# ProProject_Open_Energy_Box_2024-07-22.net
KiCad netlist of a schematic drawn in EasyEDA Pro
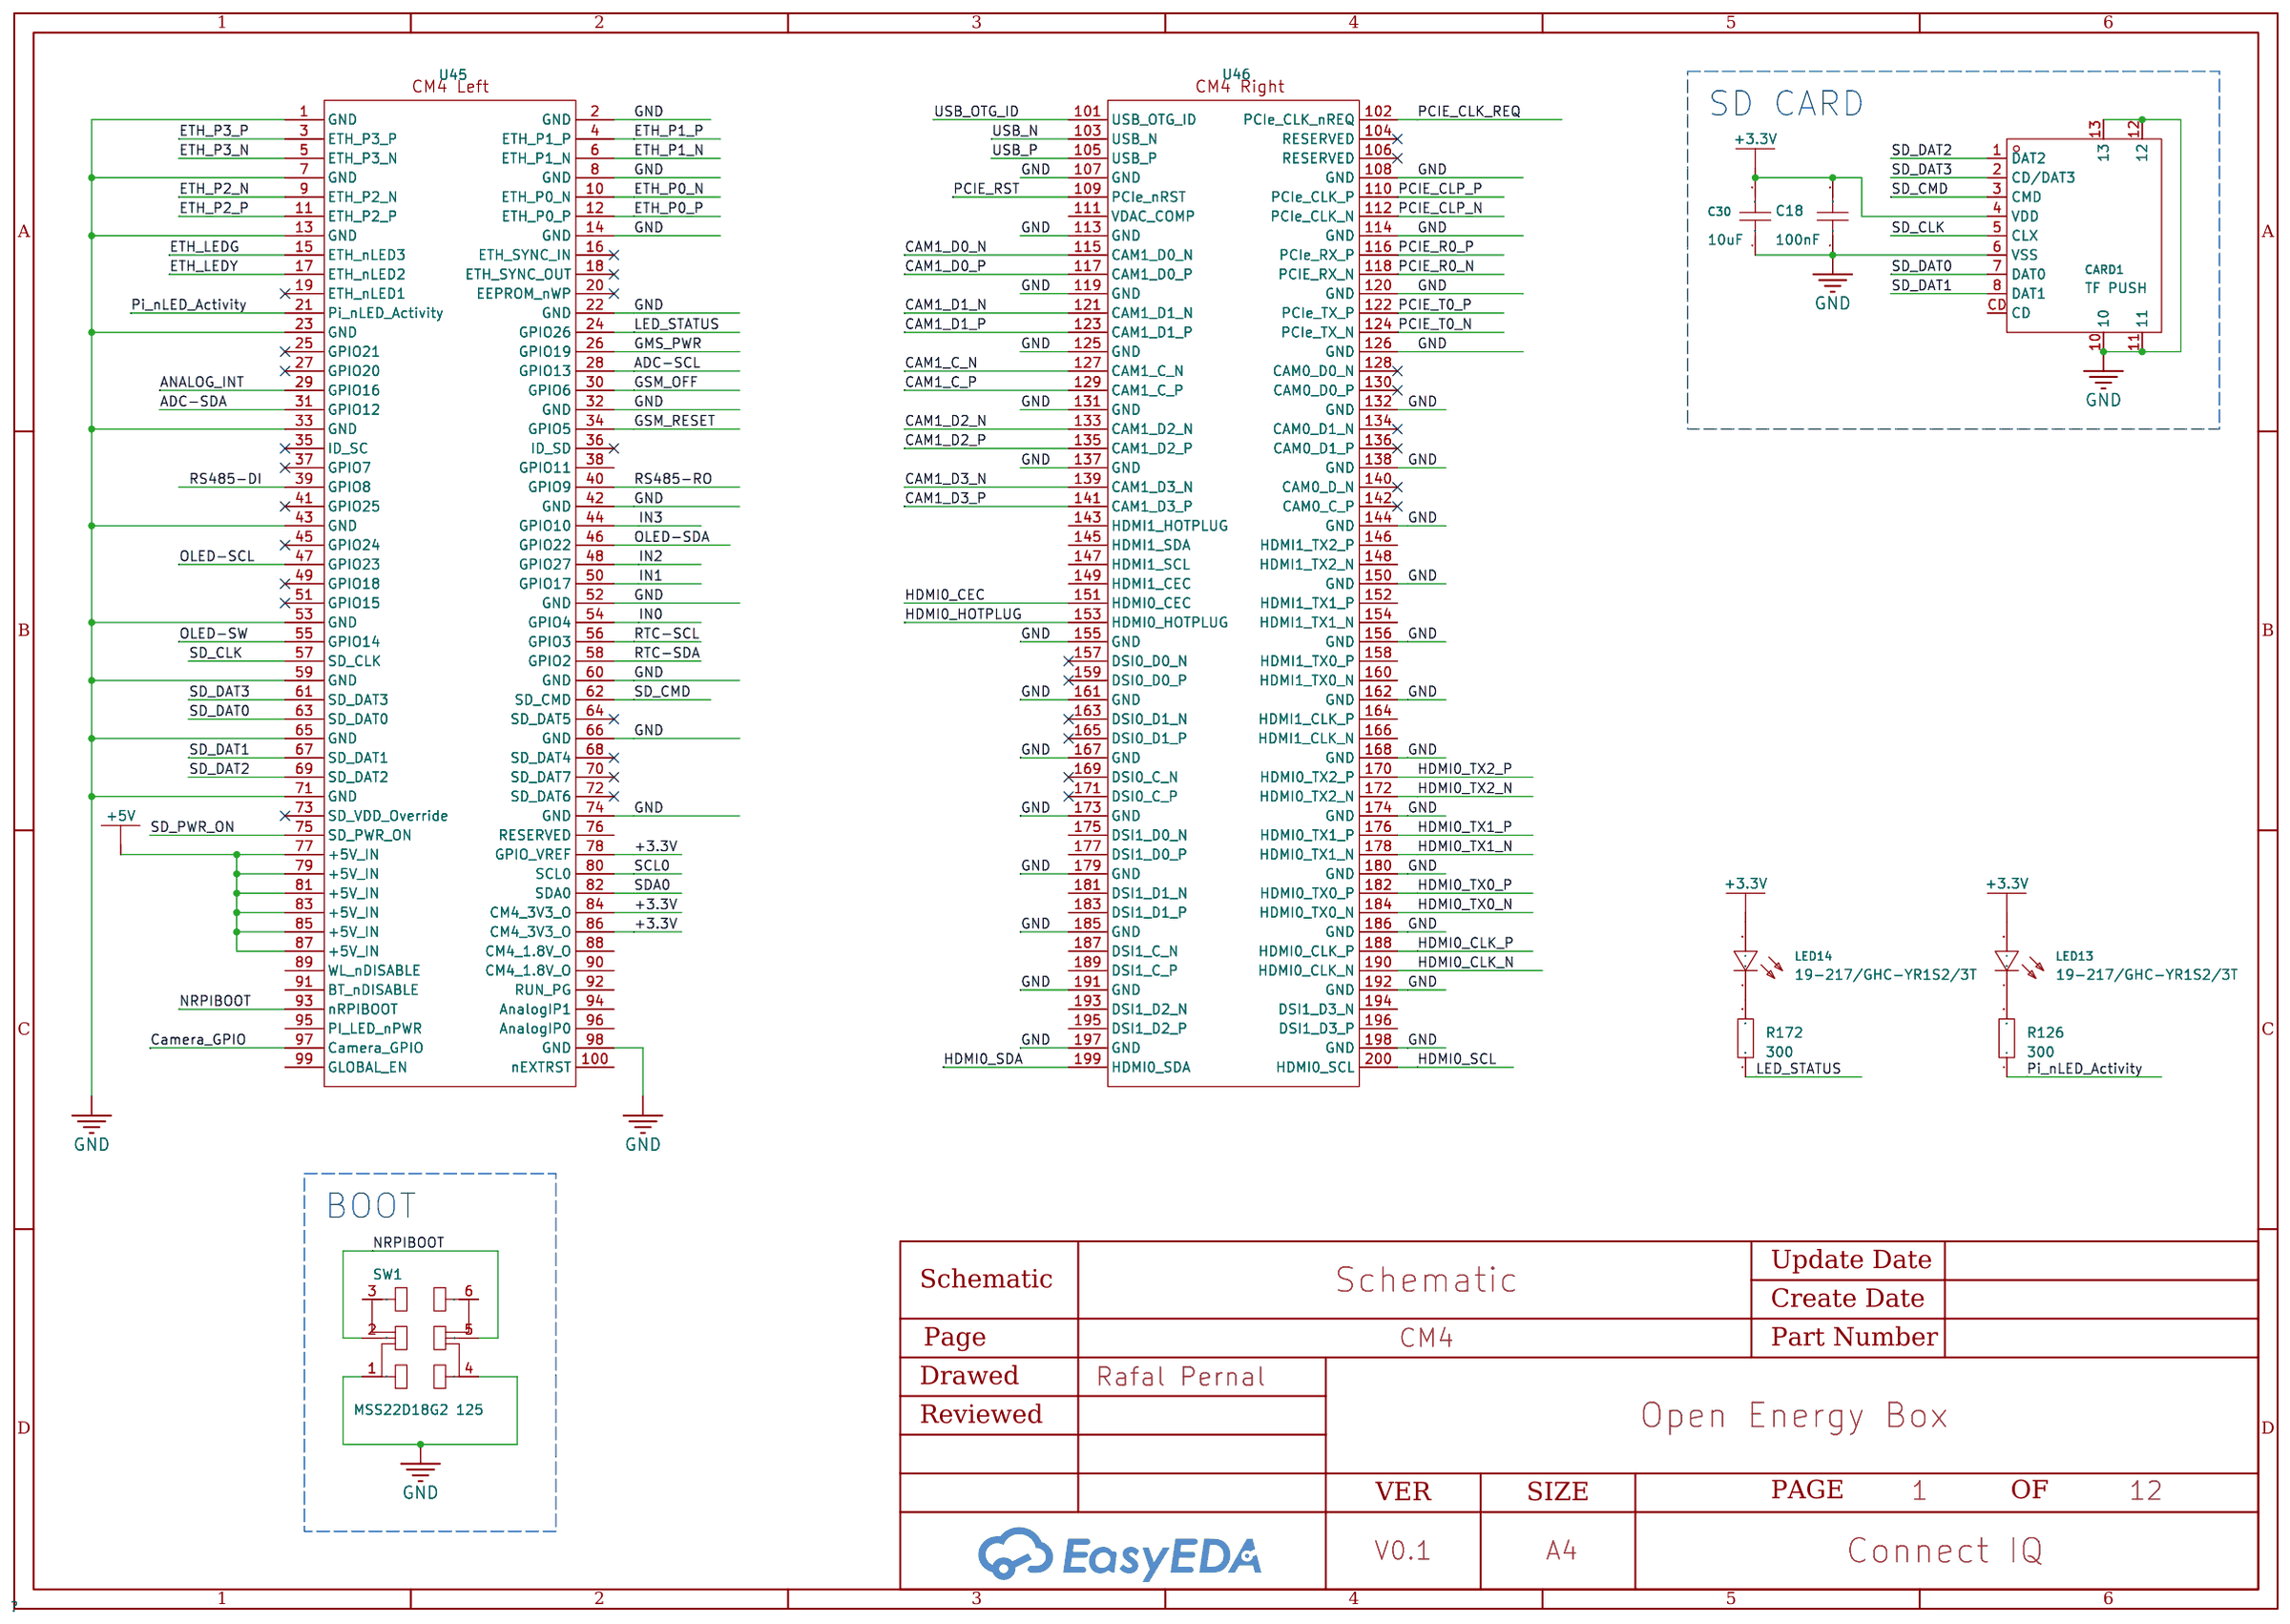
[diagram p0: CM4]
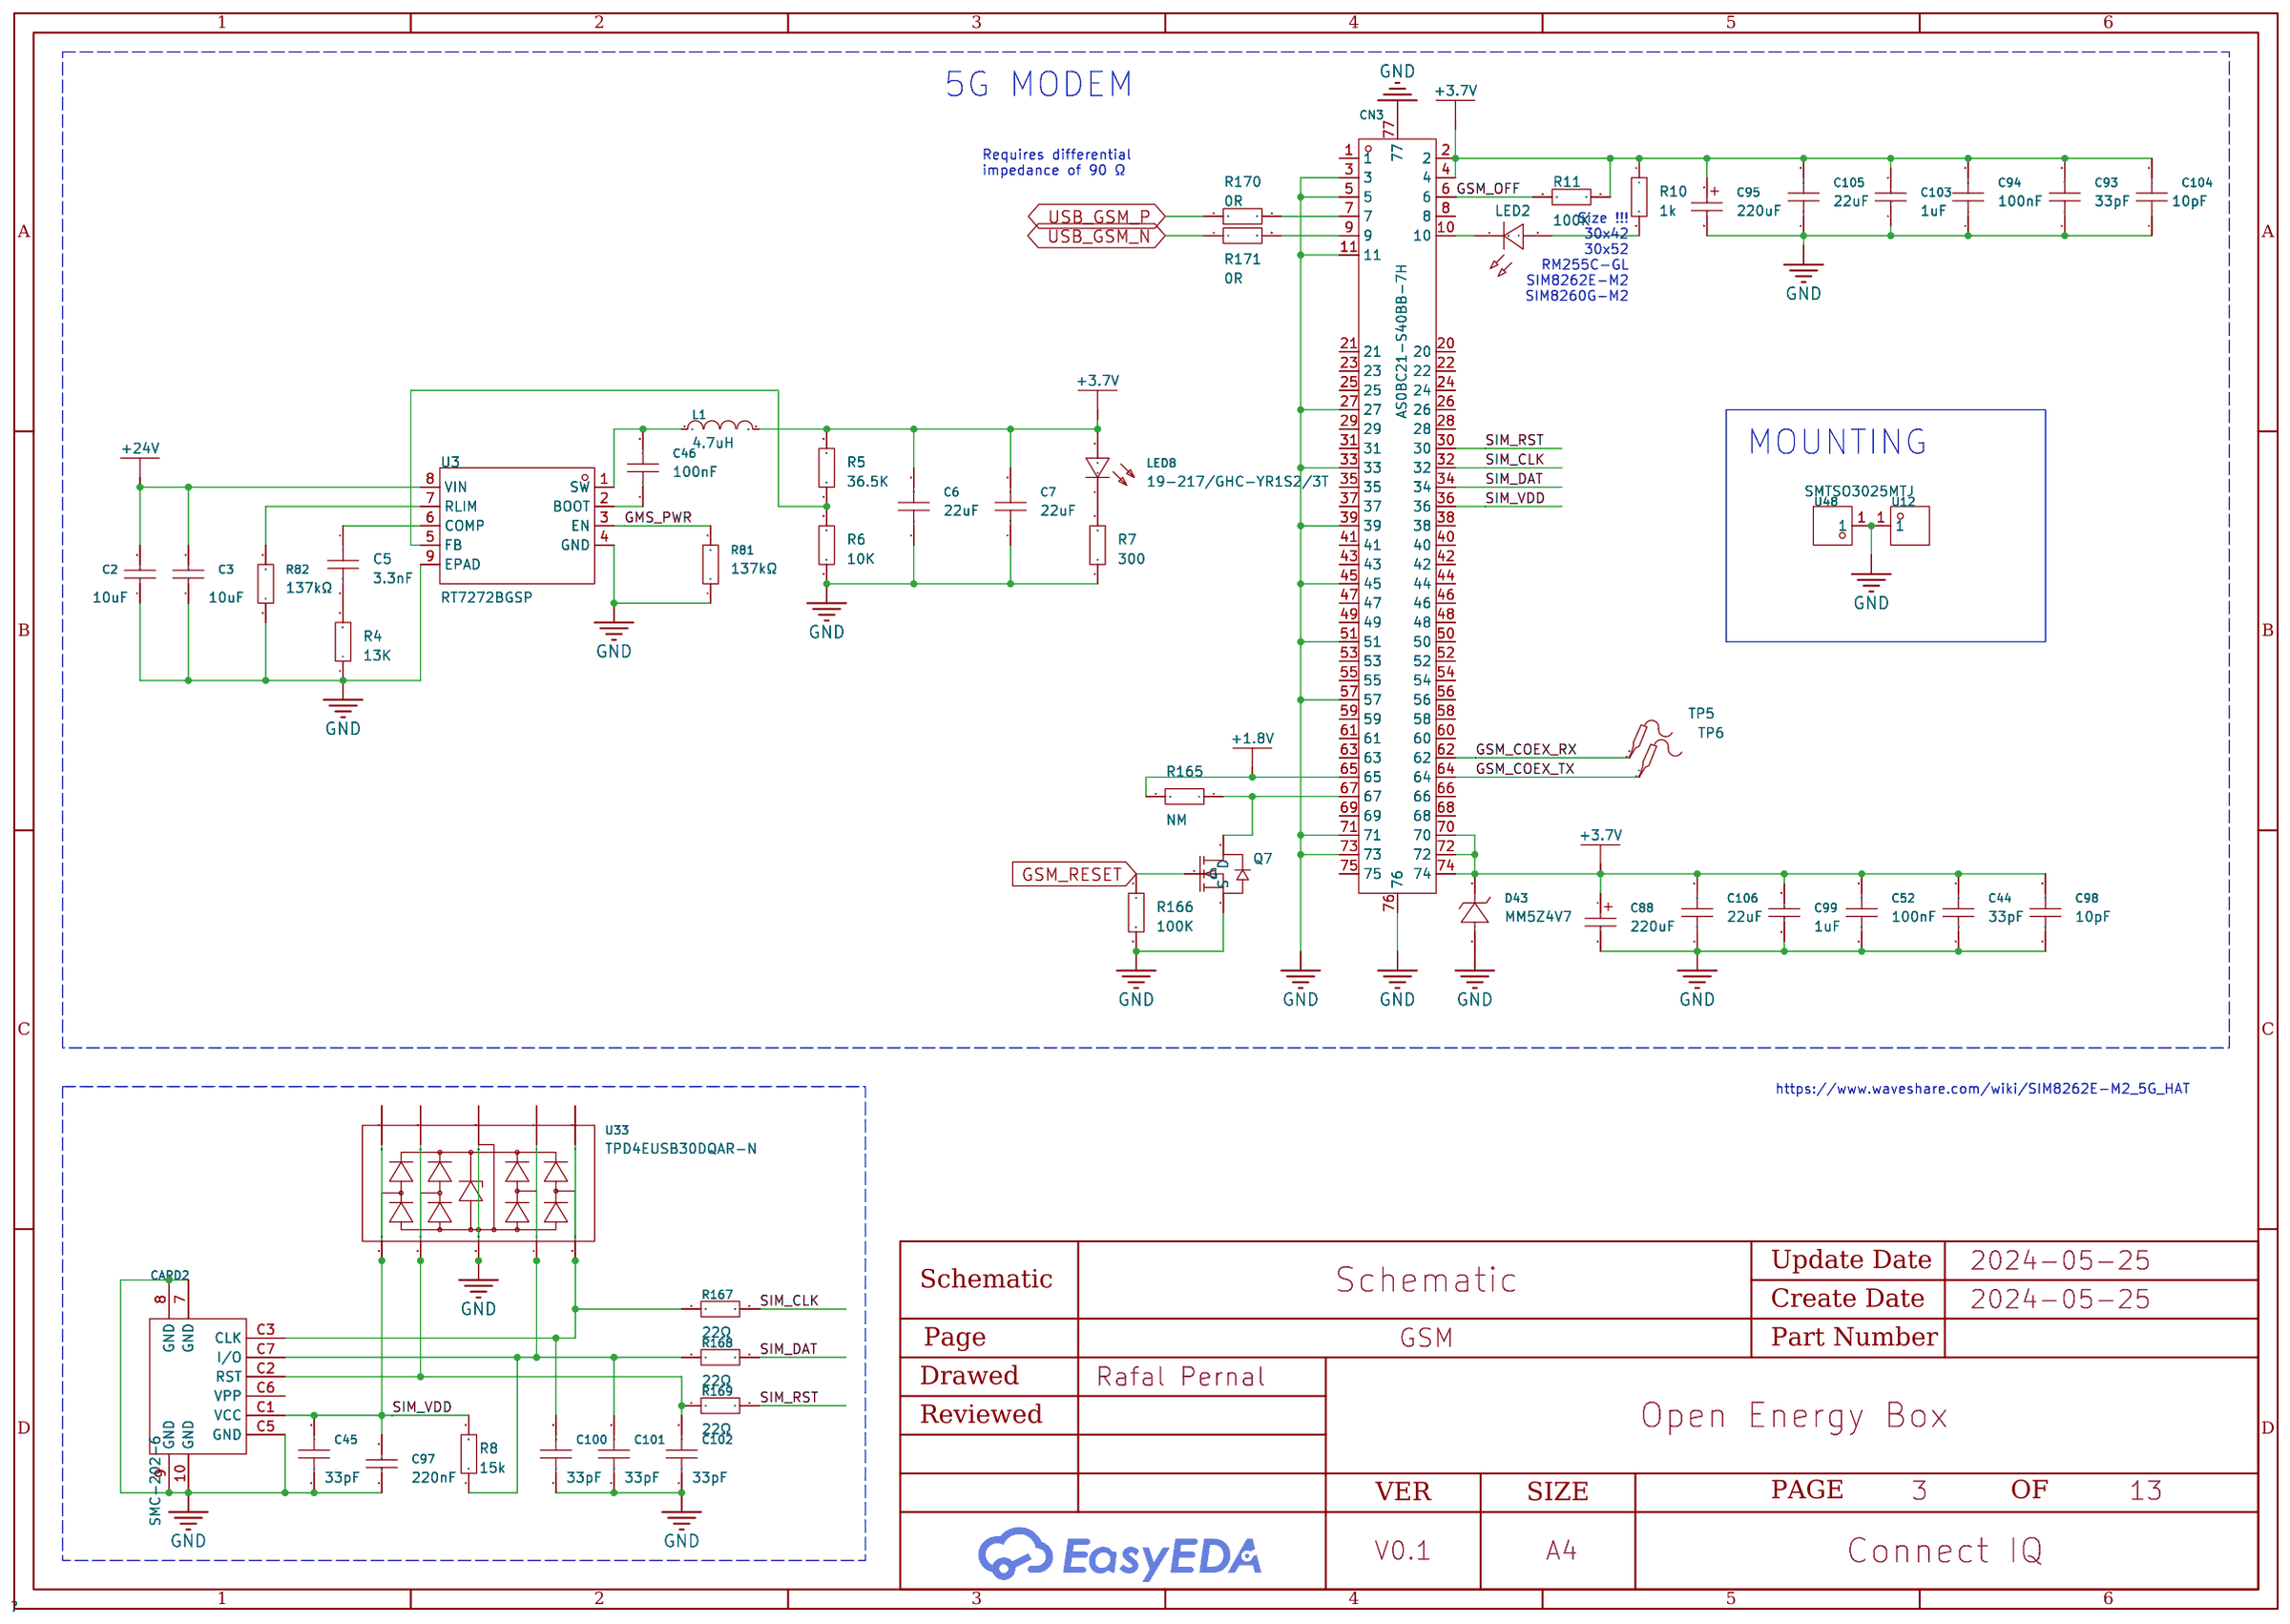
[diagram p1: GSM]
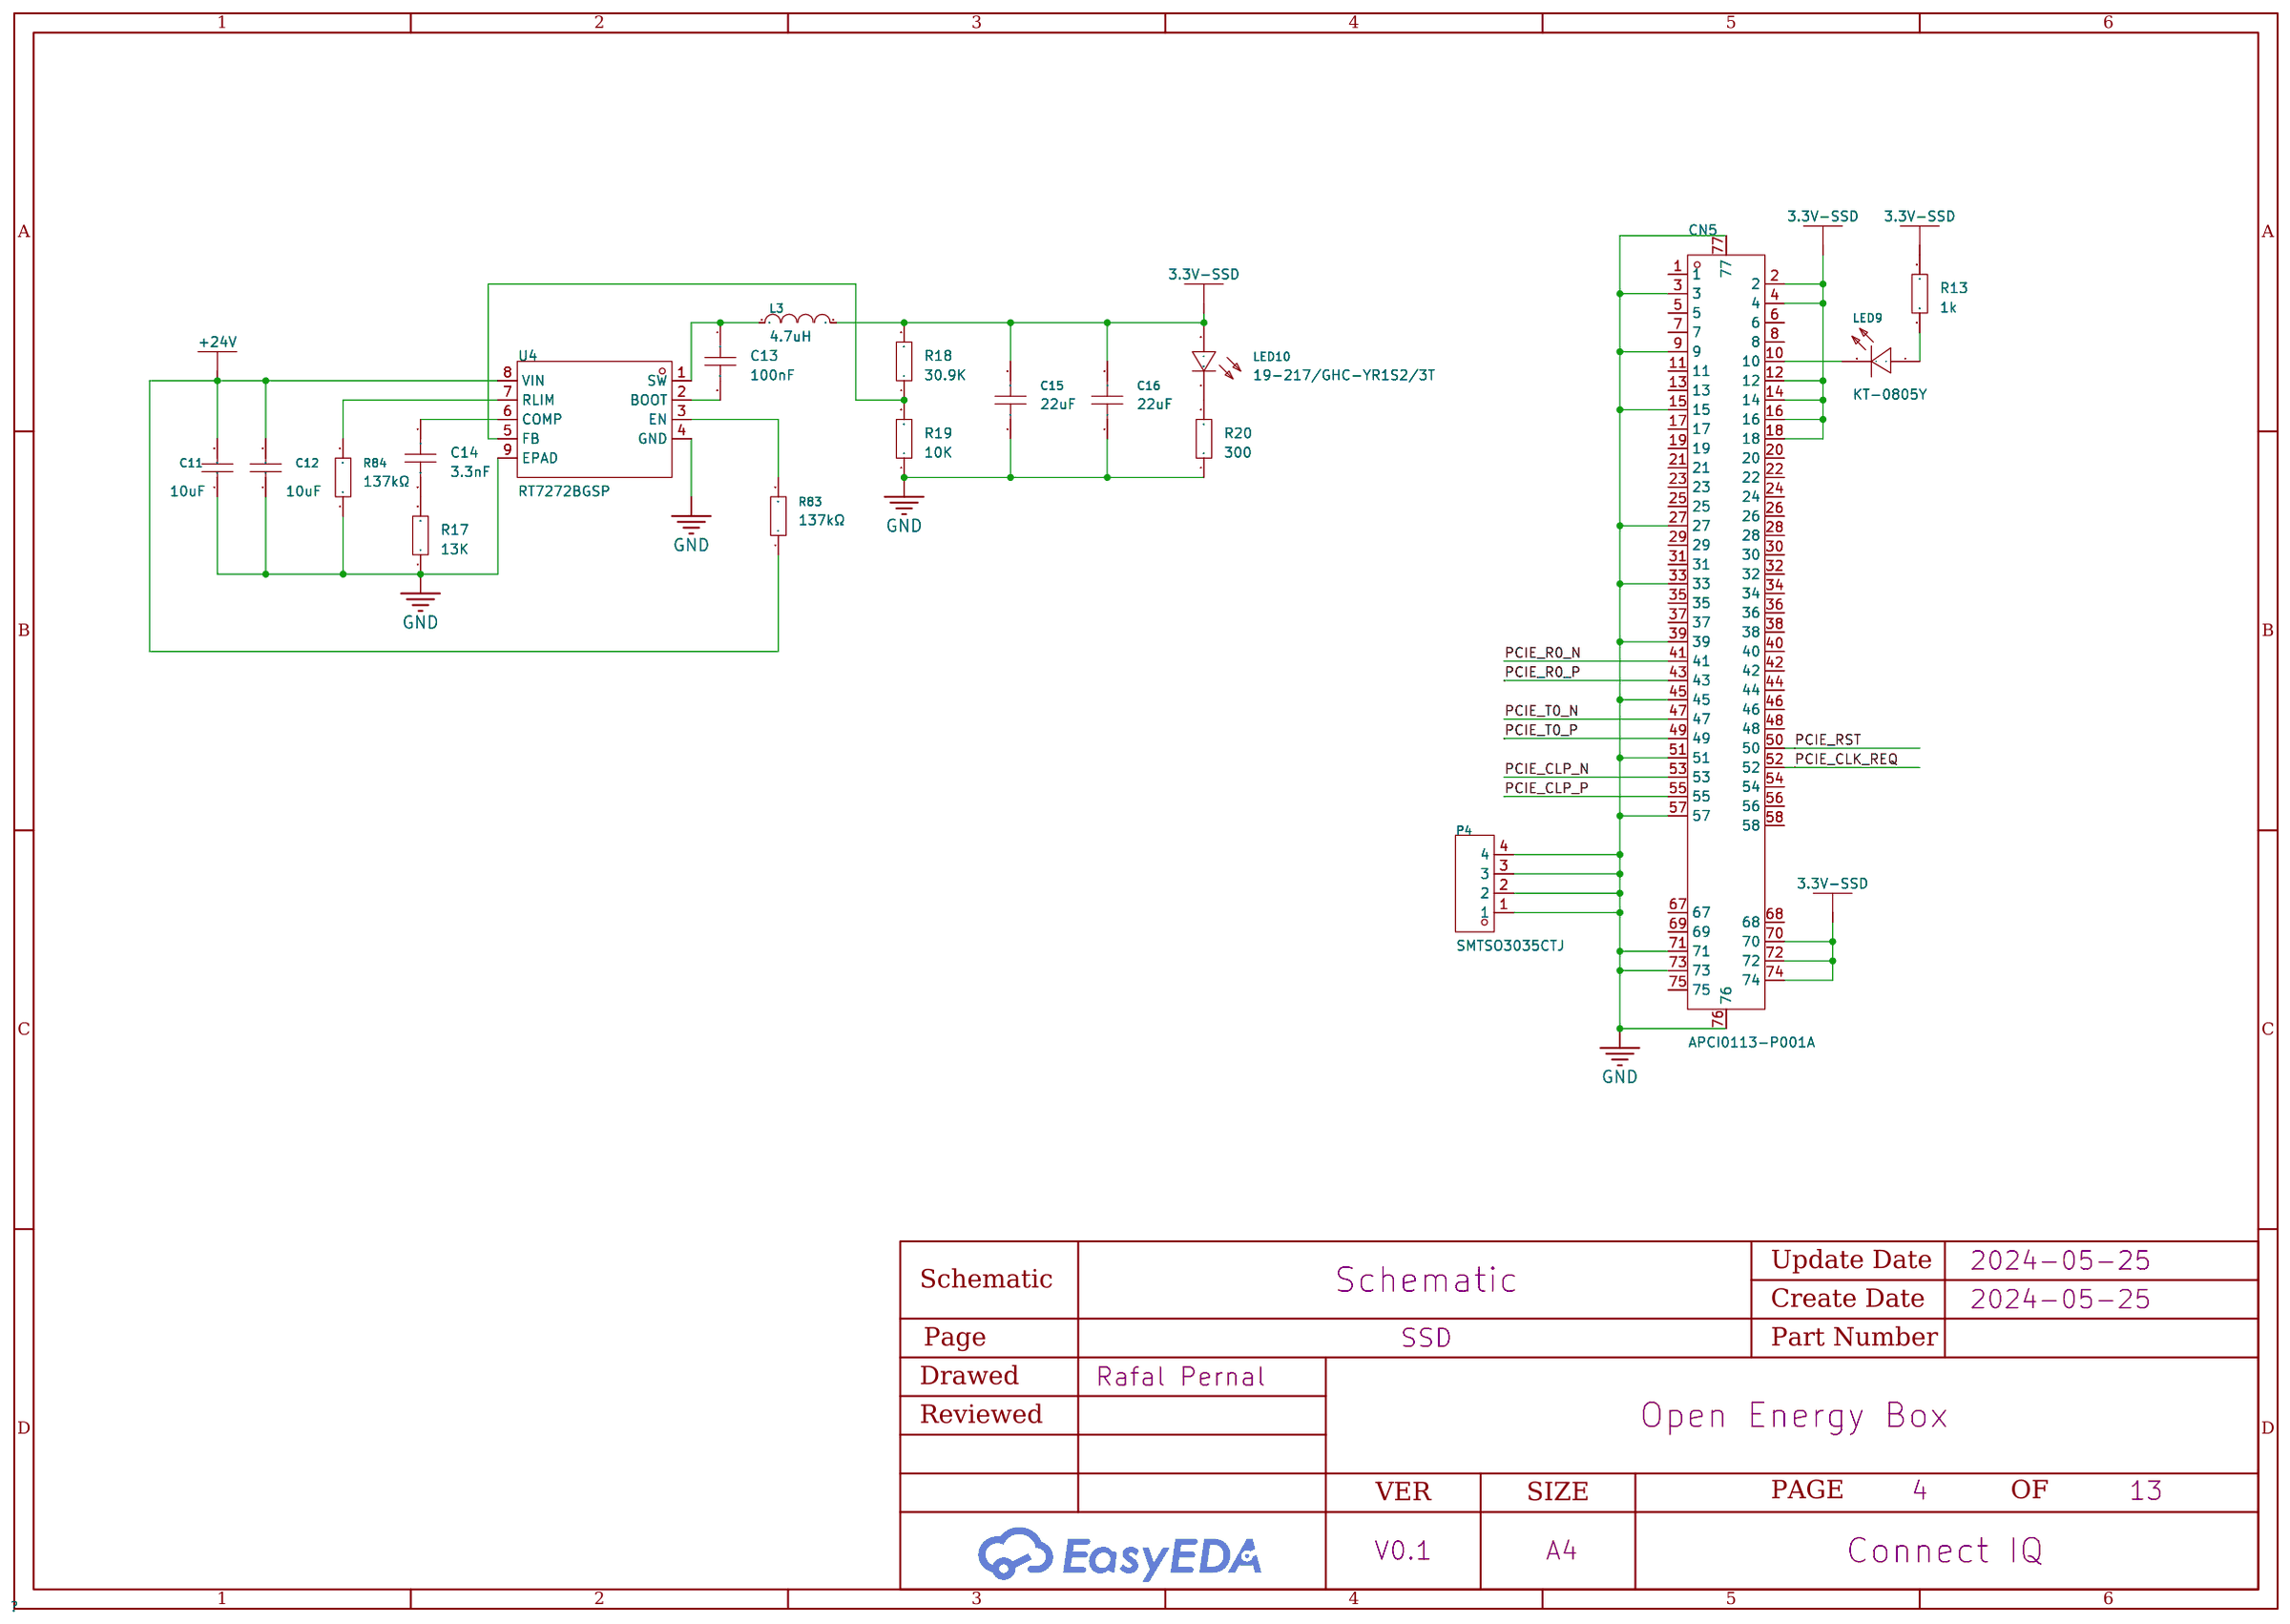
[diagram p2: SSD]
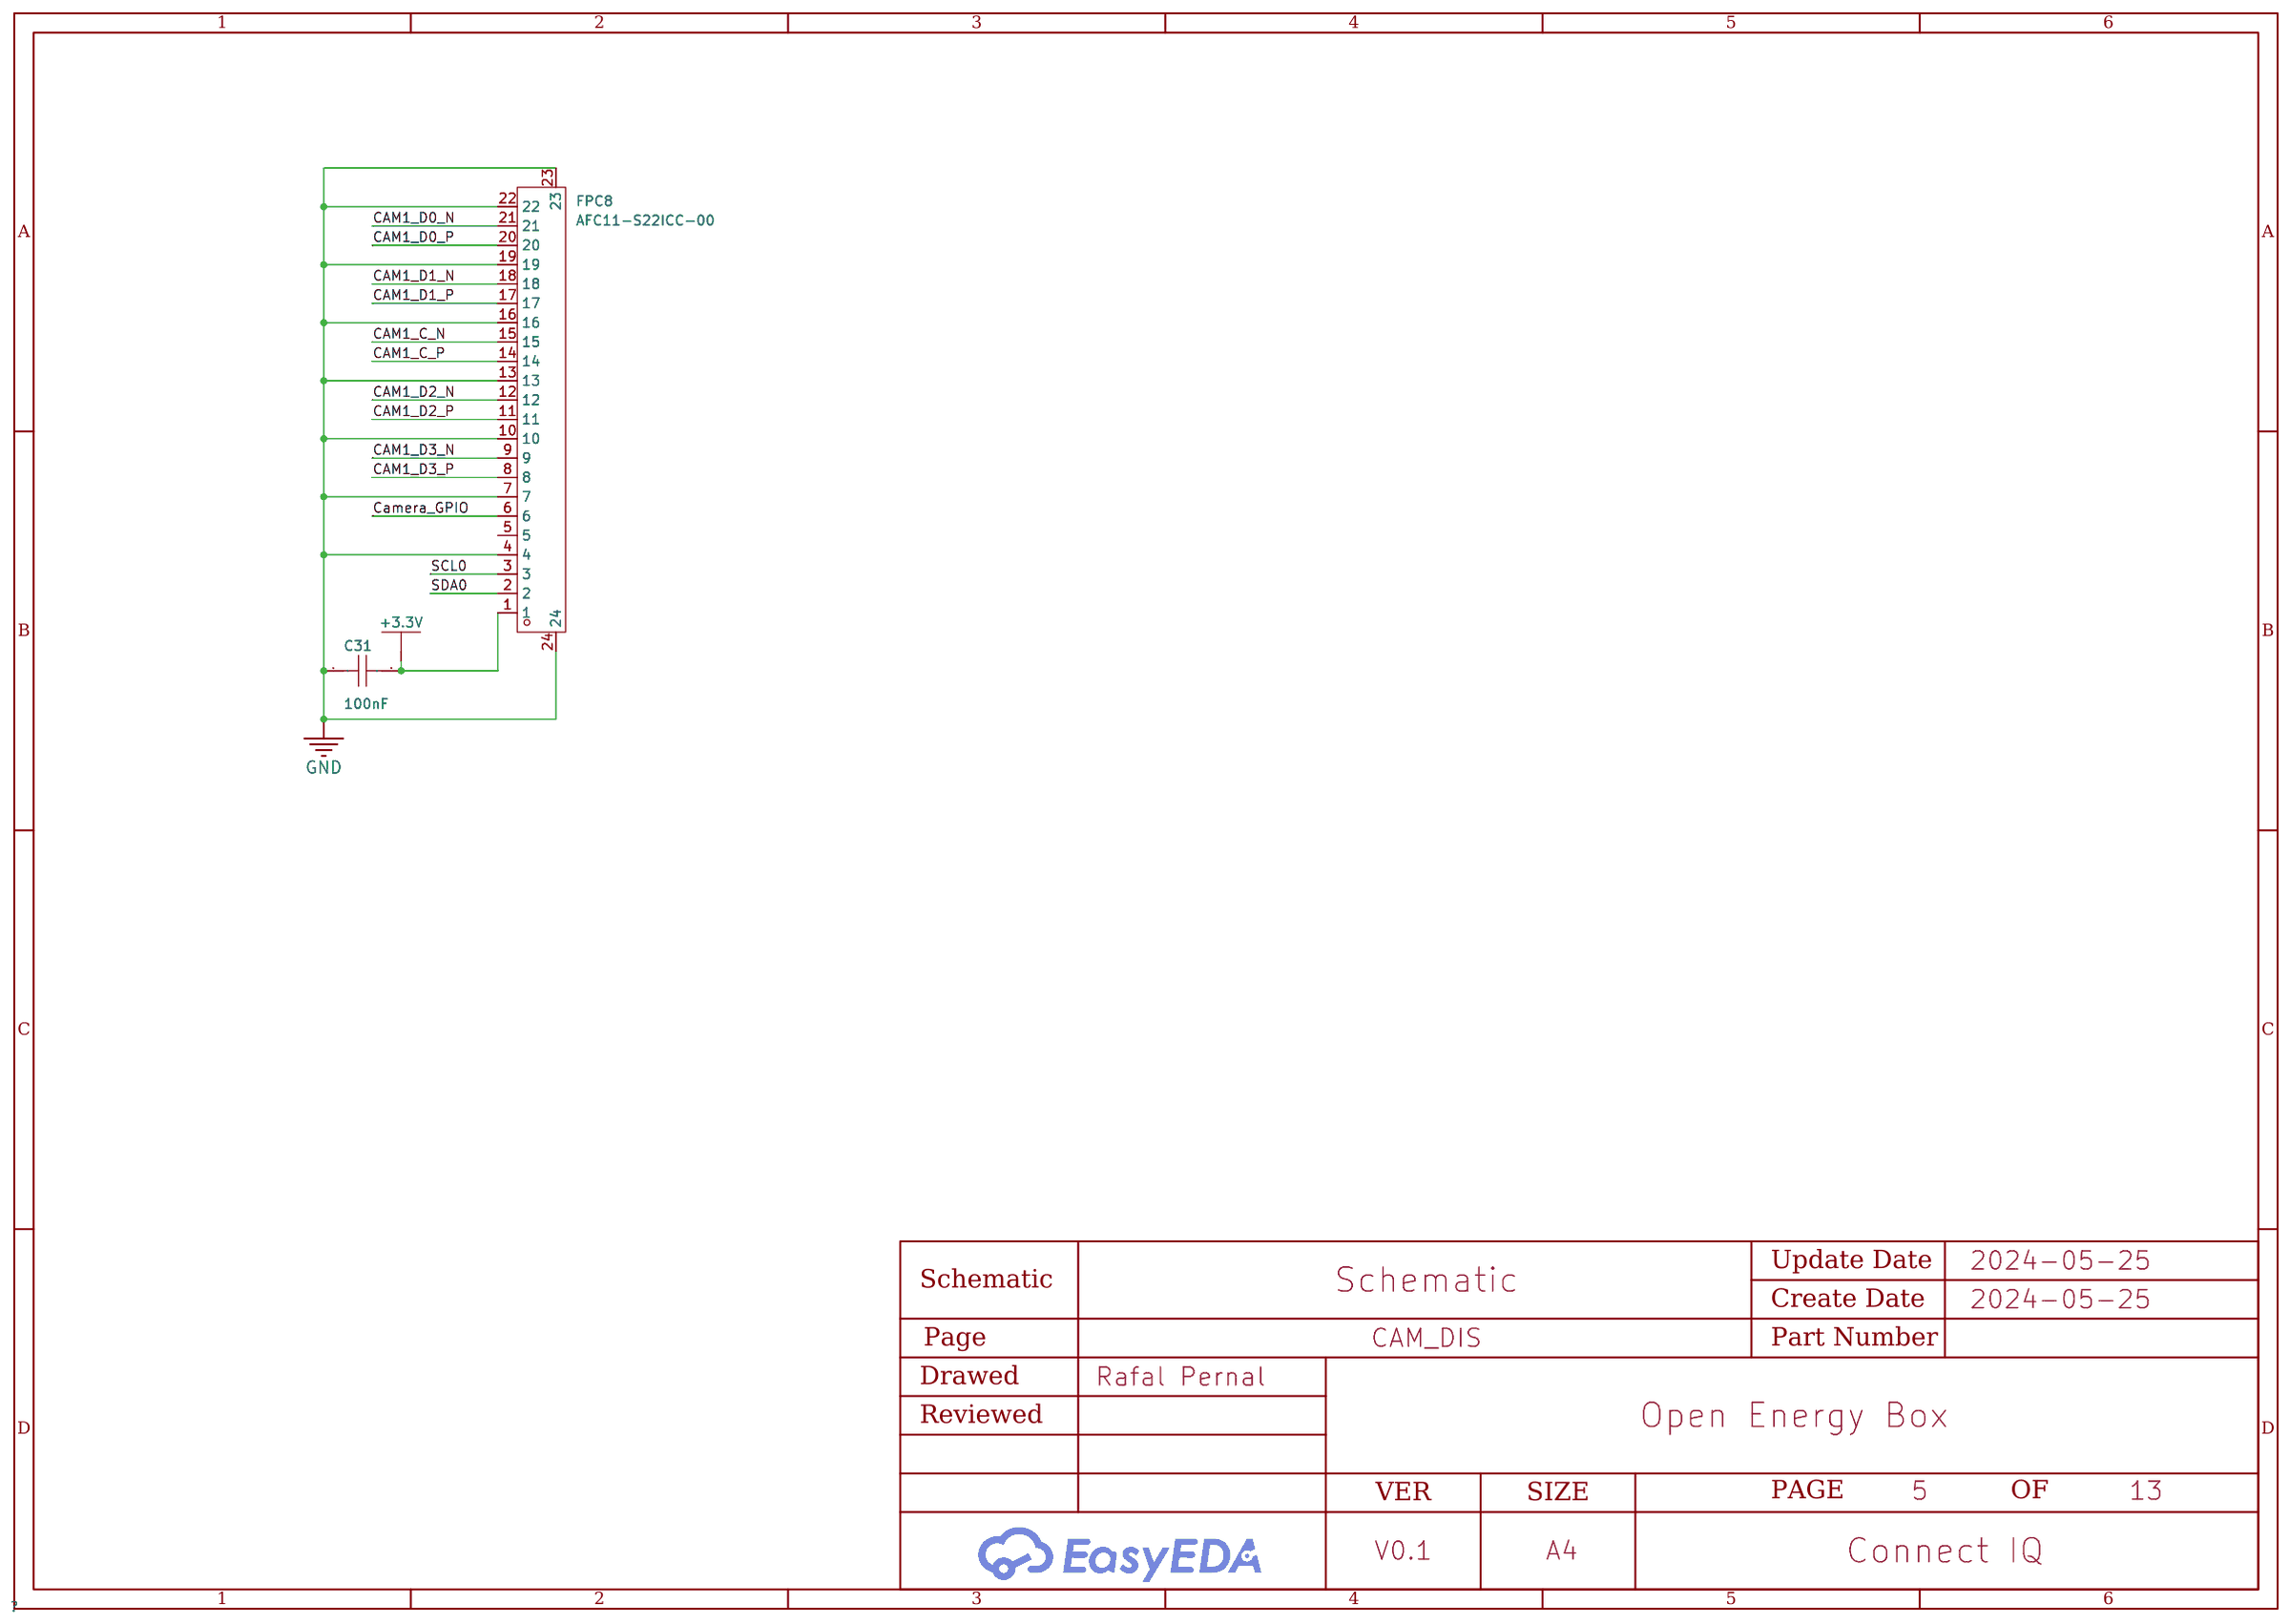
[diagram p3: CAM_DIS]
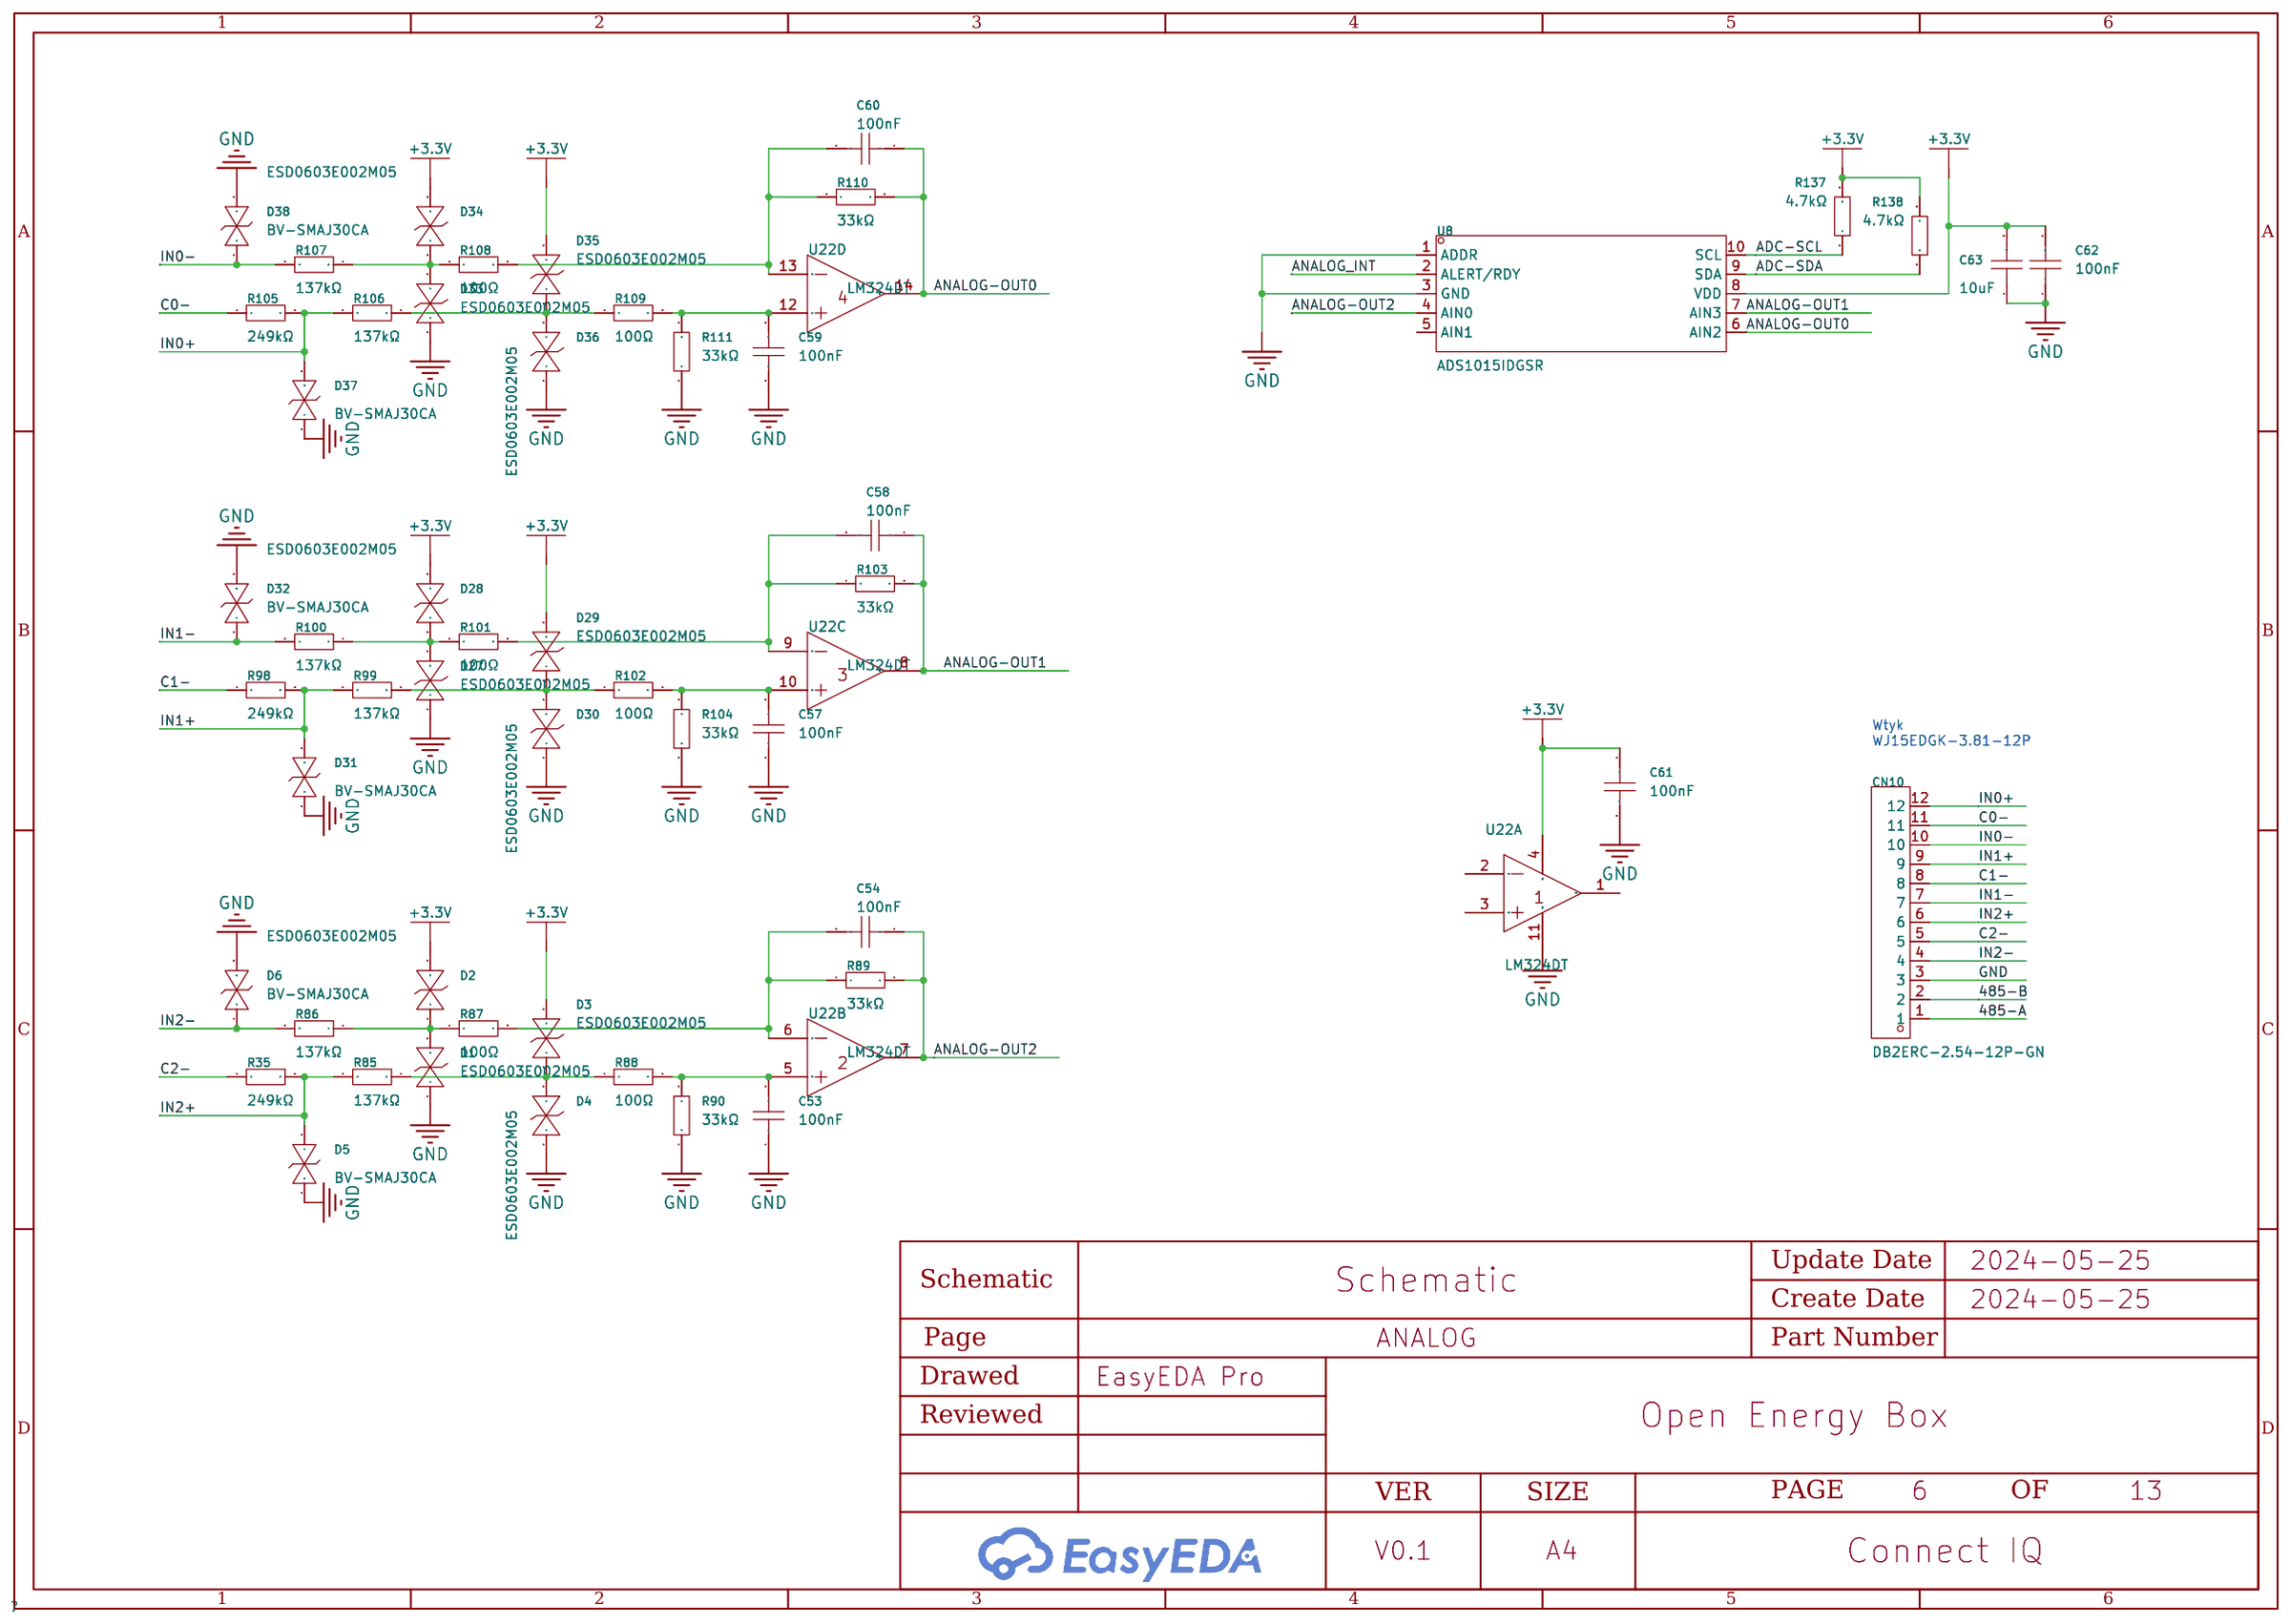
[diagram p4: ANALOG]
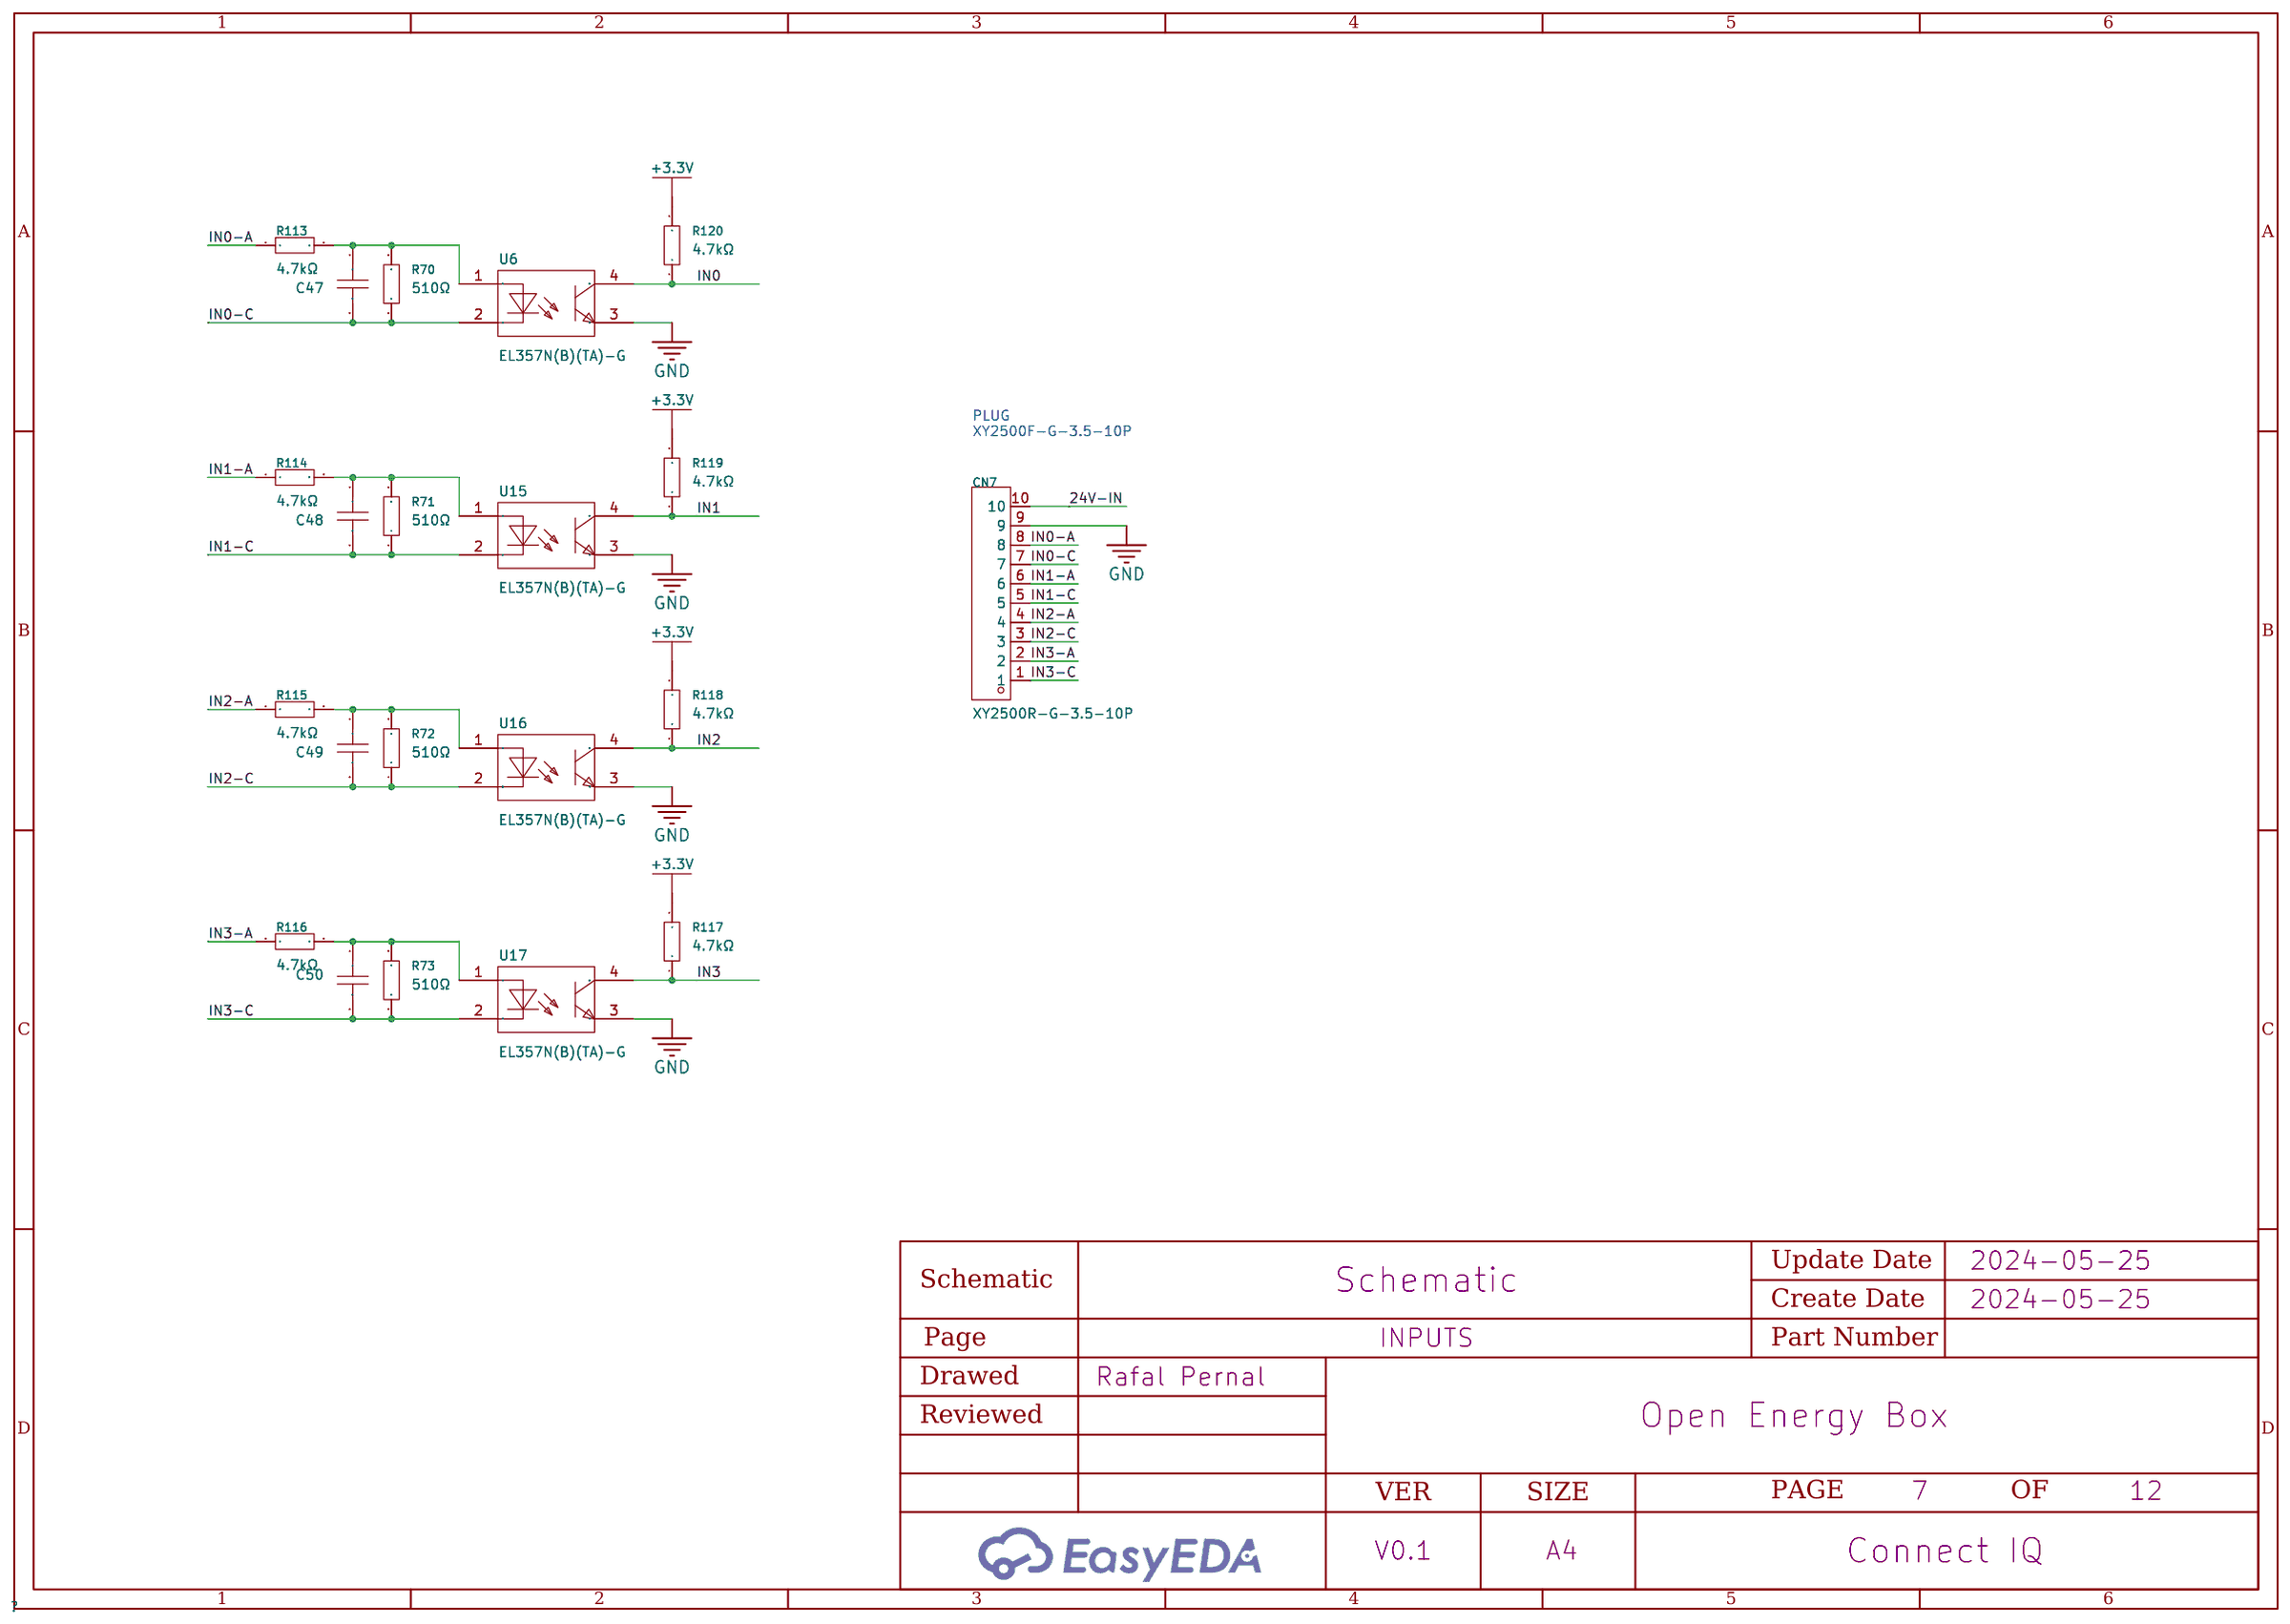
[diagram p5: INPUTS]
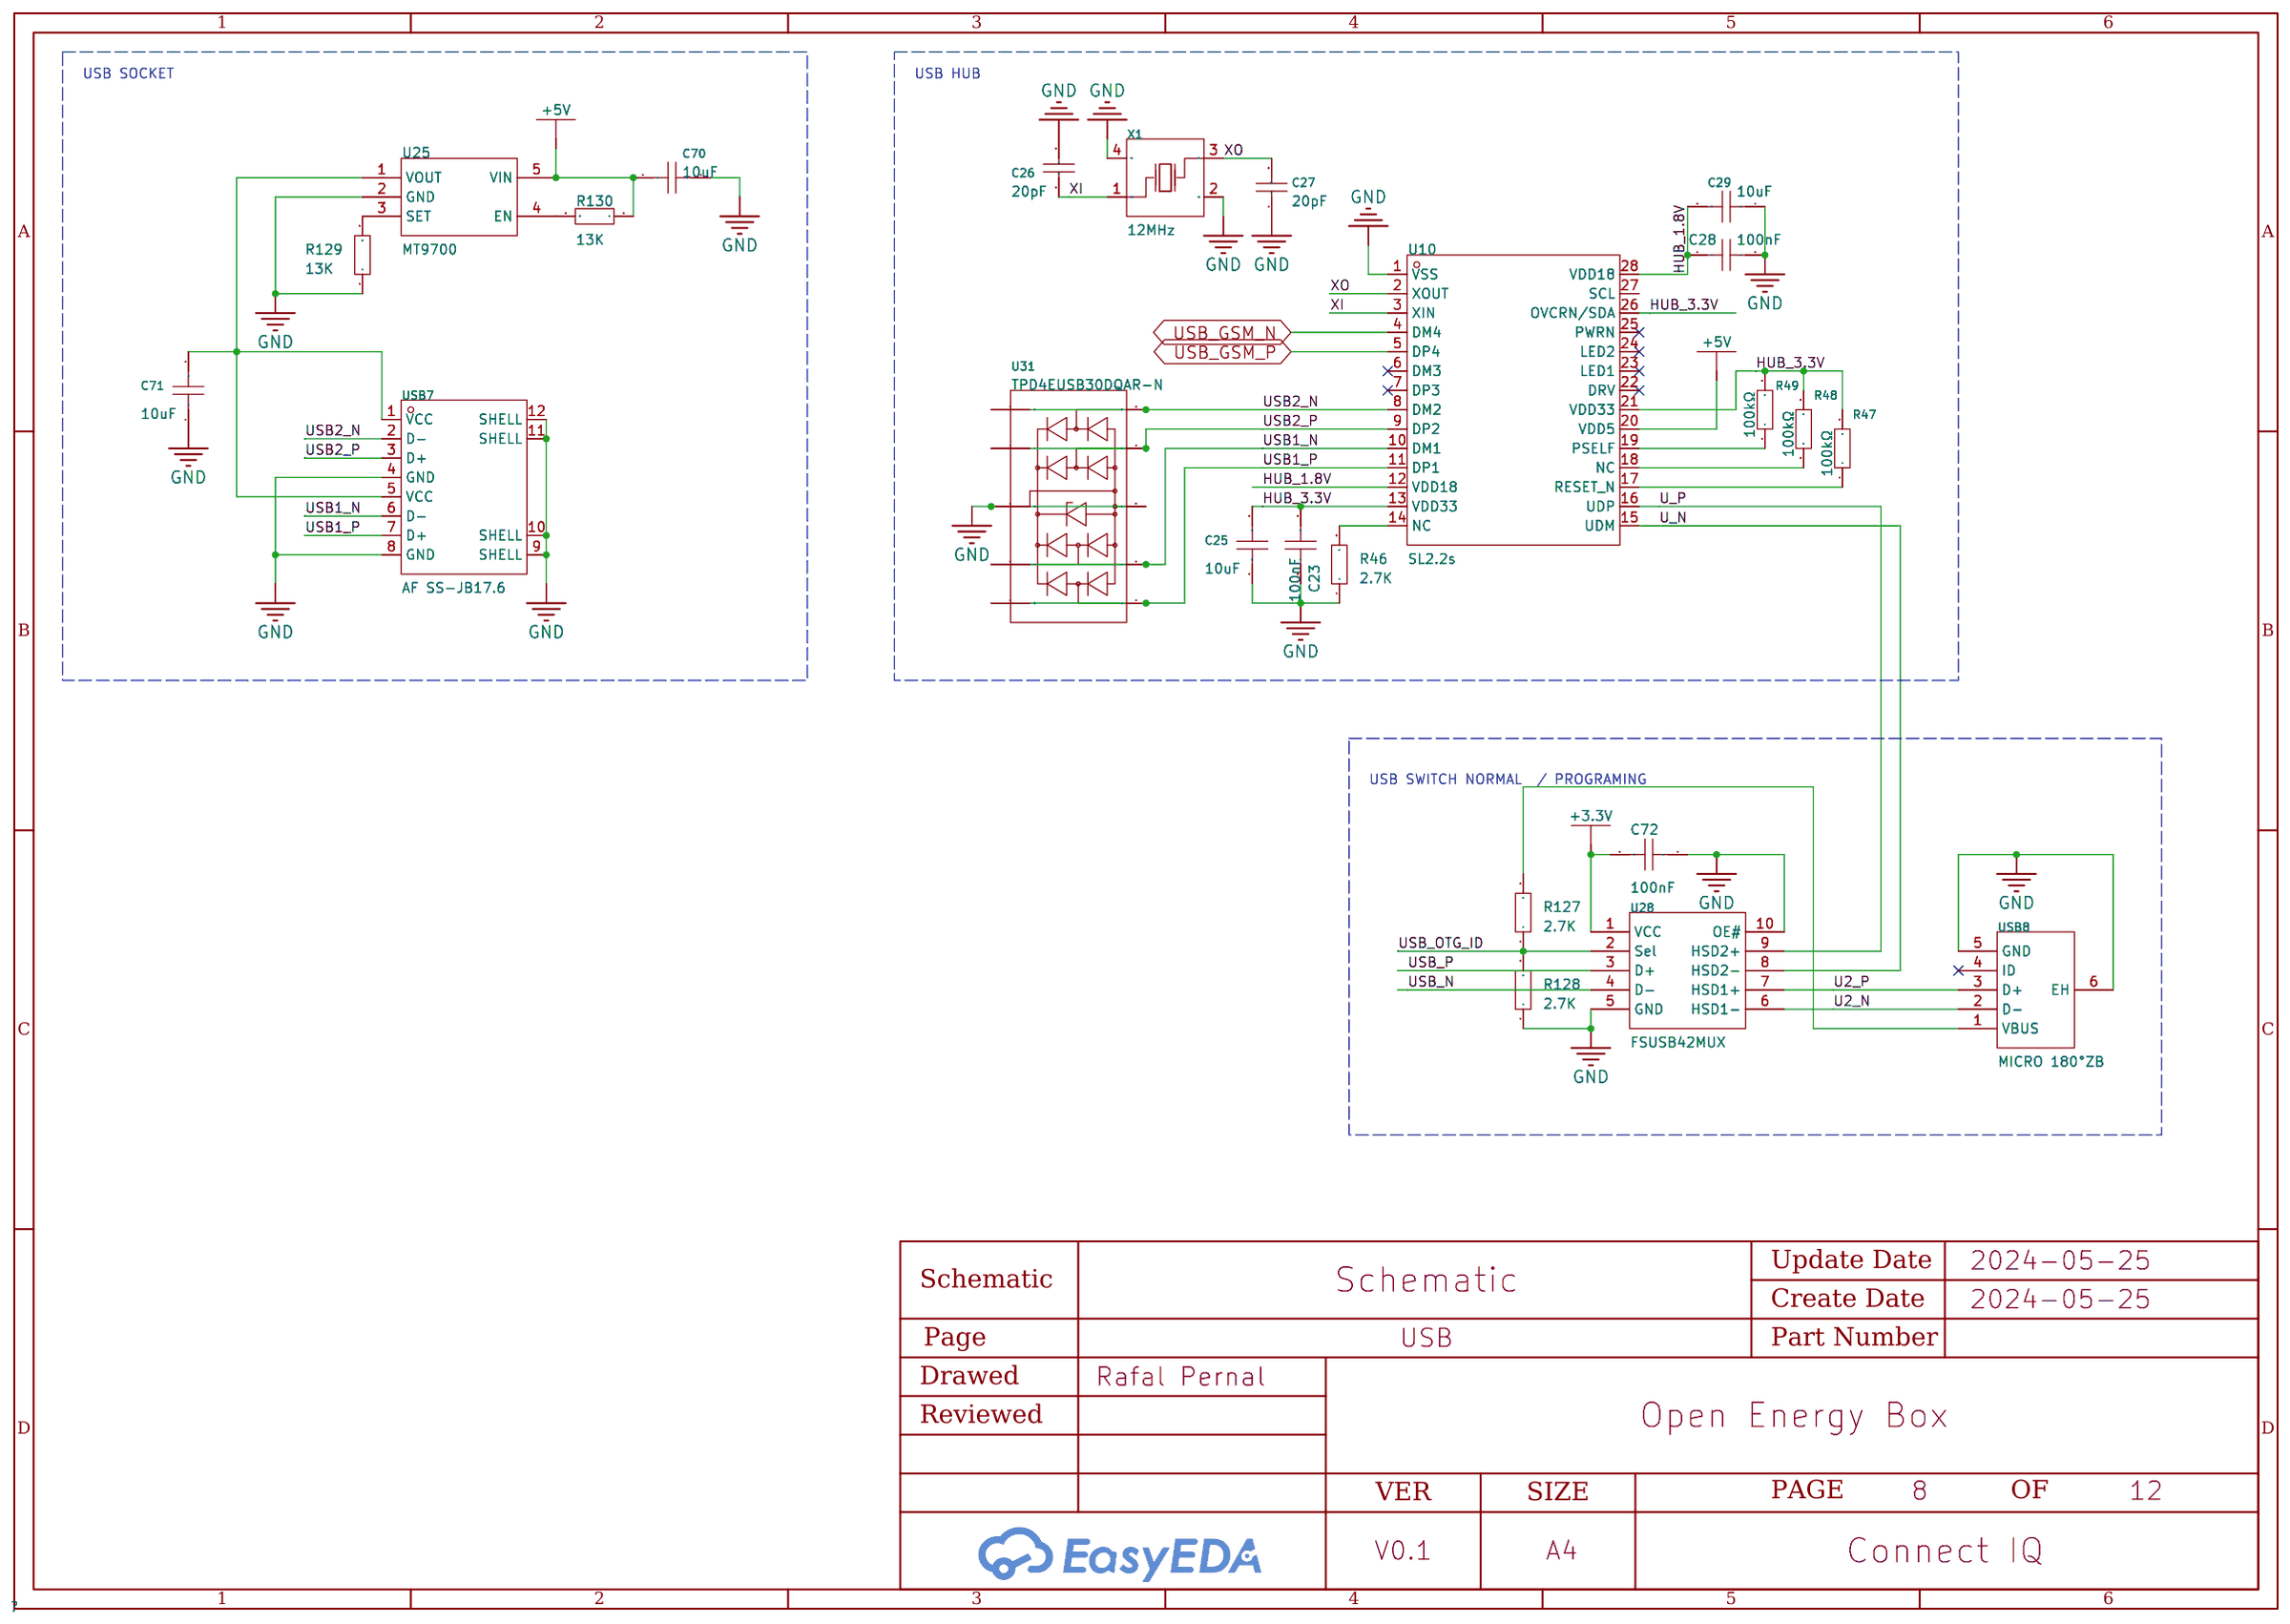
[diagram p6: USB]
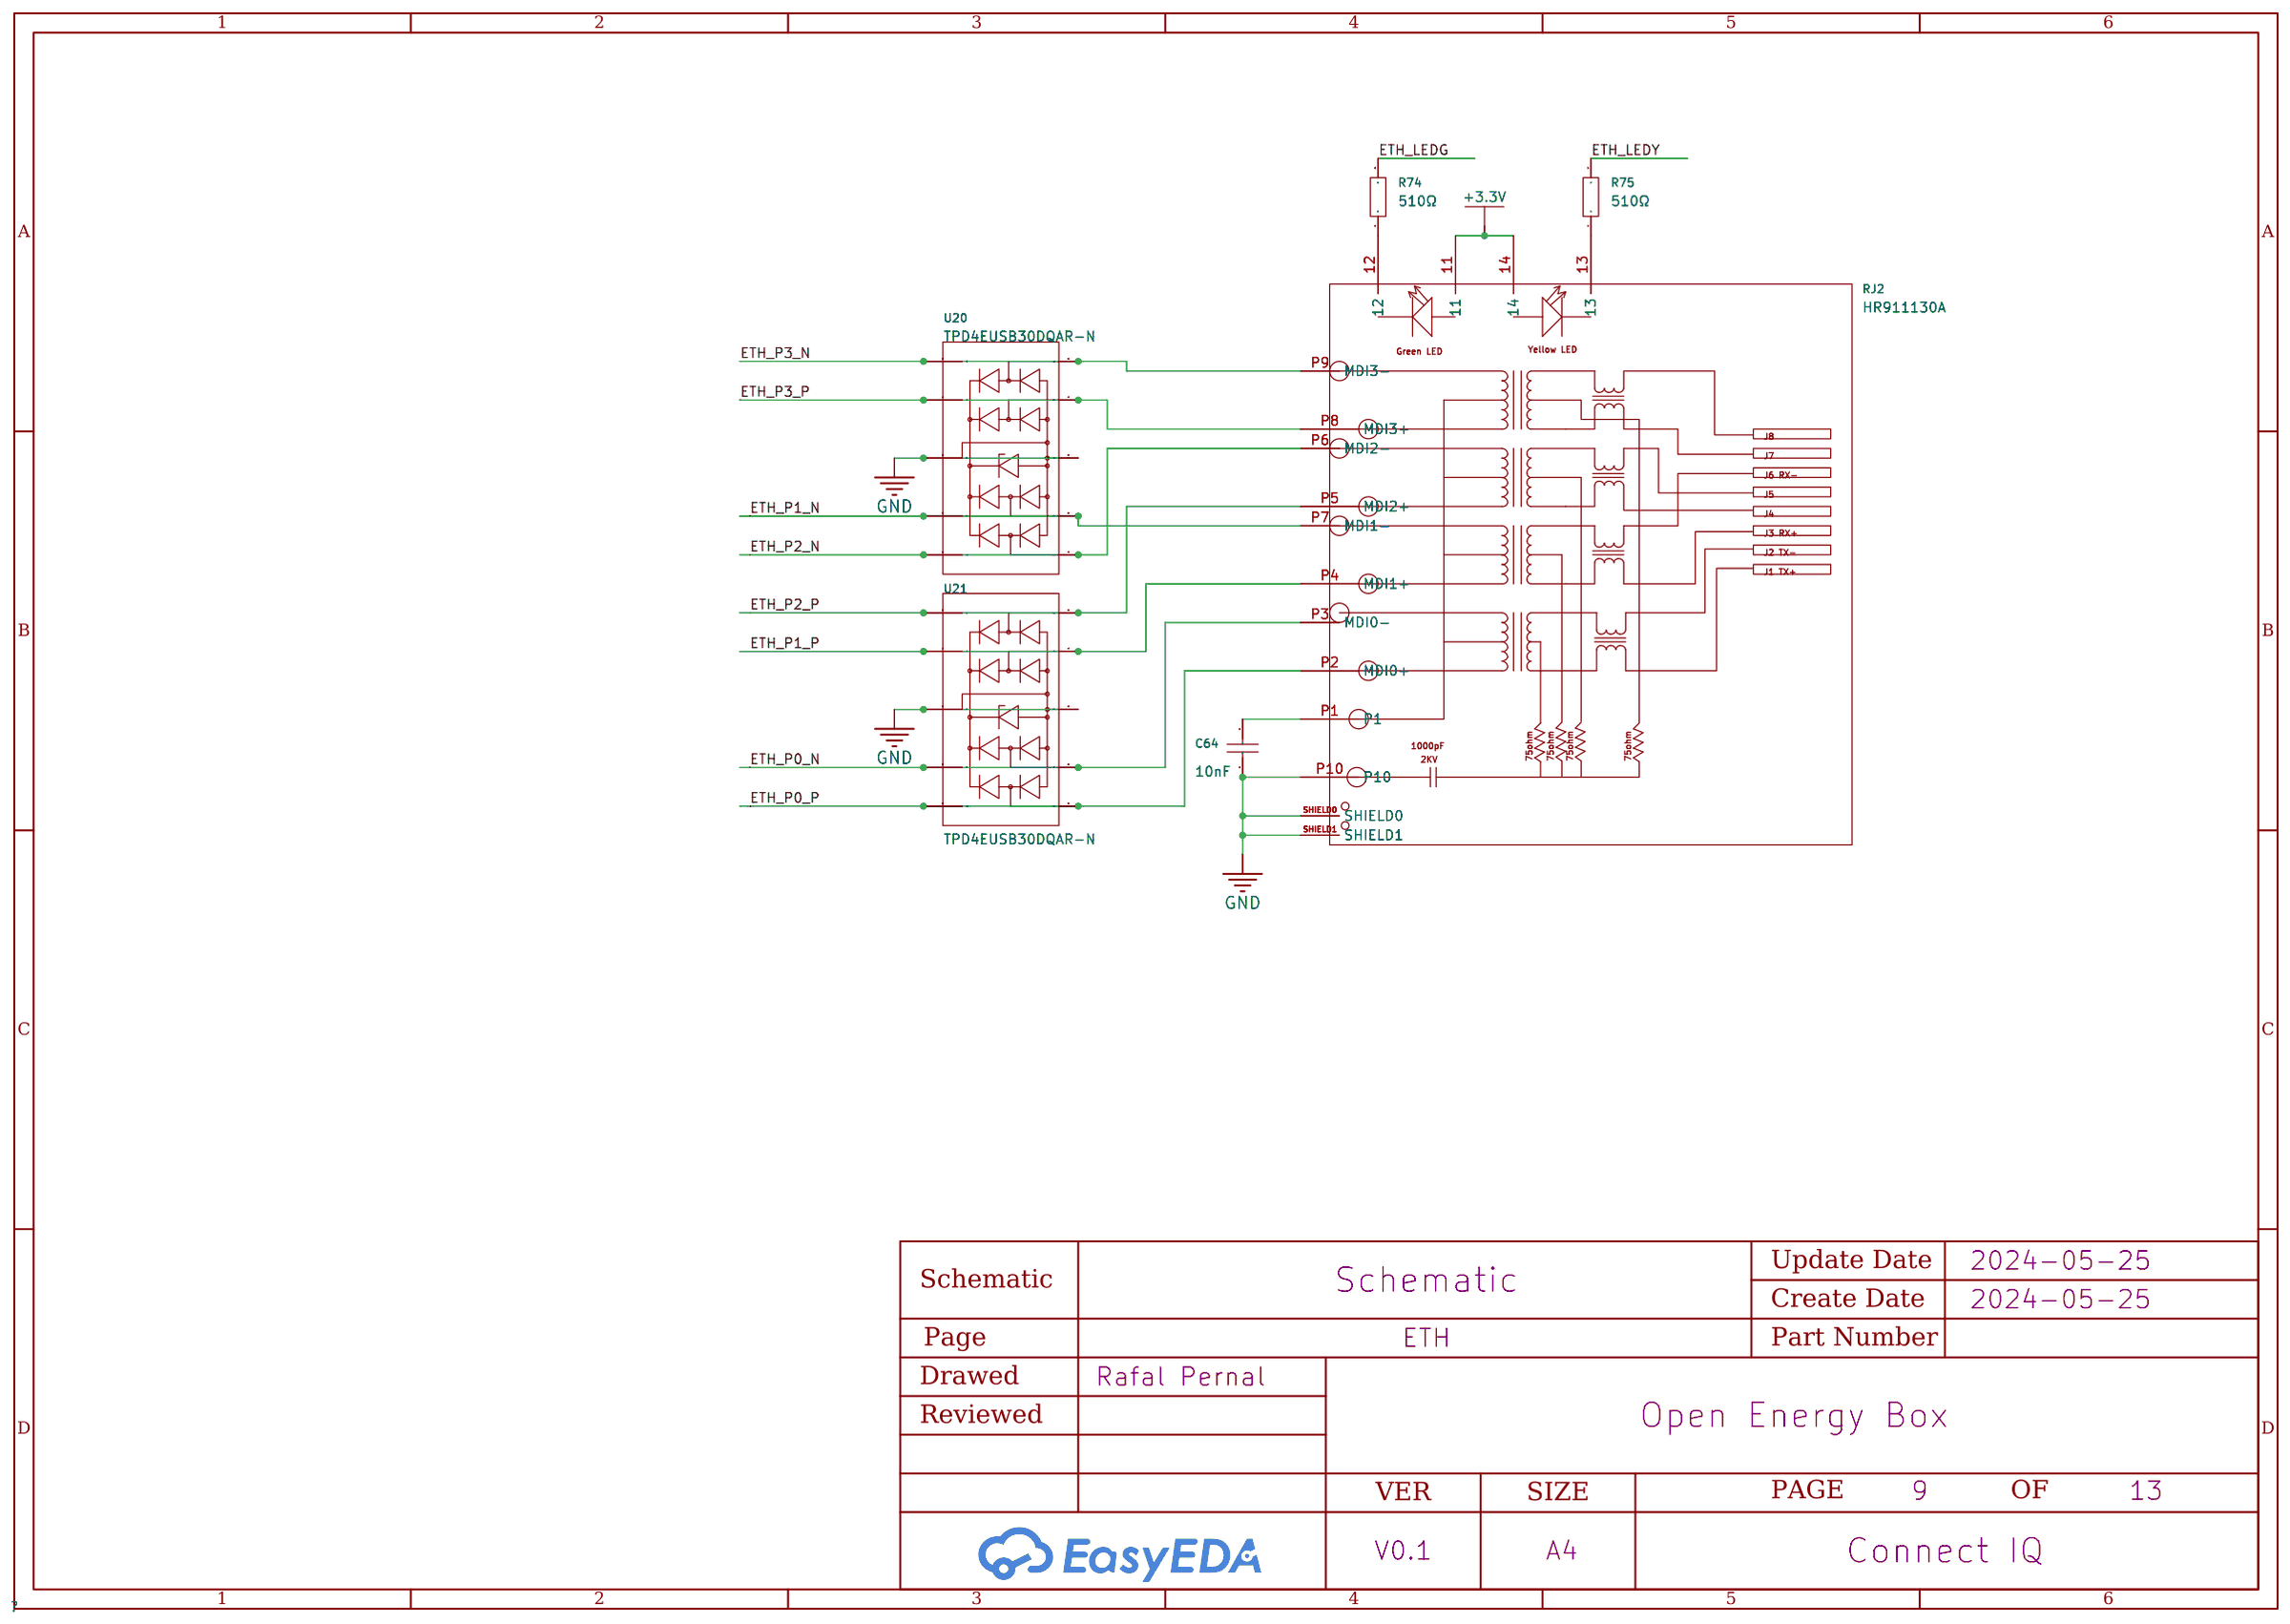
[diagram p7: ETH]
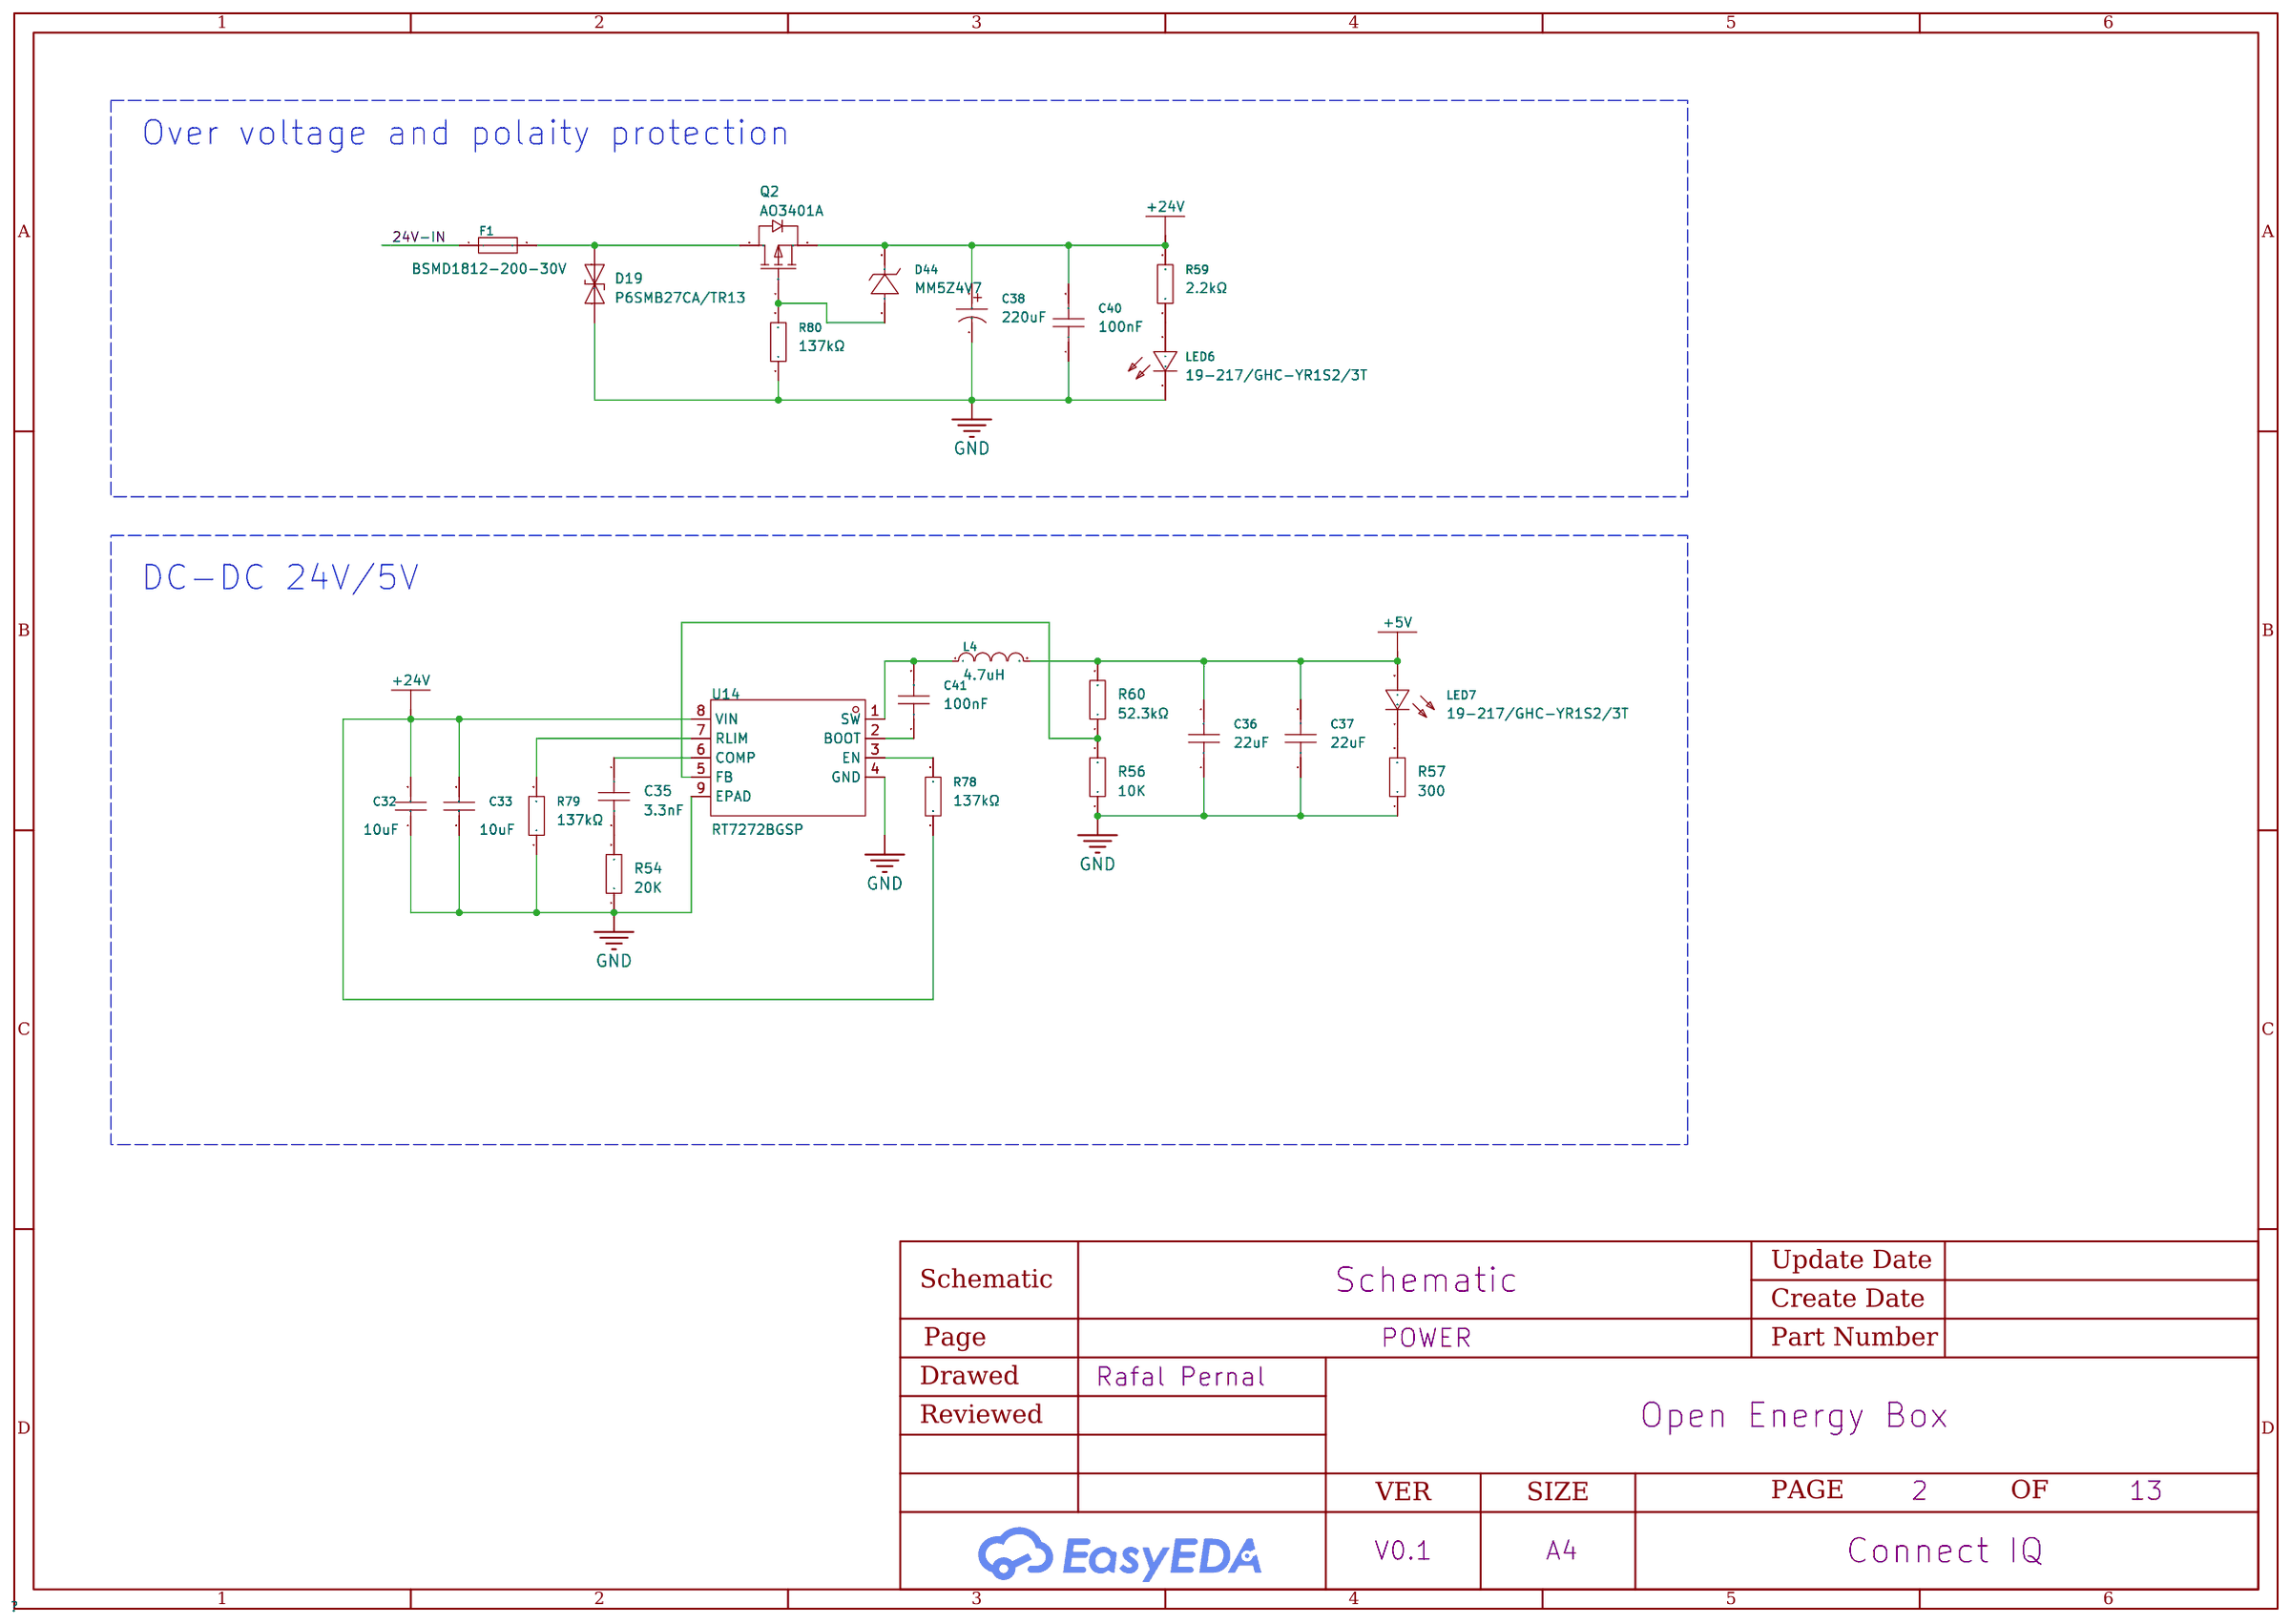
[diagram p8: POWER]
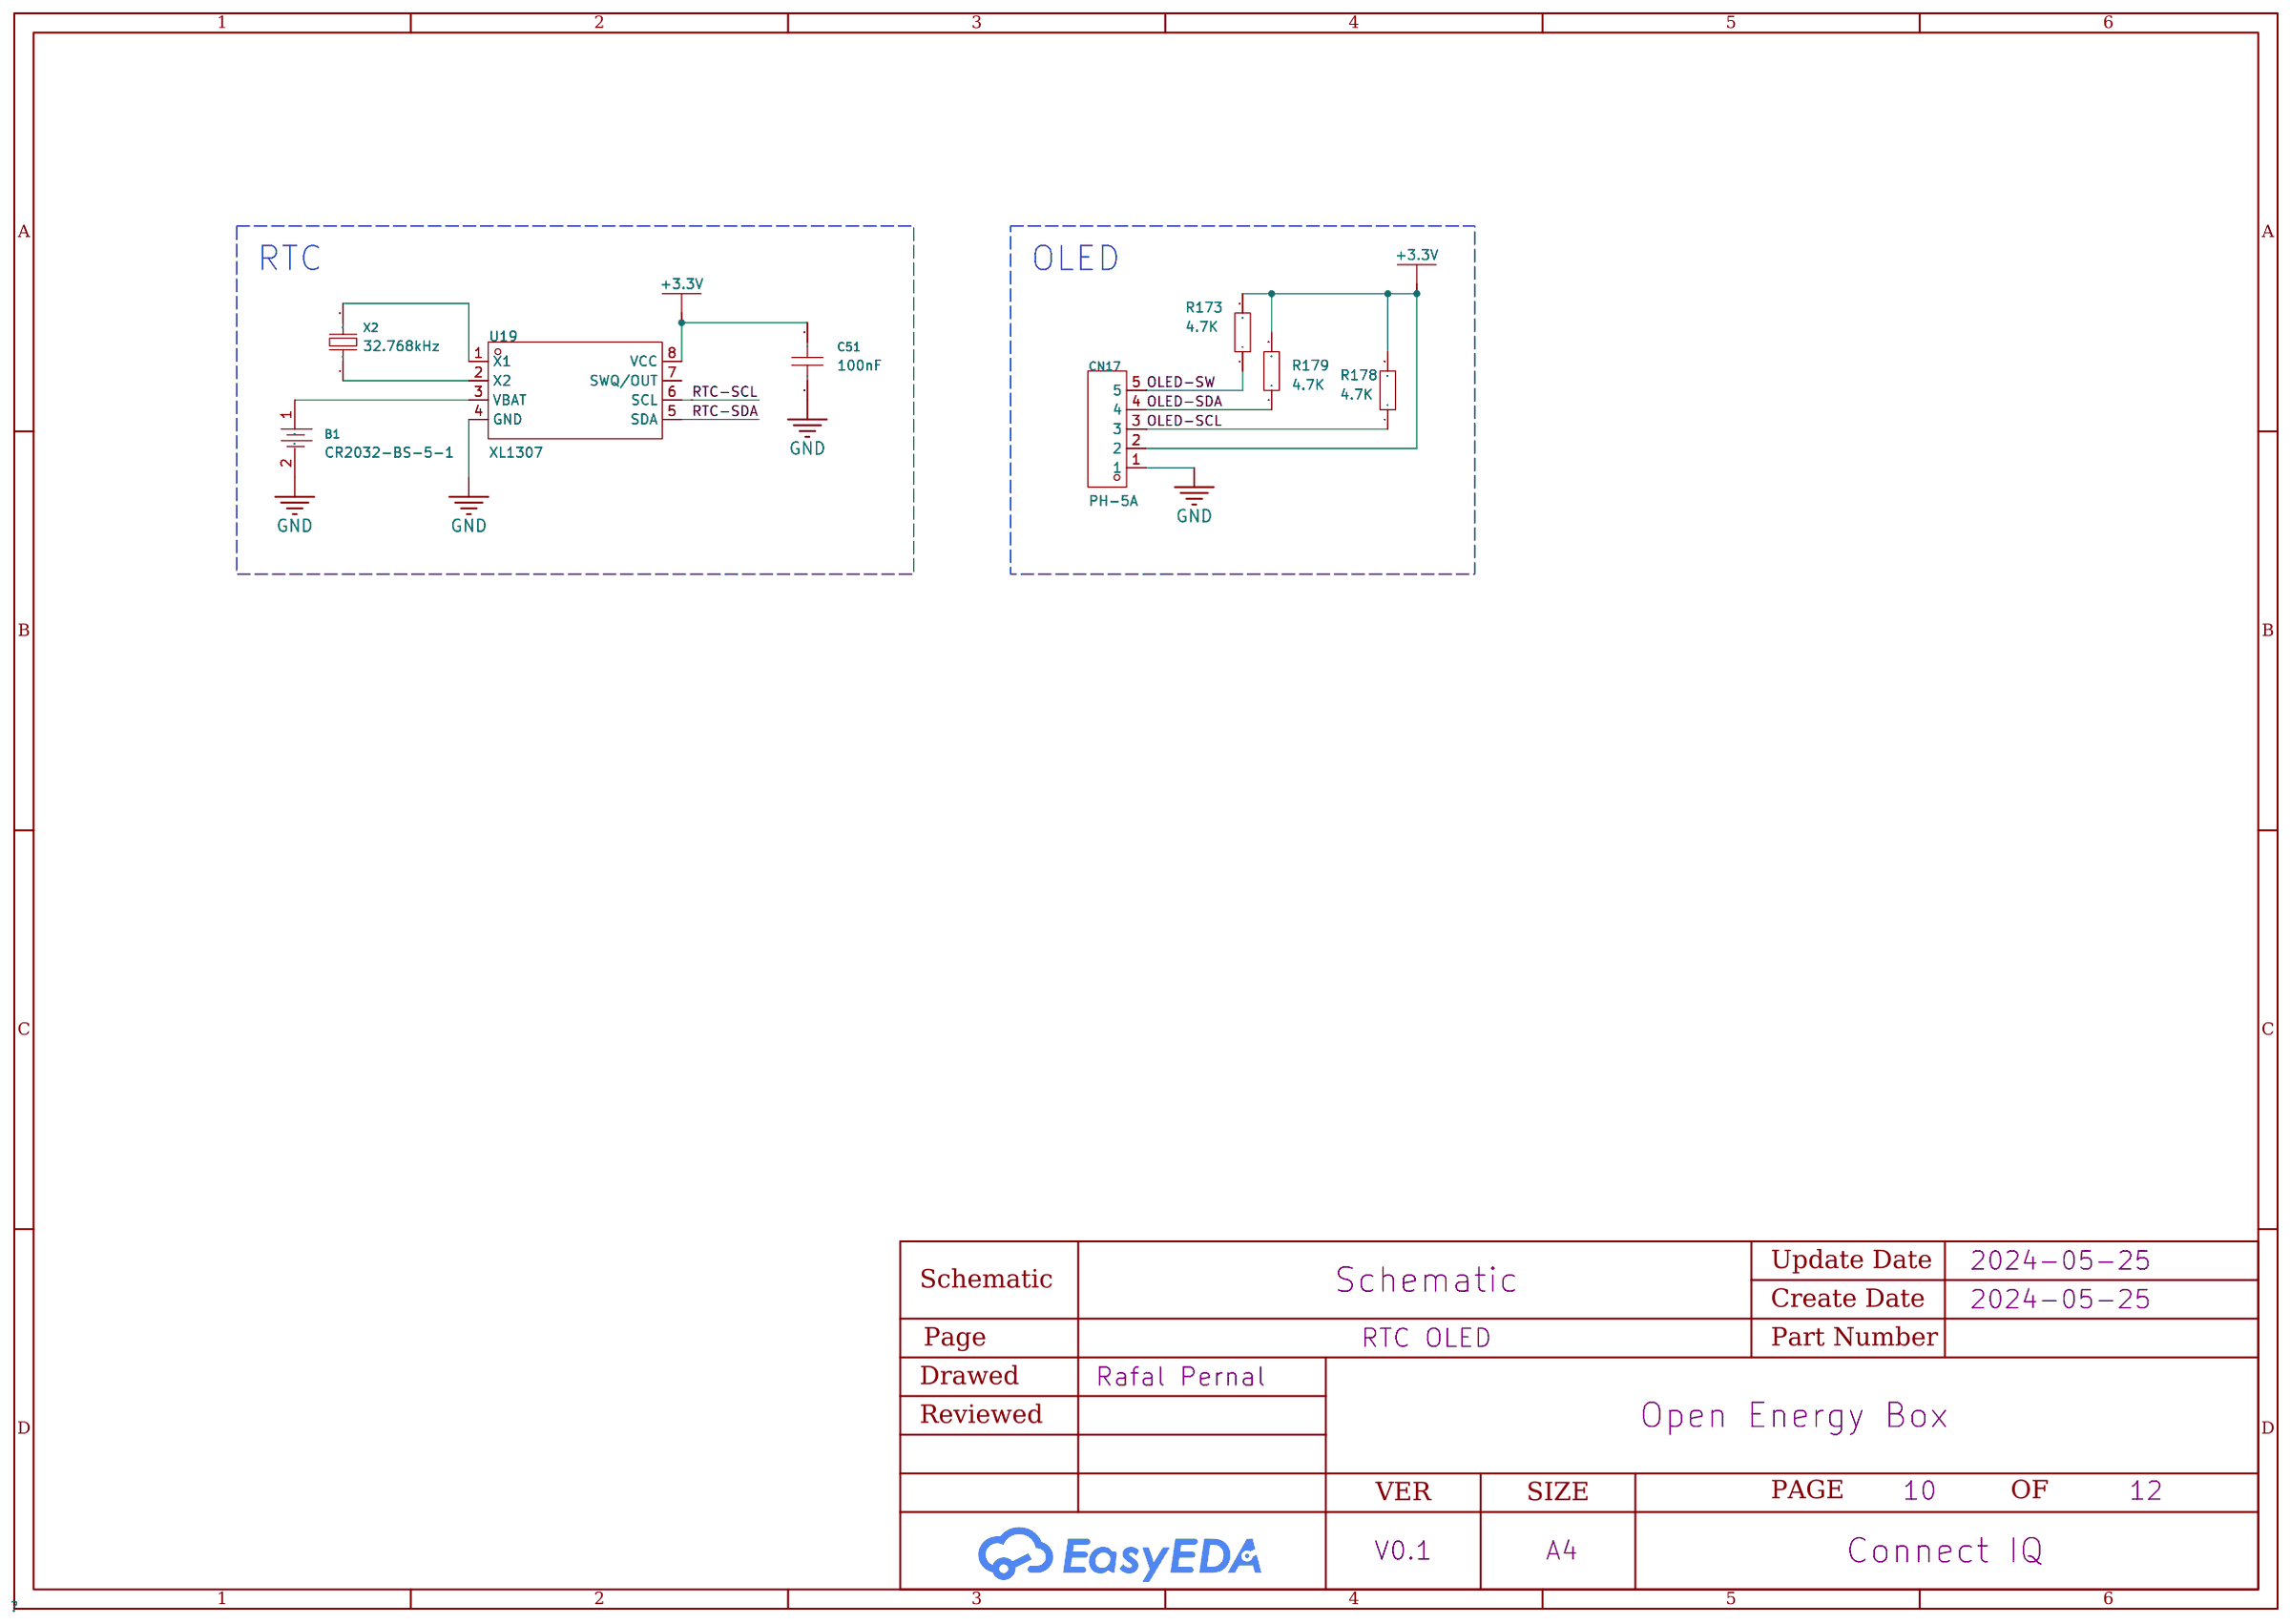
[diagram p9: RTC OLED]
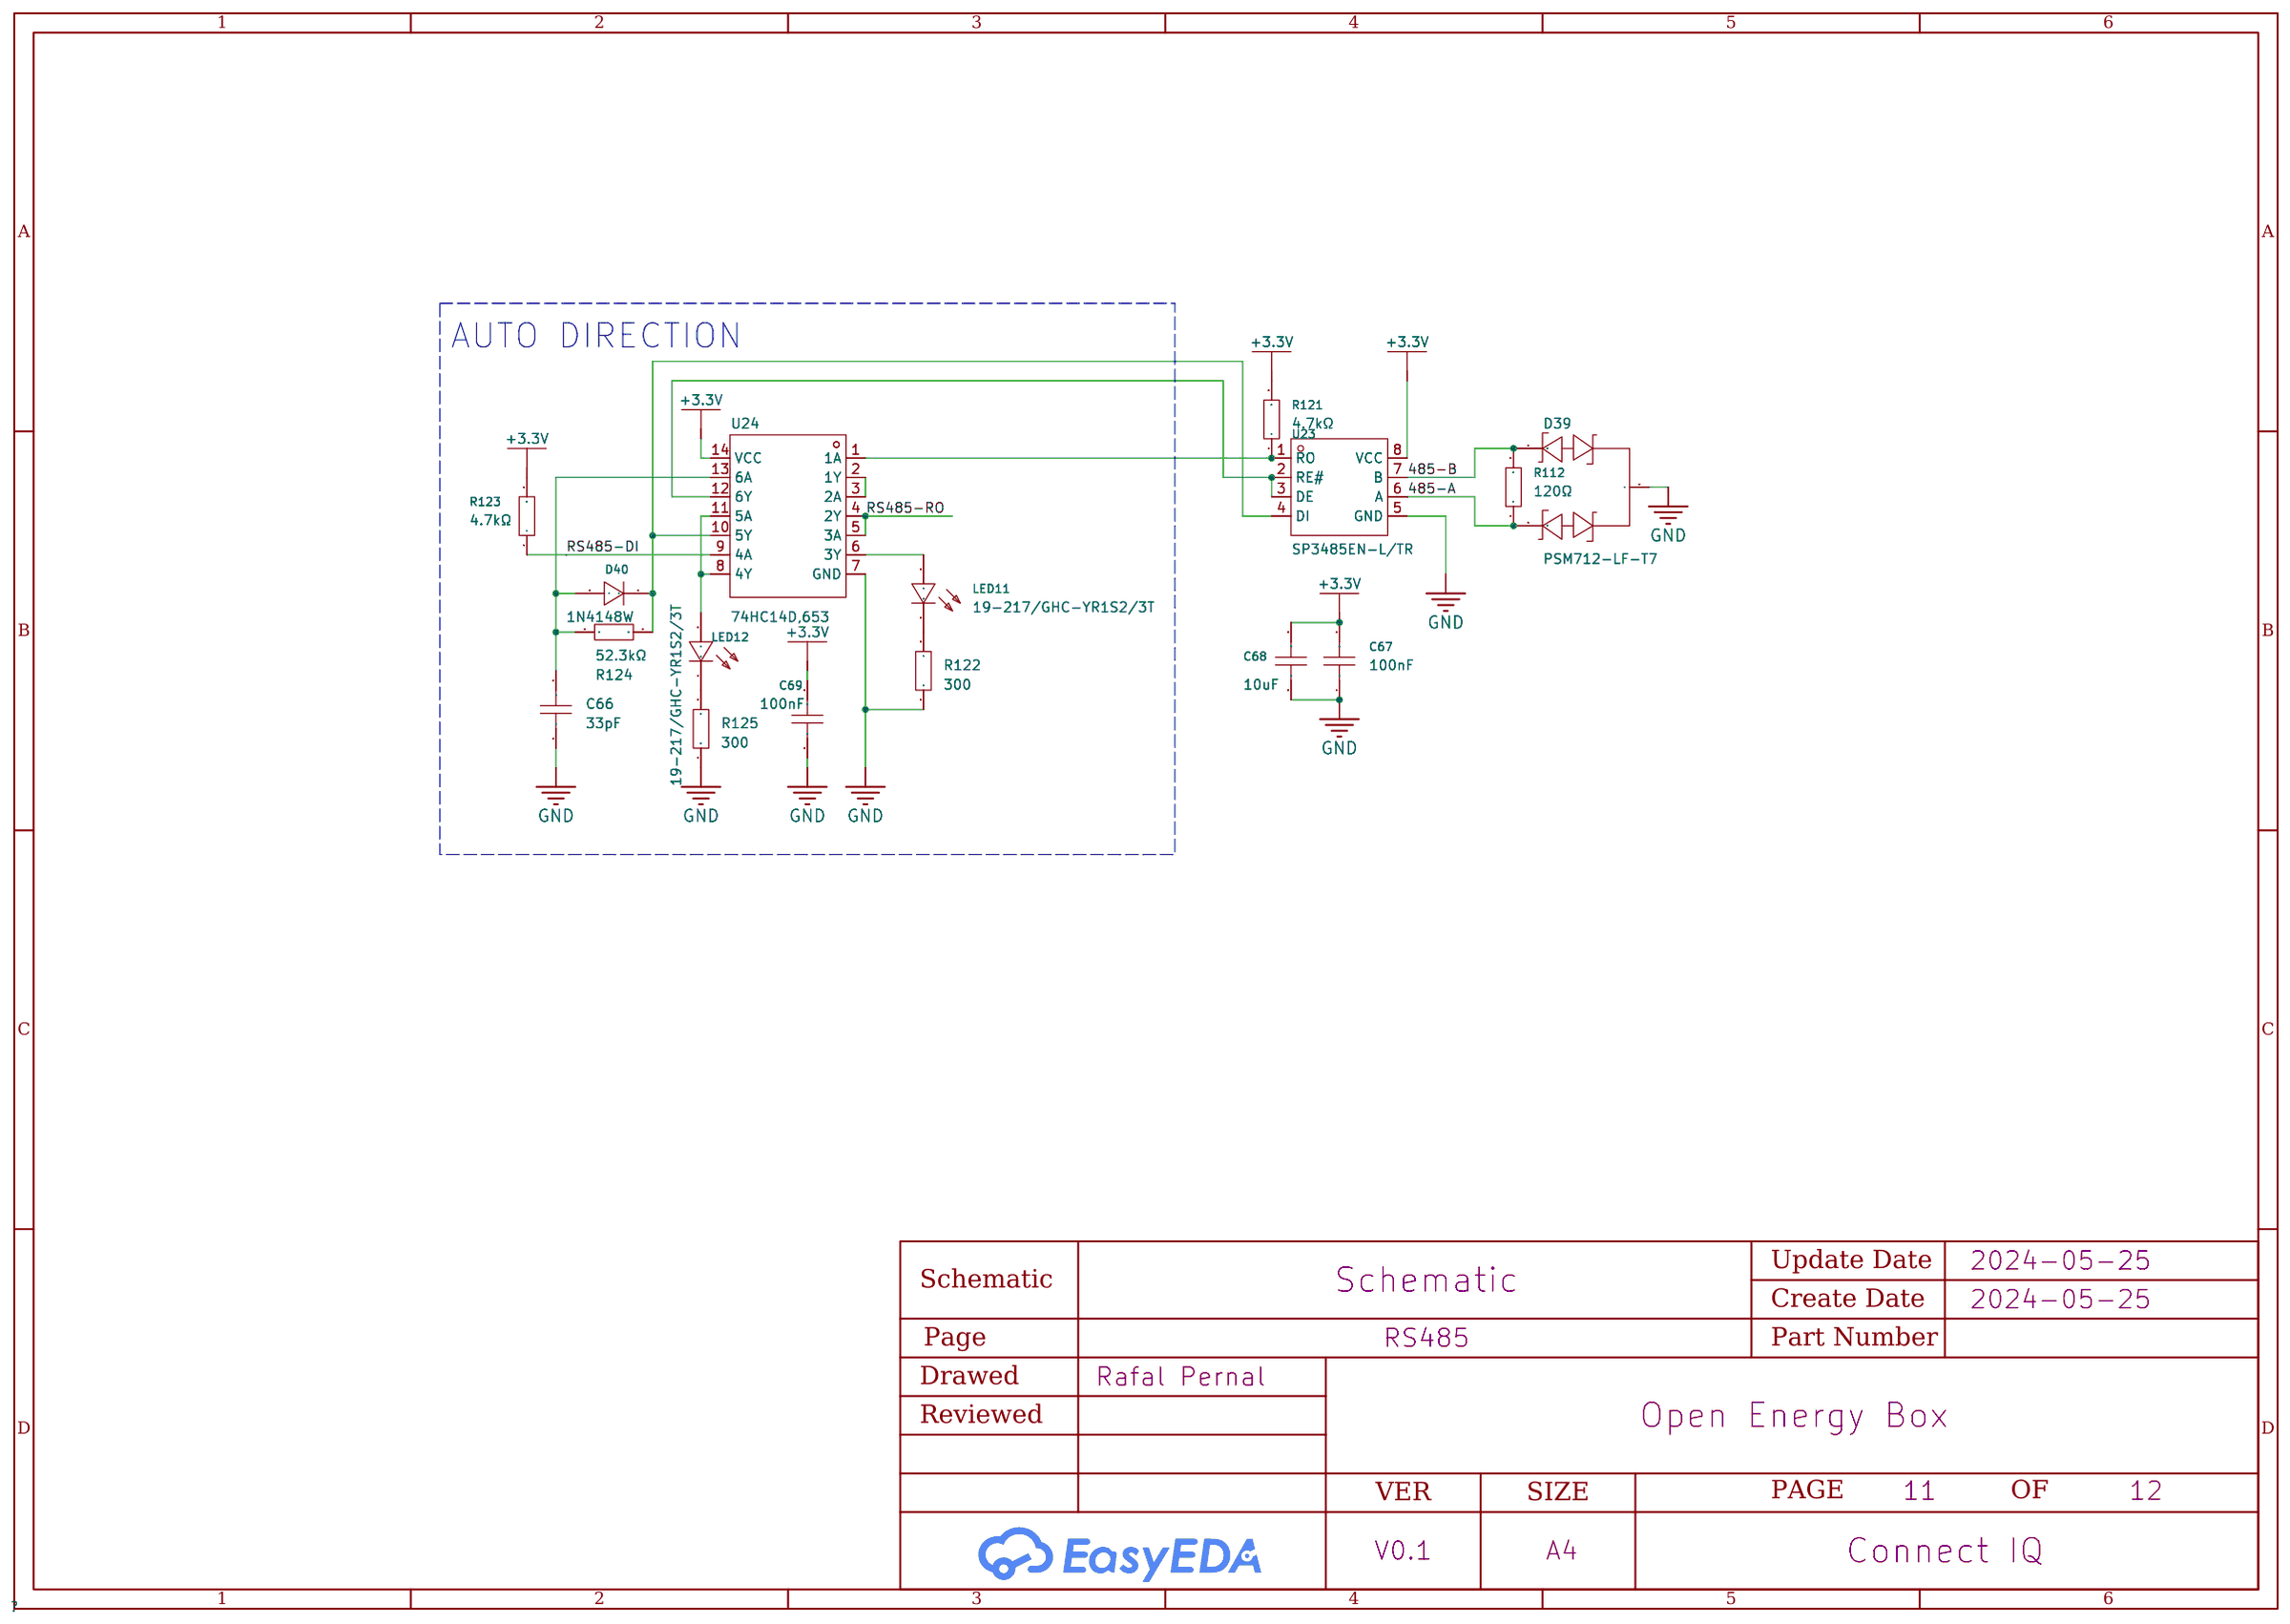
[diagram p10: RS485]
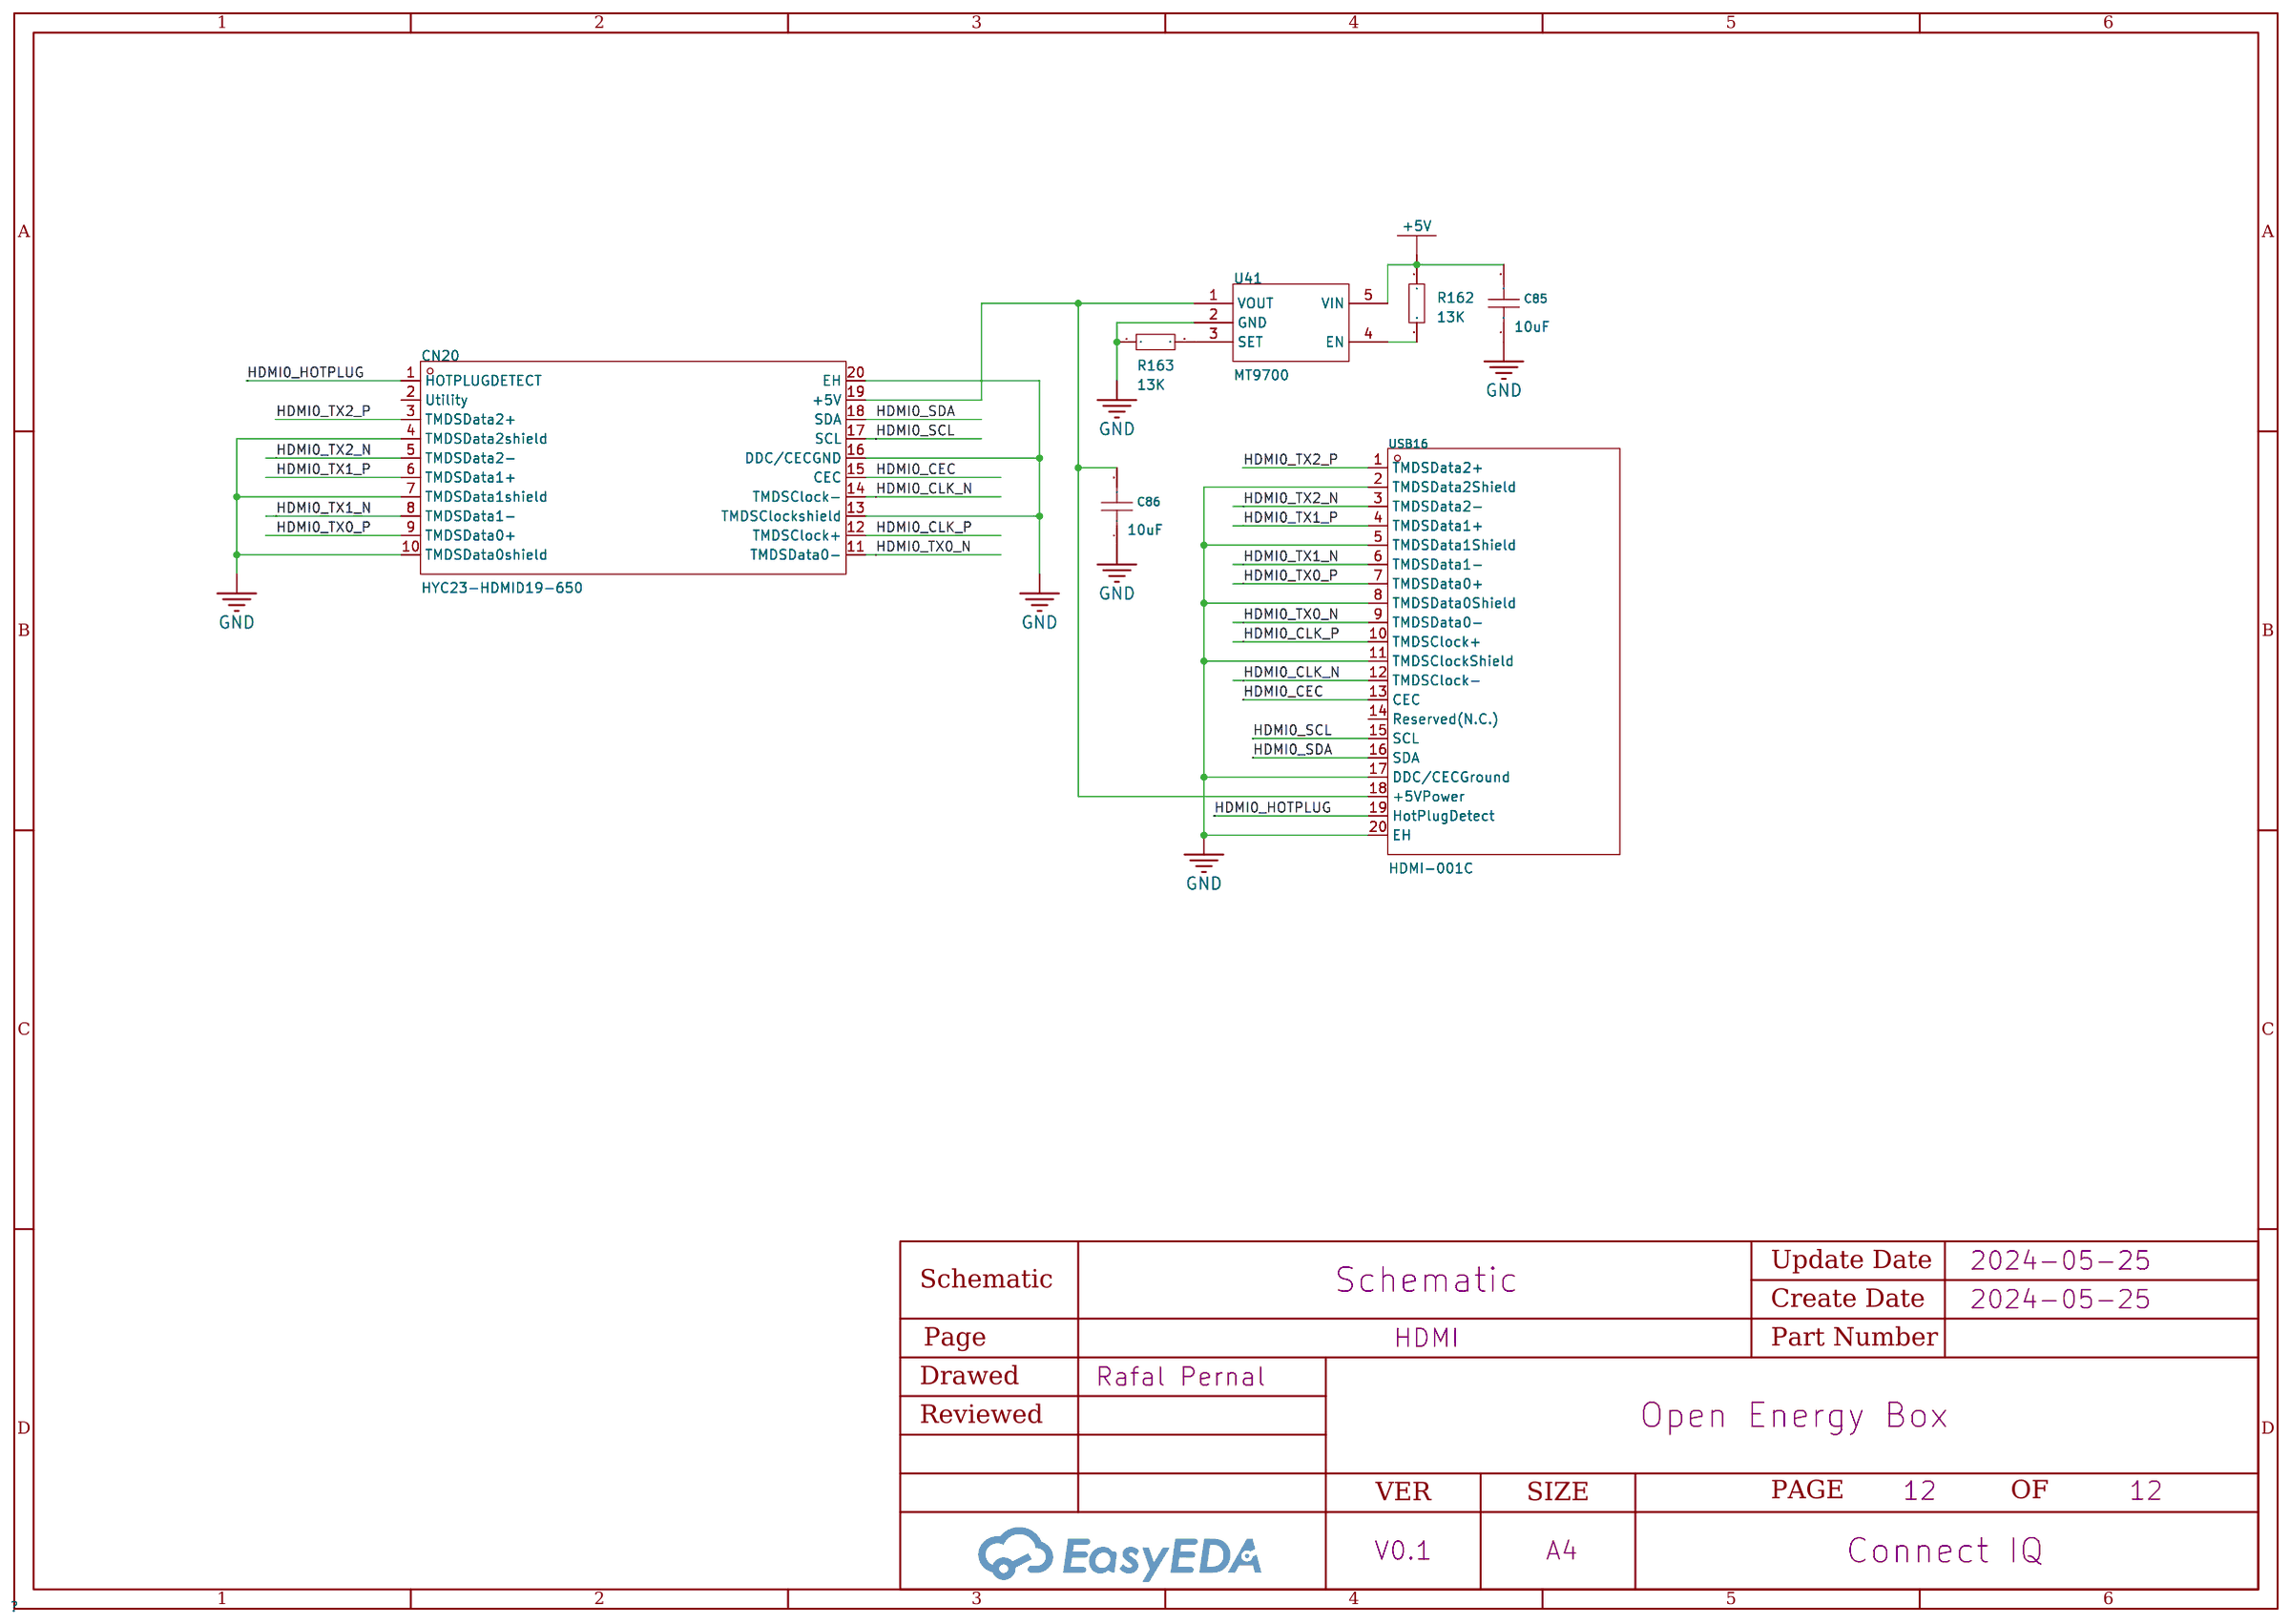
[diagram p11: HDMI]

(export (version "E")
  (design (tool "Eeschema 10.0.6"))
  (components
    (comp (ref "C18")
      (value "100nF")
      (footprint "easyedapro:C0603")
      (libsource (lib "easyedapro") (part "CAP"))
    )
    (comp (ref "C30")
      (value "10uF")
      (footprint "easyedapro:C0603")
      (fields
        (field (name "Manufacturer Part") "CL10A106KP8NNNC")
        (field (name "Manufacturer") "SAMSUNG(三星)")
      )
      (libsource (lib "easyedapro") (part "CL10A106KP8NNNC"))
    )
    (comp (ref "CARD1")
      (value "TF PUSH")
      (footprint "easyedapro:TF-SMD_TF-PUSH")
      (fields (field (name "Manufacturer") "SHOU HAN(首韩)"))
      (libsource (lib "easyedapro") (part "TF PUSH"))
    )
    (comp (ref "LED13")
      (value "19-217/GHC-YR1S2/3T")
      (footprint "easyedapro:LED0603-RD")
      (fields (field (name "Manufacturer") "EVERLIGHT(亿光)"))
      (libsource (lib "easyedapro") (part "19-217/GHC-YR1S2/3T"))
    )
    (comp (ref "LED14")
      (value "19-217/GHC-YR1S2/3T")
      (footprint "easyedapro:LED0603-RD")
      (fields (field (name "Manufacturer") "EVERLIGHT(亿光)"))
      (libsource (lib "easyedapro") (part "19-217/GHC-YR1S2/3T"))
    )
    (comp (ref "R126")
      (value "300")
      (footprint "easyedapro:R0603")
      (libsource (lib "easyedapro") (part "Res"))
    )
    (comp (ref "R172")
      (value "300")
      (footprint "easyedapro:R0603")
      (libsource (lib "easyedapro") (part "Res"))
    )
    (comp (ref "SW1")
      (value "MSS22D18G2 125")
      (footprint "easyedapro:SW-TH_SHOU_MSS22D18G2")
      (fields (field (name "Manufacturer") "SHOU HAN(首韩)"))
      (libsource (lib "easyedapro") (part "MSS22D18G2 125"))
    )
    (comp (ref "U45")
      (value "CM4 Left")
      (footprint "easyedapro:CM4 LEFT")
      (fields
        (field (name "Manufacturer Part") "DF40HC(3.0)-100DS-0.4V(51)")
        (field (name "Manufacturer") "Hirose")
      )
      (libsource (lib "easyedapro") (part "CM4 Left"))
    )
    (comp (ref "U46")
      (value "CM4 Right")
      (footprint "easyedapro:CM4 RIGHT")
      (fields
        (field (name "Manufacturer Part") "DF40C-100DS-0.4V(51)")
        (field (name "Manufacturer") "Hirose")
      )
      (libsource (lib "easyedapro") (part "CM4 Right"))
    )
    (comp (ref "C2")
      (value "10uF")
      (footprint "easyedapro:C1206")
      (fields
        (field (name "Manufacturer Part") "CL31A106KBHNNNE")
        (field (name "Manufacturer") "SAMSUNG(三星)")
      )
      (libsource (lib "easyedapro") (part "CL31A106KBHNNNE"))
    )
    (comp (ref "C3")
      (value "10uF")
      (footprint "easyedapro:C1206")
      (fields
        (field (name "Manufacturer Part") "CL31A106KBHNNNE")
        (field (name "Manufacturer") "SAMSUNG(三星)")
      )
      (libsource (lib "easyedapro") (part "CL31A106KBHNNNE"))
    )
    (comp (ref "C5")
      (value "3.3nF")
      (footprint "easyedapro:C0603")
      (libsource (lib "easyedapro") (part "CAP"))
    )
    (comp (ref "C6")
      (value "22uF")
      (footprint "easyedapro:C0805")
      (fields
        (field (name "Manufacturer Part") "CL21A226MAQNNNE")
        (field (name "Manufacturer") "SAMSUNG(三星)")
      )
      (libsource (lib "easyedapro") (part "CL21A226MAQNNNE"))
    )
    (comp (ref "C7")
      (value "22uF")
      (footprint "easyedapro:C0805")
      (fields
        (field (name "Manufacturer Part") "CL21A226MAQNNNE")
        (field (name "Manufacturer") "SAMSUNG(三星)")
      )
      (libsource (lib "easyedapro") (part "CL21A226MAQNNNE"))
    )
    (comp (ref "C44")
      (value "33pF")
      (footprint "easyedapro:C0603")
      (fields
        (field (name "Manufacturer Part") "CC0603KRX7R9BB104")
        (field (name "Manufacturer") "YAGEO(国巨)")
      )
      (libsource (lib "easyedapro") (part "CC0603KRX7R9BB104"))
    )
    (comp (ref "C45")
      (value "33pF")
      (footprint "easyedapro:C0603")
      (fields
        (field (name "Manufacturer Part") "CC0603KRX7R9BB104")
        (field (name "Manufacturer") "YAGEO(国巨)")
      )
      (libsource (lib "easyedapro") (part "CC0603KRX7R9BB104"))
    )
    (comp (ref "C46")
      (value "100nF")
      (footprint "easyedapro:C0603")
      (fields
        (field (name "Manufacturer Part") "CC0603KRX7R9BB104")
        (field (name "Manufacturer") "YAGEO(国巨)")
      )
      (libsource (lib "easyedapro") (part "CC0603KRX7R9BB104"))
    )
    (comp (ref "C52")
      (value "100nF")
      (footprint "easyedapro:C0603")
      (fields
        (field (name "Manufacturer Part") "CC0603KRX7R9BB104")
        (field (name "Manufacturer") "YAGEO(国巨)")
      )
      (libsource (lib "easyedapro") (part "CC0603KRX7R9BB104"))
    )
    (comp (ref "C88")
      (value "220uF")
      (footprint "easyedapro:CASE-B_3528")
      (fields
        (field (name "Manufacturer Part") "TLJB227M006R0500")
        (field (name "Manufacturer") "Kyocera AVX")
      )
      (libsource (lib "easyedapro") (part "TLJB227M006R0500"))
    )
    (comp (ref "C93")
      (value "33pF")
      (footprint "easyedapro:C0603")
      (fields
        (field (name "Manufacturer Part") "CC0603KRX7R9BB104")
        (field (name "Manufacturer") "YAGEO(国巨)")
      )
      (libsource (lib "easyedapro") (part "CC0603KRX7R9BB104"))
    )
    (comp (ref "C94")
      (value "100nF")
      (footprint "easyedapro:C0603")
      (fields
        (field (name "Manufacturer Part") "CC0603KRX7R9BB104")
        (field (name "Manufacturer") "YAGEO(国巨)")
      )
      (libsource (lib "easyedapro") (part "CC0603KRX7R9BB104"))
    )
    (comp (ref "C95")
      (value "220uF")
      (footprint "easyedapro:CASE-B_3528")
      (fields
        (field (name "Manufacturer Part") "TLJB227M006R0500")
        (field (name "Manufacturer") "Kyocera AVX")
      )
      (libsource (lib "easyedapro") (part "TLJB227M006R0500"))
    )
    (comp (ref "C97")
      (value "220nF")
      (footprint "easyedapro:C0603")
      (fields
        (field (name "Manufacturer Part") "CL10B224KA8NNNC")
        (field (name "Manufacturer") "SAMSUNG(三星)")
      )
      (libsource (lib "easyedapro") (part "CL10B224KA8NNNC"))
    )
    (comp (ref "C98")
      (value "10pF")
      (footprint "easyedapro:C0603")
      (fields
        (field (name "Manufacturer Part") "CC0603KRX7R9BB104")
        (field (name "Manufacturer") "YAGEO(国巨)")
      )
      (libsource (lib "easyedapro") (part "CC0603KRX7R9BB104"))
    )
    (comp (ref "C99")
      (value "1uF")
      (footprint "easyedapro:C0603")
      (fields
        (field (name "Manufacturer Part") "CL10A105KB8NNNC")
        (field (name "Manufacturer") "SAMSUNG(三星)")
      )
      (libsource (lib "easyedapro") (part "CL10A105KB8NNNC"))
    )
    (comp (ref "C100")
      (value "33pF")
      (footprint "easyedapro:C0603")
      (fields
        (field (name "Manufacturer Part") "CC0603KRX7R9BB104")
        (field (name "Manufacturer") "YAGEO(国巨)")
      )
      (libsource (lib "easyedapro") (part "CC0603KRX7R9BB104"))
    )
    (comp (ref "C101")
      (value "33pF")
      (footprint "easyedapro:C0603")
      (fields
        (field (name "Manufacturer Part") "CC0603KRX7R9BB104")
        (field (name "Manufacturer") "YAGEO(国巨)")
      )
      (libsource (lib "easyedapro") (part "CC0603KRX7R9BB104"))
    )
    (comp (ref "C102")
      (value "33pF")
      (footprint "easyedapro:C0603")
      (fields
        (field (name "Manufacturer Part") "CC0603KRX7R9BB104")
        (field (name "Manufacturer") "YAGEO(国巨)")
      )
      (libsource (lib "easyedapro") (part "CC0603KRX7R9BB104"))
    )
    (comp (ref "C103")
      (value "1uF")
      (footprint "easyedapro:C0603")
      (fields
        (field (name "Manufacturer Part") "CL10A105KB8NNNC")
        (field (name "Manufacturer") "SAMSUNG(三星)")
      )
      (libsource (lib "easyedapro") (part "CL10A105KB8NNNC"))
    )
    (comp (ref "C104")
      (value "10pF")
      (footprint "easyedapro:C0603")
      (fields
        (field (name "Manufacturer Part") "CC0603KRX7R9BB104")
        (field (name "Manufacturer") "YAGEO(国巨)")
      )
      (libsource (lib "easyedapro") (part "CC0603KRX7R9BB104"))
    )
    (comp (ref "C105")
      (value "22uF")
      (footprint "easyedapro:C0805")
      (fields
        (field (name "Manufacturer Part") "CL21A226MAQNNNE")
        (field (name "Manufacturer") "SAMSUNG(三星)")
      )
      (libsource (lib "easyedapro") (part "CL21A226MAQNNNE"))
    )
    (comp (ref "C106")
      (value "22uF")
      (footprint "easyedapro:C0805")
      (fields
        (field (name "Manufacturer Part") "CL21A226MAQNNNE")
        (field (name "Manufacturer") "SAMSUNG(三星)")
      )
      (libsource (lib "easyedapro") (part "CL21A226MAQNNNE"))
    )
    (comp (ref "CARD2")
      (value "SMC-202-6")
      (footprint "easyedapro:SIM-SMD_SMC-202-6")
      (fields (field (name "Manufacturer") "XUNPU(讯普)"))
      (libsource (lib "easyedapro") (part "SMC-202-6"))
    )
    (comp (ref "CN3")
      (value "AS0BC21-S40BB-7H")
      (footprint "easyedapro:CONN-SMD_AS0BC21-S30BB-7H")
      (fields (field (name "Manufacturer") "FOXCONN(富士康)"))
      (libsource (lib "easyedapro") (part "AS0BC21-S40BB-7H"))
    )
    (comp (ref "D43")
      (value "MM5Z4V7")
      (footprint "easyedapro:SOD-523_L1.2-W0.8-LS1.6-FD")
      (fields (field (name "Manufacturer") "CBI(创基)"))
      (libsource (lib "easyedapro") (part "MM5Z4V7 G8"))
    )
    (comp (ref "L1")
      (value "4.7uH")
      (footprint "easyedapro:IND-SMD_L7.1-W6.6")
      (fields
        (field (name "Manufacturer Part") "CMLO0650H4R7MTT")
        (field (name "Manufacturer") "Cybermax(思博科技)")
      )
      (libsource (lib "easyedapro") (part "CMLO0650H4R7MTT"))
    )
    (comp (ref "LED2")
      (value "~")
      (footprint "easyedapro:LED0603-R-RD")
      (libsource (lib "easyedapro") (part "LED_B"))
    )
    (comp (ref "LED8")
      (value "19-217/GHC-YR1S2/3T")
      (footprint "easyedapro:LED0603-RD")
      (fields (field (name "Manufacturer") "EVERLIGHT(亿光)"))
      (libsource (lib "easyedapro") (part "19-217/GHC-YR1S2/3T"))
    )
    (comp (ref "Q7")
      (value "~")
      (footprint "easyedapro:SOT-23-3_L2.9-W1.3-P1.90-LS2.4-BR")
      (libsource (lib "easyedapro") (part "N_MOS"))
    )
    (comp (ref "R4") (value "13K") (footprint "easyedapro:R0603") (libsource (lib "easyedapro") (part "Res")))
    (comp (ref "R5")
      (value "36.5K")
      (footprint "easyedapro:R0603")
      (libsource (lib "easyedapro") (part "Res"))
    )
    (comp (ref "R6") (value "10K") (footprint "easyedapro:R0603") (libsource (lib "easyedapro") (part "Res")))
    (comp (ref "R7") (value "300") (footprint "easyedapro:R0603") (libsource (lib "easyedapro") (part "Res")))
    (comp (ref "R8") (value "15k") (footprint "easyedapro:R0603") (libsource (lib "easyedapro") (part "Res")))
    (comp (ref "R10") (value "1k") (footprint "easyedapro:R0603") (libsource (lib "easyedapro") (part "Res")))
    (comp (ref "R11")
      (value "100K")
      (footprint "easyedapro:R0603")
      (libsource (lib "easyedapro") (part "Res"))
    )
    (comp (ref "R81")
      (value "137kΩ")
      (footprint "easyedapro:R0603")
      (fields
        (field (name "Manufacturer Part") "0603WAF1373T5E")
        (field (name "Manufacturer") "UNI-ROYAL(厚声)")
      )
      (libsource (lib "easyedapro") (part "0603WAF1373T5E"))
    )
    (comp (ref "R82")
      (value "137kΩ")
      (footprint "easyedapro:R0603")
      (fields
        (field (name "Manufacturer Part") "0603WAF1373T5E")
        (field (name "Manufacturer") "UNI-ROYAL(厚声)")
      )
      (libsource (lib "easyedapro") (part "0603WAF1373T5E"))
    )
    (comp (ref "R165")
      (value "NM")
      (footprint "easyedapro:R0603")
      (libsource (lib "easyedapro") (part "Res"))
    )
    (comp (ref "R166")
      (value "100K")
      (footprint "easyedapro:R0603")
      (libsource (lib "easyedapro") (part "Res"))
    )
    (comp (ref "R167")
      (value "22Ω")
      (footprint "easyedapro:R0603")
      (fields
        (field (name "Manufacturer Part") "0603WAF220JT5E")
        (field (name "Manufacturer") "UNI-ROYAL(厚声)")
      )
      (libsource (lib "easyedapro") (part "0603WAF220JT5E"))
    )
    (comp (ref "R168")
      (value "22Ω")
      (footprint "easyedapro:R0603")
      (fields
        (field (name "Manufacturer Part") "0603WAF220JT5E")
        (field (name "Manufacturer") "UNI-ROYAL(厚声)")
      )
      (libsource (lib "easyedapro") (part "0603WAF220JT5E"))
    )
    (comp (ref "R169")
      (value "22Ω")
      (footprint "easyedapro:R0603")
      (fields
        (field (name "Manufacturer Part") "0603WAF220JT5E")
        (field (name "Manufacturer") "UNI-ROYAL(厚声)")
      )
      (libsource (lib "easyedapro") (part "0603WAF220JT5E"))
    )
    (comp (ref "R170")
      (value "0R")
      (footprint "easyedapro:R0603")
      (libsource (lib "easyedapro") (part "Res"))
    )
    (comp (ref "R171")
      (value "0R")
      (footprint "easyedapro:R0603")
      (libsource (lib "easyedapro") (part "Res"))
    )
    (comp (ref "TP5")
      (value "~")
      (footprint "easyedapro:Test-Point-0.5mm")
      (description "Test Point 测试点")
      (libsource (lib "easyedapro") (part "Test-Point"))
    )
    (comp (ref "TP6")
      (value "~")
      (footprint "easyedapro:Test-Point-0.5mm")
      (description "Test Point 测试点")
      (libsource (lib "easyedapro") (part "Test-Point"))
    )
    (comp (ref "U3")
      (value "RT7272BGSP")
      (footprint "easyedapro:SOIC-8_L5.0-W4.0-P1.27-LS6.0-BL-EP2.0")
      (fields (field (name "Manufacturer") "RICHTEK(立锜)"))
      (libsource (lib "easyedapro") (part "RT7272BGSP"))
    )
    (comp (ref "U12")
      (value "SMTSO3025MTJ")
      (footprint "easyedapro:SMD_SMTSO3060CTJ")
      (fields (field (name "Manufacturer") "Sinhoo(雄和远景)"))
      (libsource (lib "easyedapro") (part "SMTSO3025MTJ"))
    )
    (comp (ref "U33")
      (value "TPD4EUSB30DQAR-N")
      (footprint "easyedapro:DFN-10_L2.5-W1.0-P0.50-BL-A")
      (fields (field (name "Manufacturer") "BORN(伯恩半导体)"))
      (libsource (lib "easyedapro") (part "TPD4EUSB30DQAR-N"))
    )
    (comp (ref "U48")
      (value "SMTSO3025MTJ")
      (footprint "easyedapro:SMD_SMTSO3060CTJ")
      (fields (field (name "Manufacturer") "Sinhoo(雄和远景)"))
      (libsource (lib "easyedapro") (part "SMTSO3025MTJ"))
    )
    (comp (ref "C11")
      (value "10uF")
      (footprint "easyedapro:C1206")
      (fields
        (field (name "Manufacturer Part") "CL31A106KBHNNNE")
        (field (name "Manufacturer") "SAMSUNG(三星)")
      )
      (libsource (lib "easyedapro") (part "CL31A106KBHNNNE"))
    )
    (comp (ref "C12")
      (value "10uF")
      (footprint "easyedapro:C1206")
      (fields
        (field (name "Manufacturer Part") "CL31A106KBHNNNE")
        (field (name "Manufacturer") "SAMSUNG(三星)")
      )
      (libsource (lib "easyedapro") (part "CL31A106KBHNNNE"))
    )
    (comp (ref "C13")
      (value "100nF")
      (footprint "easyedapro:C0603")
      (libsource (lib "easyedapro") (part "CAP"))
    )
    (comp (ref "C14")
      (value "3.3nF")
      (footprint "easyedapro:C0603")
      (libsource (lib "easyedapro") (part "CAP"))
    )
    (comp (ref "C15")
      (value "22uF")
      (footprint "easyedapro:C0805")
      (fields
        (field (name "Manufacturer Part") "CL21A226MAQNNNE")
        (field (name "Manufacturer") "SAMSUNG(三星)")
      )
      (libsource (lib "easyedapro") (part "CL21A226MAQNNNE"))
    )
    (comp (ref "C16")
      (value "22uF")
      (footprint "easyedapro:C0805")
      (fields
        (field (name "Manufacturer Part") "CL21A226MAQNNNE")
        (field (name "Manufacturer") "SAMSUNG(三星)")
      )
      (libsource (lib "easyedapro") (part "CL21A226MAQNNNE"))
    )
    (comp (ref "CN5")
      (value "APCI0113-P001A")
      (footprint "easyedapro:CONN-SMD_APCI0113-P001A")
      (fields (field (name "Manufacturer") "LOTES(嘉澤端子)"))
      (libsource (lib "easyedapro") (part "APCI0113-P001A"))
    )
    (comp (ref "L3")
      (value "4.7uH")
      (footprint "easyedapro:IND-SMD_L7.1-W6.6")
      (fields
        (field (name "Manufacturer Part") "CMLO0650H4R7MTT")
        (field (name "Manufacturer") "Cybermax(思博科技)")
      )
      (libsource (lib "easyedapro") (part "CMLO0650H4R7MTT"))
    )
    (comp (ref "LED9")
      (value "KT-0805Y")
      (footprint "easyedapro:LED0805-R-RD")
      (fields (field (name "Manufacturer") "KENTO"))
      (libsource (lib "easyedapro") (part "17-21SUYC/TR8"))
    )
    (comp (ref "LED10")
      (value "19-217/GHC-YR1S2/3T")
      (footprint "easyedapro:LED0603-RD")
      (fields (field (name "Manufacturer") "EVERLIGHT(亿光)"))
      (libsource (lib "easyedapro") (part "19-217/GHC-YR1S2/3T"))
    )
    (comp (ref "P4")
      (value "SMTSO3035CTJ")
      (footprint "easyedapro:SMD_BD5.6-D4.1")
      (fields (field (name "Manufacturer") "Sinhoo(雄和远景)"))
      (libsource (lib "easyedapro") (part "SMTSO3035CTJ"))
    )
    (comp (ref "R13") (value "1k") (footprint "easyedapro:R0603") (libsource (lib "easyedapro") (part "Res")))
    (comp (ref "R17")
      (value "13K")
      (footprint "easyedapro:R0603")
      (libsource (lib "easyedapro") (part "Res"))
    )
    (comp (ref "R18")
      (value "30.9K")
      (footprint "easyedapro:R0603")
      (libsource (lib "easyedapro") (part "Res"))
    )
    (comp (ref "R19")
      (value "10K")
      (footprint "easyedapro:R0603")
      (libsource (lib "easyedapro") (part "Res"))
    )
    (comp (ref "R20")
      (value "300")
      (footprint "easyedapro:R0603")
      (libsource (lib "easyedapro") (part "Res"))
    )
    (comp (ref "R83")
      (value "137kΩ")
      (footprint "easyedapro:R0603")
      (fields
        (field (name "Manufacturer Part") "0603WAF1373T5E")
        (field (name "Manufacturer") "UNI-ROYAL(厚声)")
      )
      (libsource (lib "easyedapro") (part "0603WAF1373T5E"))
    )
    (comp (ref "R84")
      (value "137kΩ")
      (footprint "easyedapro:R0603")
      (fields
        (field (name "Manufacturer Part") "0603WAF1373T5E")
        (field (name "Manufacturer") "UNI-ROYAL(厚声)")
      )
      (libsource (lib "easyedapro") (part "0603WAF1373T5E"))
    )
    (comp (ref "U4")
      (value "RT7272BGSP")
      (footprint "easyedapro:SOIC-8_L5.0-W4.0-P1.27-LS6.0-BL-EP2.0")
      (fields (field (name "Manufacturer") "RICHTEK(立锜)"))
      (libsource (lib "easyedapro") (part "RT7272BGSP"))
    )
    (comp (ref "C31")
      (value "100nF")
      (footprint "easyedapro:C0603")
      (libsource (lib "easyedapro") (part "CAP"))
    )
    (comp (ref "FPC8")
      (value "AFC11-S22ICC-00")
      (footprint "easyedapro:FPC-SMD_22P-P1.00_AFC11-S22ICC-00")
      (fields (field (name "Manufacturer") "JS(钜硕电子)"))
      (libsource (lib "easyedapro") (part "AFC11-S22ICC-00_C11074"))
    )
    (comp (ref "C53")
      (value "100nF")
      (footprint "easyedapro:C0603")
      (fields
        (field (name "Manufacturer Part") "CC0603KRX7R9BB104")
        (field (name "Manufacturer") "YAGEO(国巨)")
      )
      (libsource (lib "easyedapro") (part "CC0603KRX7R9BB104"))
    )
    (comp (ref "C54")
      (value "100nF")
      (footprint "easyedapro:C0603")
      (fields
        (field (name "Manufacturer Part") "CC0603KRX7R9BB104")
        (field (name "Manufacturer") "YAGEO(国巨)")
      )
      (libsource (lib "easyedapro") (part "CC0603KRX7R9BB104"))
    )
    (comp (ref "C57")
      (value "100nF")
      (footprint "easyedapro:C0603")
      (fields
        (field (name "Manufacturer Part") "CC0603KRX7R9BB104")
        (field (name "Manufacturer") "YAGEO(国巨)")
      )
      (libsource (lib "easyedapro") (part "CC0603KRX7R9BB104"))
    )
    (comp (ref "C58")
      (value "100nF")
      (footprint "easyedapro:C0603")
      (fields
        (field (name "Manufacturer Part") "CC0603KRX7R9BB104")
        (field (name "Manufacturer") "YAGEO(国巨)")
      )
      (libsource (lib "easyedapro") (part "CC0603KRX7R9BB104"))
    )
    (comp (ref "C59")
      (value "100nF")
      (footprint "easyedapro:C0603")
      (fields
        (field (name "Manufacturer Part") "CC0603KRX7R9BB104")
        (field (name "Manufacturer") "YAGEO(国巨)")
      )
      (libsource (lib "easyedapro") (part "CC0603KRX7R9BB104"))
    )
    (comp (ref "C60")
      (value "100nF")
      (footprint "easyedapro:C0603")
      (fields
        (field (name "Manufacturer Part") "CC0603KRX7R9BB104")
        (field (name "Manufacturer") "YAGEO(国巨)")
      )
      (libsource (lib "easyedapro") (part "CC0603KRX7R9BB104"))
    )
    (comp (ref "C61")
      (value "100nF")
      (footprint "easyedapro:C0603")
      (fields
        (field (name "Manufacturer Part") "CC0603KRX7R9BB104")
        (field (name "Manufacturer") "YAGEO(国巨)")
      )
      (libsource (lib "easyedapro") (part "CC0603KRX7R9BB104"))
    )
    (comp (ref "C62")
      (value "100nF")
      (footprint "easyedapro:C0603")
      (fields
        (field (name "Manufacturer Part") "CC0603KRX7R9BB104")
        (field (name "Manufacturer") "YAGEO(国巨)")
      )
      (libsource (lib "easyedapro") (part "CC0603KRX7R9BB104"))
    )
    (comp (ref "C63")
      (value "10uF")
      (footprint "easyedapro:C0603")
      (fields
        (field (name "Manufacturer Part") "CL10A106KP8NNNC")
        (field (name "Manufacturer") "SAMSUNG(三星)")
      )
      (libsource (lib "easyedapro") (part "CL10A106KP8NNNC"))
    )
    (comp (ref "CN10")
      (value "DB2ERC-2.54-12P-GN")
      (footprint "easyedapro:CONN-TH_12P-P2.54_DIBO_DB2ERC-2.54-12P-GN")
      (fields (field (name "Manufacturer") "DIBO(地博电气)"))
      (libsource (lib "easyedapro") (part "DB2ERC-2.54-12P-GN"))
    )
    (comp (ref "D1")
      (value "ESD0603E002M05")
      (footprint "easyedapro:D0603-BI")
      (fields (field (name "Manufacturer") "TWGMC(台湾迪嘉)"))
      (libsource (lib "easyedapro") (part "ESD0603E002M05"))
    )
    (comp (ref "D2")
      (value "ESD0603E002M05")
      (footprint "easyedapro:D0603-BI")
      (fields (field (name "Manufacturer") "TWGMC(台湾迪嘉)"))
      (libsource (lib "easyedapro") (part "ESD0603E002M05"))
    )
    (comp (ref "D3")
      (value "ESD0603E002M05")
      (footprint "easyedapro:D0603-BI")
      (fields (field (name "Manufacturer") "TWGMC(台湾迪嘉)"))
      (libsource (lib "easyedapro") (part "ESD0603E002M05"))
    )
    (comp (ref "D4")
      (value "ESD0603E002M05")
      (footprint "easyedapro:D0603-BI")
      (fields (field (name "Manufacturer") "TWGMC(台湾迪嘉)"))
      (libsource (lib "easyedapro") (part "ESD0603E002M05"))
    )
    (comp (ref "D5")
      (value "BV-SMAJ30CA")
      (footprint "easyedapro:SMA_L4.4-W2.6-LS5.0-BI")
      (fields (field (name "Manufacturer") "Bencent(槟城)"))
      (libsource (lib "easyedapro") (part "BV-SMAJ30CA"))
    )
    (comp (ref "D6")
      (value "BV-SMAJ30CA")
      (footprint "easyedapro:SMA_L4.4-W2.6-LS5.0-BI")
      (fields (field (name "Manufacturer") "Bencent(槟城)"))
      (libsource (lib "easyedapro") (part "BV-SMAJ30CA"))
    )
    (comp (ref "D27")
      (value "ESD0603E002M05")
      (footprint "easyedapro:D0603-BI")
      (fields (field (name "Manufacturer") "TWGMC(台湾迪嘉)"))
      (libsource (lib "easyedapro") (part "ESD0603E002M05"))
    )
    (comp (ref "D28")
      (value "ESD0603E002M05")
      (footprint "easyedapro:D0603-BI")
      (fields (field (name "Manufacturer") "TWGMC(台湾迪嘉)"))
      (libsource (lib "easyedapro") (part "ESD0603E002M05"))
    )
    (comp (ref "D29")
      (value "ESD0603E002M05")
      (footprint "easyedapro:D0603-BI")
      (fields (field (name "Manufacturer") "TWGMC(台湾迪嘉)"))
      (libsource (lib "easyedapro") (part "ESD0603E002M05"))
    )
    (comp (ref "D30")
      (value "ESD0603E002M05")
      (footprint "easyedapro:D0603-BI")
      (fields (field (name "Manufacturer") "TWGMC(台湾迪嘉)"))
      (libsource (lib "easyedapro") (part "ESD0603E002M05"))
    )
    (comp (ref "D31")
      (value "BV-SMAJ30CA")
      (footprint "easyedapro:SMA_L4.4-W2.6-LS5.0-BI")
      (fields (field (name "Manufacturer") "Bencent(槟城)"))
      (libsource (lib "easyedapro") (part "BV-SMAJ30CA"))
    )
    (comp (ref "D32")
      (value "BV-SMAJ30CA")
      (footprint "easyedapro:SMA_L4.4-W2.6-LS5.0-BI")
      (fields (field (name "Manufacturer") "Bencent(槟城)"))
      (libsource (lib "easyedapro") (part "BV-SMAJ30CA"))
    )
    (comp (ref "D33")
      (value "ESD0603E002M05")
      (footprint "easyedapro:D0603-BI")
      (fields (field (name "Manufacturer") "TWGMC(台湾迪嘉)"))
      (libsource (lib "easyedapro") (part "ESD0603E002M05"))
    )
    (comp (ref "D34")
      (value "ESD0603E002M05")
      (footprint "easyedapro:D0603-BI")
      (fields (field (name "Manufacturer") "TWGMC(台湾迪嘉)"))
      (libsource (lib "easyedapro") (part "ESD0603E002M05"))
    )
    (comp (ref "D35")
      (value "ESD0603E002M05")
      (footprint "easyedapro:D0603-BI")
      (fields (field (name "Manufacturer") "TWGMC(台湾迪嘉)"))
      (libsource (lib "easyedapro") (part "ESD0603E002M05"))
    )
    (comp (ref "D36")
      (value "ESD0603E002M05")
      (footprint "easyedapro:D0603-BI")
      (fields (field (name "Manufacturer") "TWGMC(台湾迪嘉)"))
      (libsource (lib "easyedapro") (part "ESD0603E002M05"))
    )
    (comp (ref "D37")
      (value "BV-SMAJ30CA")
      (footprint "easyedapro:SMA_L4.4-W2.6-LS5.0-BI")
      (fields (field (name "Manufacturer") "Bencent(槟城)"))
      (libsource (lib "easyedapro") (part "BV-SMAJ30CA"))
    )
    (comp (ref "D38")
      (value "BV-SMAJ30CA")
      (footprint "easyedapro:SMA_L4.4-W2.6-LS5.0-BI")
      (fields (field (name "Manufacturer") "Bencent(槟城)"))
      (libsource (lib "easyedapro") (part "BV-SMAJ30CA"))
    )
    (comp (ref "R35")
      (value "249kΩ")
      (footprint "easyedapro:R1206")
      (fields (field (name "Manufacturer Part") "RTT062493FTP") (field (name "Manufacturer") "RALEC(旺诠)"))
      (libsource (lib "easyedapro") (part "RTT062493FTP"))
    )
    (comp (ref "R85")
      (value "137kΩ")
      (footprint "easyedapro:R0603")
      (fields
        (field (name "Manufacturer Part") "0603WAF1373T5E")
        (field (name "Manufacturer") "UNI-ROYAL(厚声)")
      )
      (libsource (lib "easyedapro") (part "0603WAF1373T5E"))
    )
    (comp (ref "R86")
      (value "137kΩ")
      (footprint "easyedapro:R0603")
      (fields
        (field (name "Manufacturer Part") "0603WAF1373T5E")
        (field (name "Manufacturer") "UNI-ROYAL(厚声)")
      )
      (libsource (lib "easyedapro") (part "0603WAF1373T5E"))
    )
    (comp (ref "R87")
      (value "100Ω")
      (footprint "easyedapro:R0603")
      (fields
        (field (name "Manufacturer Part") "0603WAF1000T5E")
        (field (name "Manufacturer") "UNI-ROYAL(厚声)")
      )
      (libsource (lib "easyedapro") (part "0603WAF1000T5E"))
    )
    (comp (ref "R88")
      (value "100Ω")
      (footprint "easyedapro:R0603")
      (fields
        (field (name "Manufacturer Part") "0603WAF1000T5E")
        (field (name "Manufacturer") "UNI-ROYAL(厚声)")
      )
      (libsource (lib "easyedapro") (part "0603WAF1000T5E"))
    )
    (comp (ref "R89")
      (value "33kΩ")
      (footprint "easyedapro:R0603")
      (fields
        (field (name "Manufacturer Part") "0603WAF3302T5E")
        (field (name "Manufacturer") "UNI-ROYAL(厚声)")
      )
      (libsource (lib "easyedapro") (part "0603WAF3302T5E"))
    )
    (comp (ref "R90")
      (value "33kΩ")
      (footprint "easyedapro:R0603")
      (fields
        (field (name "Manufacturer Part") "0603WAF3302T5E")
        (field (name "Manufacturer") "UNI-ROYAL(厚声)")
      )
      (libsource (lib "easyedapro") (part "0603WAF3302T5E"))
    )
    (comp (ref "R98")
      (value "249kΩ")
      (footprint "easyedapro:R1206")
      (fields (field (name "Manufacturer Part") "RTT062493FTP") (field (name "Manufacturer") "RALEC(旺诠)"))
      (libsource (lib "easyedapro") (part "RTT062493FTP"))
    )
    (comp (ref "R99")
      (value "137kΩ")
      (footprint "easyedapro:R0603")
      (fields
        (field (name "Manufacturer Part") "0603WAF1373T5E")
        (field (name "Manufacturer") "UNI-ROYAL(厚声)")
      )
      (libsource (lib "easyedapro") (part "0603WAF1373T5E"))
    )
    (comp (ref "R100")
      (value "137kΩ")
      (footprint "easyedapro:R0603")
      (fields
        (field (name "Manufacturer Part") "0603WAF1373T5E")
        (field (name "Manufacturer") "UNI-ROYAL(厚声)")
      )
      (libsource (lib "easyedapro") (part "0603WAF1373T5E"))
    )
    (comp (ref "R101")
      (value "100Ω")
      (footprint "easyedapro:R0603")
      (fields
        (field (name "Manufacturer Part") "0603WAF1000T5E")
        (field (name "Manufacturer") "UNI-ROYAL(厚声)")
      )
      (libsource (lib "easyedapro") (part "0603WAF1000T5E"))
    )
    (comp (ref "R102")
      (value "100Ω")
      (footprint "easyedapro:R0603")
      (fields
        (field (name "Manufacturer Part") "0603WAF1000T5E")
        (field (name "Manufacturer") "UNI-ROYAL(厚声)")
      )
      (libsource (lib "easyedapro") (part "0603WAF1000T5E"))
    )
    (comp (ref "R103")
      (value "33kΩ")
      (footprint "easyedapro:R0603")
      (fields
        (field (name "Manufacturer Part") "0603WAF3302T5E")
        (field (name "Manufacturer") "UNI-ROYAL(厚声)")
      )
      (libsource (lib "easyedapro") (part "0603WAF3302T5E"))
    )
    (comp (ref "R104")
      (value "33kΩ")
      (footprint "easyedapro:R0603")
      (fields
        (field (name "Manufacturer Part") "0603WAF3302T5E")
        (field (name "Manufacturer") "UNI-ROYAL(厚声)")
      )
      (libsource (lib "easyedapro") (part "0603WAF3302T5E"))
    )
    (comp (ref "R105")
      (value "249kΩ")
      (footprint "easyedapro:R1206")
      (fields (field (name "Manufacturer Part") "RTT062493FTP") (field (name "Manufacturer") "RALEC(旺诠)"))
      (libsource (lib "easyedapro") (part "RTT062493FTP"))
    )
    (comp (ref "R106")
      (value "137kΩ")
      (footprint "easyedapro:R0603")
      (fields
        (field (name "Manufacturer Part") "0603WAF1373T5E")
        (field (name "Manufacturer") "UNI-ROYAL(厚声)")
      )
      (libsource (lib "easyedapro") (part "0603WAF1373T5E"))
    )
    (comp (ref "R107")
      (value "137kΩ")
      (footprint "easyedapro:R0603")
      (fields
        (field (name "Manufacturer Part") "0603WAF1373T5E")
        (field (name "Manufacturer") "UNI-ROYAL(厚声)")
      )
      (libsource (lib "easyedapro") (part "0603WAF1373T5E"))
    )
    (comp (ref "R108")
      (value "100Ω")
      (footprint "easyedapro:R0603")
      (fields
        (field (name "Manufacturer Part") "0603WAF1000T5E")
        (field (name "Manufacturer") "UNI-ROYAL(厚声)")
      )
      (libsource (lib "easyedapro") (part "0603WAF1000T5E"))
    )
    (comp (ref "R109")
      (value "100Ω")
      (footprint "easyedapro:R0603")
      (fields
        (field (name "Manufacturer Part") "0603WAF1000T5E")
        (field (name "Manufacturer") "UNI-ROYAL(厚声)")
      )
      (libsource (lib "easyedapro") (part "0603WAF1000T5E"))
    )
    (comp (ref "R110")
      (value "33kΩ")
      (footprint "easyedapro:R0603")
      (fields
        (field (name "Manufacturer Part") "0603WAF3302T5E")
        (field (name "Manufacturer") "UNI-ROYAL(厚声)")
      )
      (libsource (lib "easyedapro") (part "0603WAF3302T5E"))
    )
    (comp (ref "R111")
      (value "33kΩ")
      (footprint "easyedapro:R0603")
      (fields
        (field (name "Manufacturer Part") "0603WAF3302T5E")
        (field (name "Manufacturer") "UNI-ROYAL(厚声)")
      )
      (libsource (lib "easyedapro") (part "0603WAF3302T5E"))
    )
    (comp (ref "R137")
      (value "4.7kΩ")
      (footprint "easyedapro:R0603")
      (fields
        (field (name "Manufacturer Part") "0603WAF4701T5E")
        (field (name "Manufacturer") "UNI-ROYAL(厚声)")
      )
      (libsource (lib "easyedapro") (part "0603WAF4701T5E"))
    )
    (comp (ref "R138")
      (value "4.7kΩ")
      (footprint "easyedapro:R0603")
      (fields
        (field (name "Manufacturer Part") "0603WAF4701T5E")
        (field (name "Manufacturer") "UNI-ROYAL(厚声)")
      )
      (libsource (lib "easyedapro") (part "0603WAF4701T5E"))
    )
    (comp (ref "U8")
      (value "ADS1015IDGSR")
      (footprint "easyedapro:VSSOP-10_L3.0-W3.0-P0.50-LS4.9-BL")
      (fields (field (name "Manufacturer") "TI(德州仪器)"))
      (libsource (lib "easyedapro") (part "ADS1015IDGSR"))
    )
    (comp (ref "U22")
      (value "LM324DT")
      (footprint "easyedapro:SOIC-14_L8.7-W3.9-P1.27-LS6.0-BL")
      (fields (field (name "Manufacturer") "ST(意法半导体)"))
      (libsource (lib "easyedapro") (part "LM324DT"))
    )
    (comp (ref "C47")
      (value "100nF")
      (footprint "easyedapro:C0603")
      (libsource (lib "easyedapro") (part "CAP"))
    )
    (comp (ref "C48")
      (value "100nF")
      (footprint "easyedapro:C0603")
      (libsource (lib "easyedapro") (part "CAP"))
    )
    (comp (ref "C49")
      (value "100nF")
      (footprint "easyedapro:C0603")
      (libsource (lib "easyedapro") (part "CAP"))
    )
    (comp (ref "C50")
      (value "100nF")
      (footprint "easyedapro:C0603")
      (libsource (lib "easyedapro") (part "CAP"))
    )
    (comp (ref "CN7")
      (value "XY2500R-G-3.5-10P")
      (footprint "easyedapro:CONN-TH_XY2500R-G-3.5-10P")
      (fields (field (name "Manufacturer") "XINLAIYA(新莱亚)"))
      (libsource (lib "easyedapro") (part "XY2500R-G-3.5-10P"))
    )
    (comp (ref "R70")
      (value "510Ω")
      (footprint "easyedapro:R0603")
      (fields
        (field (name "Manufacturer Part") "0603WAF5100T5E")
        (field (name "Manufacturer") "UNI-ROYAL(厚声)")
      )
      (libsource (lib "easyedapro") (part "0603WAF5100T5E"))
    )
    (comp (ref "R71")
      (value "510Ω")
      (footprint "easyedapro:R0603")
      (fields
        (field (name "Manufacturer Part") "0603WAF5100T5E")
        (field (name "Manufacturer") "UNI-ROYAL(厚声)")
      )
      (libsource (lib "easyedapro") (part "0603WAF5100T5E"))
    )
    (comp (ref "R72")
      (value "510Ω")
      (footprint "easyedapro:R0603")
      (fields
        (field (name "Manufacturer Part") "0603WAF5100T5E")
        (field (name "Manufacturer") "UNI-ROYAL(厚声)")
      )
      (libsource (lib "easyedapro") (part "0603WAF5100T5E"))
    )
    (comp (ref "R73")
      (value "510Ω")
      (footprint "easyedapro:R0603")
      (fields
        (field (name "Manufacturer Part") "0603WAF5100T5E")
        (field (name "Manufacturer") "UNI-ROYAL(厚声)")
      )
      (libsource (lib "easyedapro") (part "0603WAF5100T5E"))
    )
    (comp (ref "R113")
      (value "4.7kΩ")
      (footprint "easyedapro:R0603")
      (fields
        (field (name "Manufacturer Part") "0603WAF4701T5E")
        (field (name "Manufacturer") "UNI-ROYAL(厚声)")
      )
      (libsource (lib "easyedapro") (part "0603WAF4701T5E"))
    )
    (comp (ref "R114")
      (value "4.7kΩ")
      (footprint "easyedapro:R0603")
      (fields
        (field (name "Manufacturer Part") "0603WAF4701T5E")
        (field (name "Manufacturer") "UNI-ROYAL(厚声)")
      )
      (libsource (lib "easyedapro") (part "0603WAF4701T5E"))
    )
    (comp (ref "R115")
      (value "4.7kΩ")
      (footprint "easyedapro:R0603")
      (fields
        (field (name "Manufacturer Part") "0603WAF4701T5E")
        (field (name "Manufacturer") "UNI-ROYAL(厚声)")
      )
      (libsource (lib "easyedapro") (part "0603WAF4701T5E"))
    )
    (comp (ref "R116")
      (value "4.7kΩ")
      (footprint "easyedapro:R0603")
      (fields
        (field (name "Manufacturer Part") "0603WAF4701T5E")
        (field (name "Manufacturer") "UNI-ROYAL(厚声)")
      )
      (libsource (lib "easyedapro") (part "0603WAF4701T5E"))
    )
    (comp (ref "R117")
      (value "4.7kΩ")
      (footprint "easyedapro:R0603")
      (fields
        (field (name "Manufacturer Part") "0603WAF4701T5E")
        (field (name "Manufacturer") "UNI-ROYAL(厚声)")
      )
      (libsource (lib "easyedapro") (part "0603WAF4701T5E"))
    )
    (comp (ref "R118")
      (value "4.7kΩ")
      (footprint "easyedapro:R0603")
      (fields
        (field (name "Manufacturer Part") "0603WAF4701T5E")
        (field (name "Manufacturer") "UNI-ROYAL(厚声)")
      )
      (libsource (lib "easyedapro") (part "0603WAF4701T5E"))
    )
    (comp (ref "R119")
      (value "4.7kΩ")
      (footprint "easyedapro:R0603")
      (fields
        (field (name "Manufacturer Part") "0603WAF4701T5E")
        (field (name "Manufacturer") "UNI-ROYAL(厚声)")
      )
      (libsource (lib "easyedapro") (part "0603WAF4701T5E"))
    )
    (comp (ref "R120")
      (value "4.7kΩ")
      (footprint "easyedapro:R0603")
      (fields
        (field (name "Manufacturer Part") "0603WAF4701T5E")
        (field (name "Manufacturer") "UNI-ROYAL(厚声)")
      )
      (libsource (lib "easyedapro") (part "0603WAF4701T5E"))
    )
    (comp (ref "U6")
      (value "EL357N(B)(TA)-G")
      (footprint "easyedapro:OPTO-SMD-4_L4.4-W4.1-P2.54-LS7.0-TL")
      (fields (field (name "Manufacturer") "EVERLIGHT(亿光)"))
      (libsource (lib "easyedapro") (part "EL357N(B)(TA)-G"))
    )
    (comp (ref "U15")
      (value "EL357N(B)(TA)-G")
      (footprint "easyedapro:OPTO-SMD-4_L4.4-W4.1-P2.54-LS7.0-TL")
      (fields (field (name "Manufacturer") "EVERLIGHT(亿光)"))
      (libsource (lib "easyedapro") (part "EL357N(B)(TA)-G"))
    )
    (comp (ref "U16")
      (value "EL357N(B)(TA)-G")
      (footprint "easyedapro:OPTO-SMD-4_L4.4-W4.1-P2.54-LS7.0-TL")
      (fields (field (name "Manufacturer") "EVERLIGHT(亿光)"))
      (libsource (lib "easyedapro") (part "EL357N(B)(TA)-G"))
    )
    (comp (ref "U17")
      (value "EL357N(B)(TA)-G")
      (footprint "easyedapro:OPTO-SMD-4_L4.4-W4.1-P2.54-LS7.0-TL")
      (fields (field (name "Manufacturer") "EVERLIGHT(亿光)"))
      (libsource (lib "easyedapro") (part "EL357N(B)(TA)-G"))
    )
    (comp (ref "C23")
      (value "100nF")
      (footprint "easyedapro:C0603")
      (libsource (lib "easyedapro") (part "CAP"))
    )
    (comp (ref "C25")
      (value "10uF")
      (footprint "easyedapro:C0603")
      (fields
        (field (name "Manufacturer Part") "CL10A106KP8NNNC")
        (field (name "Manufacturer") "SAMSUNG(三星)")
      )
      (libsource (lib "easyedapro") (part "CL10A106KP8NNNC"))
    )
    (comp (ref "C26")
      (value "20pF")
      (footprint "easyedapro:C0603")
      (fields
        (field (name "Manufacturer Part") "CL10C200JB8NNNC")
        (field (name "Manufacturer") "SAMSUNG(三星)")
      )
      (libsource (lib "easyedapro") (part "CL10C200JB8NNNC"))
    )
    (comp (ref "C27")
      (value "20pF")
      (footprint "easyedapro:C0603")
      (fields
        (field (name "Manufacturer Part") "CL10C200JB8NNNC")
        (field (name "Manufacturer") "SAMSUNG(三星)")
      )
      (libsource (lib "easyedapro") (part "CL10C200JB8NNNC"))
    )
    (comp (ref "C28")
      (value "100nF")
      (footprint "easyedapro:C0603")
      (libsource (lib "easyedapro") (part "CAP"))
    )
    (comp (ref "C29")
      (value "10uF")
      (footprint "easyedapro:C0603")
      (fields
        (field (name "Manufacturer Part") "CL10A106KP8NNNC")
        (field (name "Manufacturer") "SAMSUNG(三星)")
      )
      (libsource (lib "easyedapro") (part "CL10A106KP8NNNC"))
    )
    (comp (ref "C70")
      (value "10uF")
      (footprint "easyedapro:C0603")
      (fields
        (field (name "Manufacturer Part") "CL10A106KP8NNNC")
        (field (name "Manufacturer") "SAMSUNG(三星)")
      )
      (libsource (lib "easyedapro") (part "CL10A106KP8NNNC"))
    )
    (comp (ref "C71")
      (value "10uF")
      (footprint "easyedapro:C0603")
      (fields
        (field (name "Manufacturer Part") "CL10A106KP8NNNC")
        (field (name "Manufacturer") "SAMSUNG(三星)")
      )
      (libsource (lib "easyedapro") (part "CL10A106KP8NNNC"))
    )
    (comp (ref "C72")
      (value "100nF")
      (footprint "easyedapro:C0603")
      (libsource (lib "easyedapro") (part "CAP"))
    )
    (comp (ref "R46")
      (value "2.7K")
      (footprint "easyedapro:R0603")
      (libsource (lib "easyedapro") (part "Res"))
    )
    (comp (ref "R47")
      (value "100kΩ")
      (footprint "easyedapro:R0603")
      (fields
        (field (name "Manufacturer Part") "0603WAF1003T5E")
        (field (name "Manufacturer") "UNI-ROYAL(厚声)")
      )
      (libsource (lib "easyedapro") (part "0603WAF1003T5E"))
    )
    (comp (ref "R48")
      (value "100kΩ")
      (footprint "easyedapro:R0603")
      (fields
        (field (name "Manufacturer Part") "0603WAF1003T5E")
        (field (name "Manufacturer") "UNI-ROYAL(厚声)")
      )
      (libsource (lib "easyedapro") (part "0603WAF1003T5E"))
    )
    (comp (ref "R49")
      (value "100kΩ")
      (footprint "easyedapro:R0603")
      (fields
        (field (name "Manufacturer Part") "0603WAF1003T5E")
        (field (name "Manufacturer") "UNI-ROYAL(厚声)")
      )
      (libsource (lib "easyedapro") (part "0603WAF1003T5E"))
    )
    (comp (ref "R127")
      (value "2.7K")
      (footprint "easyedapro:R0603")
      (libsource (lib "easyedapro") (part "Res"))
    )
    (comp (ref "R128")
      (value "2.7K")
      (footprint "easyedapro:R0603")
      (libsource (lib "easyedapro") (part "Res"))
    )
    (comp (ref "R129")
      (value "13K")
      (footprint "easyedapro:R0603")
      (libsource (lib "easyedapro") (part "Res"))
    )
    (comp (ref "R130")
      (value "13K")
      (footprint "easyedapro:R0603")
      (libsource (lib "easyedapro") (part "Res"))
    )
    (comp (ref "U10")
      (value "SL2.2s")
      (footprint "easyedapro:SSOP-28_L9.9-W3.9-P0.64-LS6.0-BL")
      (fields (field (name "Manufacturer") "CoreChips(和芯润德)"))
      (libsource (lib "easyedapro") (part "SL2.2S"))
    )
    (comp (ref "U25")
      (value "MT9700")
      (footprint "easyedapro:SOT-23-5_L3.0-W1.7-P0.95-LS2.8-BR")
      (fields (field (name "Manufacturer") "西安航天民芯"))
      (libsource (lib "easyedapro") (part "MT9700"))
    )
    (comp (ref "U28")
      (value "FSUSB42MUX")
      (footprint "easyedapro:MSOP-10_L3.0-W3.0-P0.50-LS5.0-BL")
      (fields (field (name "Manufacturer") "onsemi(安森美)"))
      (libsource (lib "easyedapro") (part "FSUSB42MUX"))
    )
    (comp (ref "U31")
      (value "TPD4EUSB30DQAR-N")
      (footprint "easyedapro:DFN-10_L2.5-W1.0-P0.50-BL-A")
      (fields (field (name "Manufacturer") "BORN(伯恩半导体)"))
      (libsource (lib "easyedapro") (part "TPD4EUSB30DQAR-N"))
    )
    (comp (ref "USB7")
      (value "AF SS-JB17.6")
      (footprint "easyedapro:USB-A-TH_AF-SS-JB17.6")
      (fields (field (name "Manufacturer") "SHOU HAN(首韩)"))
      (libsource (lib "easyedapro") (part "AF SS-JB17.6"))
    )
    (comp (ref "USB8")
      (value "MICRO 180°ZB")
      (footprint "easyedapro:MICRO-USB-TH_MICRO-180-ZB")
      (fields (field (name "Manufacturer") "SHOU HAN(首韩)"))
      (libsource (lib "easyedapro") (part "MICRO 180°ZB"))
    )
    (comp (ref "X1")
      (value "12MHz")
      (footprint "easyedapro:OSC-SMD_4P-L3.2-W2.5-BL")
      (fields (field (name "Manufacturer Part") "X322512MSB4SI") (field (name "Manufacturer") "YXC(扬兴晶振)"))
      (libsource (lib "easyedapro") (part "X322512MSB4SI"))
    )
    (comp (ref "C64")
      (value "10nF")
      (footprint "easyedapro:C0603")
      (fields (field (name "Manufacturer Part") "0603B103K500NT") (field (name "Manufacturer") "FH(风华)"))
      (libsource (lib "easyedapro") (part "0603B103K500NT"))
    )
    (comp (ref "R74")
      (value "510Ω")
      (footprint "easyedapro:R0603")
      (fields
        (field (name "Manufacturer Part") "0603WAF5100T5E")
        (field (name "Manufacturer") "UNI-ROYAL(厚声)")
      )
      (libsource (lib "easyedapro") (part "0603WAF5100T5E"))
    )
    (comp (ref "R75")
      (value "510Ω")
      (footprint "easyedapro:R0603")
      (fields
        (field (name "Manufacturer Part") "0603WAF5100T5E")
        (field (name "Manufacturer") "UNI-ROYAL(厚声)")
      )
      (libsource (lib "easyedapro") (part "0603WAF5100T5E"))
    )
    (comp (ref "RJ2")
      (value "HR911130A")
      (footprint "easyedapro:RJ45-TH_HR911130A")
      (description "Connector Type:RJReceptacle USOC Codes:RJ45 Number of Ports:1 Ratings:- Shielding:- LED:WithLED")
      (fields (field (name "Manufacturer") "HANRUN(汉仁)"))
      (libsource (lib "easyedapro") (part "HR911130A"))
    )
    (comp (ref "U20")
      (value "TPD4EUSB30DQAR-N")
      (footprint "easyedapro:DFN-10_L2.5-W1.0-P0.50-BL-A")
      (fields (field (name "Manufacturer") "BORN(伯恩半导体)"))
      (libsource (lib "easyedapro") (part "TPD4EUSB30DQAR-N"))
    )
    (comp (ref "U21")
      (value "TPD4EUSB30DQAR-N")
      (footprint "easyedapro:DFN-10_L2.5-W1.0-P0.50-BL-A")
      (fields (field (name "Manufacturer") "BORN(伯恩半导体)"))
      (libsource (lib "easyedapro") (part "TPD4EUSB30DQAR-N"))
    )
    (comp (ref "C32")
      (value "10uF")
      (footprint "easyedapro:C1206")
      (fields
        (field (name "Manufacturer Part") "CL31A106KBHNNNE")
        (field (name "Manufacturer") "SAMSUNG(三星)")
      )
      (libsource (lib "easyedapro") (part "CL31A106KBHNNNE"))
    )
    (comp (ref "C33")
      (value "10uF")
      (footprint "easyedapro:C1206")
      (fields
        (field (name "Manufacturer Part") "CL31A106KBHNNNE")
        (field (name "Manufacturer") "SAMSUNG(三星)")
      )
      (libsource (lib "easyedapro") (part "CL31A106KBHNNNE"))
    )
    (comp (ref "C35")
      (value "3.3nF")
      (footprint "easyedapro:C0603")
      (libsource (lib "easyedapro") (part "CAP"))
    )
    (comp (ref "C36")
      (value "22uF")
      (footprint "easyedapro:C0805")
      (fields
        (field (name "Manufacturer Part") "CL21A226MAQNNNE")
        (field (name "Manufacturer") "SAMSUNG(三星)")
      )
      (libsource (lib "easyedapro") (part "CL21A226MAQNNNE"))
    )
    (comp (ref "C37")
      (value "22uF")
      (footprint "easyedapro:C0805")
      (fields
        (field (name "Manufacturer Part") "CL21A226MAQNNNE")
        (field (name "Manufacturer") "SAMSUNG(三星)")
      )
      (libsource (lib "easyedapro") (part "CL21A226MAQNNNE"))
    )
    (comp (ref "C38")
      (value "220uF")
      (footprint "easyedapro:CAP-SMD_BD10.0-L10.3-W10.3-LS11.3-FD")
      (fields
        (field (name "Manufacturer Part") "UCD1H221MNL1GS")
        (field (name "Manufacturer") "Nichicon(尼吉康)")
      )
      (libsource (lib "easyedapro") (part "UCD1H221MNL1GS"))
    )
    (comp (ref "C40")
      (value "100nF")
      (footprint "easyedapro:C0603")
      (fields
        (field (name "Manufacturer Part") "CC0603KRX7R9BB104")
        (field (name "Manufacturer") "YAGEO(国巨)")
      )
      (libsource (lib "easyedapro") (part "CC0603KRX7R9BB104"))
    )
    (comp (ref "C41")
      (value "100nF")
      (footprint "easyedapro:C0603")
      (fields
        (field (name "Manufacturer Part") "CC0603KRX7R9BB104")
        (field (name "Manufacturer") "YAGEO(国巨)")
      )
      (libsource (lib "easyedapro") (part "CC0603KRX7R9BB104"))
    )
    (comp (ref "D19")
      (value "P6SMB27CA/TR13")
      (footprint "easyedapro:SMB_L4.3-W3.6-LS5.4-BI")
      (fields (field (name "Manufacturer") "Brightking(君耀电子)"))
      (libsource (lib "easyedapro") (part "P6SMB27CA_C730015"))
    )
    (comp (ref "D44")
      (value "MM5Z4V7")
      (footprint "easyedapro:SOD-523_L1.2-W0.8-LS1.6-FD")
      (fields (field (name "Manufacturer") "CBI(创基)"))
      (libsource (lib "easyedapro") (part "MM5Z4V7 G8"))
    )
    (comp (ref "F1")
      (value "BSMD1812-200-30V")
      (footprint "easyedapro:F1812")
      (fields (field (name "Manufacturer") "BHFUSE(佰宏)"))
      (libsource (lib "easyedapro") (part "BSMD1812-200-30V"))
    )
    (comp (ref "L4")
      (value "4.7uH")
      (footprint "easyedapro:IND-SMD_L7.1-W6.6")
      (fields
        (field (name "Manufacturer Part") "CMLO0650H4R7MTT")
        (field (name "Manufacturer") "Cybermax(思博科技)")
      )
      (libsource (lib "easyedapro") (part "CMLO0650H4R7MTT"))
    )
    (comp (ref "LED6")
      (value "19-217/GHC-YR1S2/3T")
      (footprint "easyedapro:LED0603-RD")
      (fields (field (name "Manufacturer") "EVERLIGHT(亿光)"))
      (libsource (lib "easyedapro") (part "19-217/GHC-YR1S2/3T"))
    )
    (comp (ref "LED7")
      (value "19-217/GHC-YR1S2/3T")
      (footprint "easyedapro:LED0603-RD")
      (fields (field (name "Manufacturer") "EVERLIGHT(亿光)"))
      (libsource (lib "easyedapro") (part "19-217/GHC-YR1S2/3T"))
    )
    (comp (ref "Q2")
      (value "AO3401A")
      (footprint "easyedapro:SOT-23_L2.9-W1.3-P1.90-LS2.4-BR")
      (fields (field (name "Manufacturer") "AOS"))
      (libsource (lib "easyedapro") (part "AO3401A"))
    )
    (comp (ref "R54")
      (value "20K")
      (footprint "easyedapro:R0603")
      (libsource (lib "easyedapro") (part "Res"))
    )
    (comp (ref "R56")
      (value "10K")
      (footprint "easyedapro:R0603")
      (libsource (lib "easyedapro") (part "Res"))
    )
    (comp (ref "R57")
      (value "300")
      (footprint "easyedapro:R0603")
      (libsource (lib "easyedapro") (part "Res"))
    )
    (comp (ref "R59")
      (value "2.2kΩ")
      (footprint "easyedapro:R0603")
      (fields
        (field (name "Manufacturer Part") "0603WAF2201T5E")
        (field (name "Manufacturer") "UNI-ROYAL(厚声)")
      )
      (libsource (lib "easyedapro") (part "0603WAF2201T5E"))
    )
    (comp (ref "R60")
      (value "52.3kΩ")
      (footprint "easyedapro:R0603")
      (fields (field (name "Manufacturer Part") "RTT035232FTP") (field (name "Manufacturer") "RALEC(旺诠)"))
      (libsource (lib "easyedapro") (part "RTT035232FTP"))
    )
    (comp (ref "R78")
      (value "137kΩ")
      (footprint "easyedapro:R0603")
      (fields
        (field (name "Manufacturer Part") "0603WAF1373T5E")
        (field (name "Manufacturer") "UNI-ROYAL(厚声)")
      )
      (libsource (lib "easyedapro") (part "0603WAF1373T5E"))
    )
    (comp (ref "R79")
      (value "137kΩ")
      (footprint "easyedapro:R0603")
      (fields
        (field (name "Manufacturer Part") "0603WAF1373T5E")
        (field (name "Manufacturer") "UNI-ROYAL(厚声)")
      )
      (libsource (lib "easyedapro") (part "0603WAF1373T5E"))
    )
    (comp (ref "R80")
      (value "137kΩ")
      (footprint "easyedapro:R0603")
      (fields
        (field (name "Manufacturer Part") "0603WAF1373T5E")
        (field (name "Manufacturer") "UNI-ROYAL(厚声)")
      )
      (libsource (lib "easyedapro") (part "0603WAF1373T5E"))
    )
    (comp (ref "U14")
      (value "RT7272BGSP")
      (footprint "easyedapro:SOIC-8_L5.0-W4.0-P1.27-LS6.0-BL-EP2.0")
      (fields (field (name "Manufacturer") "RICHTEK(立锜)"))
      (libsource (lib "easyedapro") (part "RT7272BGSP"))
    )
    (comp (ref "B1")
      (value "CR2032-BS-5-1")
      (footprint "easyedapro:BAT-TH_CR2032-BS-5-1")
      (fields (field (name "Manufacturer") "Q&amp;J"))
      (libsource (lib "easyedapro") (part "CR2032-BS-5-1"))
    )
    (comp (ref "C51")
      (value "100nF")
      (footprint "easyedapro:C0603")
      (fields
        (field (name "Manufacturer Part") "CC0603KRX7R9BB104")
        (field (name "Manufacturer") "YAGEO(国巨)")
      )
      (libsource (lib "easyedapro") (part "CC0603KRX7R9BB104"))
    )
    (comp (ref "CN17")
      (value "PH-5A")
      (footprint "easyedapro:CONN-TH_5P-P2.00_PH-5A")
      (fields (field (name "Manufacturer") "BOOMELE(博穆精密)"))
      (libsource (lib "easyedapro") (part "PH-5A"))
    )
    (comp (ref "R173")
      (value "4.7K")
      (footprint "easyedapro:R0603")
      (libsource (lib "easyedapro") (part "Res"))
    )
    (comp (ref "R178")
      (value "4.7K")
      (footprint "easyedapro:R0603")
      (libsource (lib "easyedapro") (part "Res"))
    )
    (comp (ref "R179")
      (value "4.7K")
      (footprint "easyedapro:R0603")
      (libsource (lib "easyedapro") (part "Res"))
    )
    (comp (ref "U19")
      (value "XL1307")
      (footprint "easyedapro:SOP-8_L4.9-W3.9-P1.27-LS6.0-BL")
      (fields (field (name "Manufacturer") "XINLUDA(信路达)"))
      (libsource (lib "easyedapro") (part "XL1307"))
    )
    (comp (ref "X2")
      (value "32.768kHz")
      (footprint "easyedapro:FC-135R_L3.2-W1.5")
      (fields (field (name "Manufacturer Part") "Q13FC1350000400") (field (name "Manufacturer") "EPSON(爱普生)"))
      (libsource (lib "easyedapro") (part "Q13FC1350000400"))
    )
    (comp (ref "C66")
      (value "33pF")
      (footprint "easyedapro:C0603")
      (libsource (lib "easyedapro") (part "CAP"))
    )
    (comp (ref "C67")
      (value "100nF")
      (footprint "easyedapro:C0603")
      (fields
        (field (name "Manufacturer Part") "CC0603KRX7R9BB104")
        (field (name "Manufacturer") "YAGEO(国巨)")
      )
      (libsource (lib "easyedapro") (part "CC0603KRX7R9BB104"))
    )
    (comp (ref "C68")
      (value "10uF")
      (footprint "easyedapro:C0603")
      (fields
        (field (name "Manufacturer Part") "CL10A106KP8NNNC")
        (field (name "Manufacturer") "SAMSUNG(三星)")
      )
      (libsource (lib "easyedapro") (part "CL10A106KP8NNNC"))
    )
    (comp (ref "C69")
      (value "100nF")
      (footprint "easyedapro:C0603")
      (fields
        (field (name "Manufacturer Part") "CC0603KRX7R9BB104")
        (field (name "Manufacturer") "YAGEO(国巨)")
      )
      (libsource (lib "easyedapro") (part "CC0603KRX7R9BB104"))
    )
    (comp (ref "D39")
      (value "PSM712-LF-T7")
      (footprint "easyedapro:SOT-23-3_L3.0-W1.7-P0.95-LS2.9-BR")
      (fields (field (name "Manufacturer") "PROTEK"))
      (libsource (lib "easyedapro") (part "PSM712-LF-T7"))
    )
    (comp (ref "D40")
      (value "1N4148W")
      (footprint "easyedapro:SOD-123F_L2.7-W1.6-LS3.8-RD")
      (fields (field (name "Manufacturer") "ST(先科)"))
      (libsource (lib "easyedapro") (part "1N4148W_C81598"))
    )
    (comp (ref "LED11")
      (value "19-217/GHC-YR1S2/3T")
      (footprint "easyedapro:LED0603-RD")
      (fields (field (name "Manufacturer") "EVERLIGHT(亿光)"))
      (libsource (lib "easyedapro") (part "19-217/GHC-YR1S2/3T"))
    )
    (comp (ref "LED12")
      (value "19-217/GHC-YR1S2/3T")
      (footprint "easyedapro:LED0603-RD")
      (fields (field (name "Manufacturer") "EVERLIGHT(亿光)"))
      (libsource (lib "easyedapro") (part "19-217/GHC-YR1S2/3T"))
    )
    (comp (ref "R112")
      (value "120Ω")
      (footprint "easyedapro:R0603")
      (fields
        (field (name "Manufacturer Part") "0603WAF1200T5E")
        (field (name "Manufacturer") "UNI-ROYAL(厚声)")
      )
      (libsource (lib "easyedapro") (part "0603WAF1200T5E"))
    )
    (comp (ref "R121")
      (value "4.7kΩ")
      (footprint "easyedapro:R0603")
      (fields
        (field (name "Manufacturer Part") "0603WAF4701T5E")
        (field (name "Manufacturer") "UNI-ROYAL(厚声)")
      )
      (libsource (lib "easyedapro") (part "0603WAF4701T5E"))
    )
    (comp (ref "R122")
      (value "300")
      (footprint "easyedapro:R0603")
      (libsource (lib "easyedapro") (part "Res"))
    )
    (comp (ref "R123")
      (value "4.7kΩ")
      (footprint "easyedapro:R0603")
      (fields
        (field (name "Manufacturer Part") "0603WAF4701T5E")
        (field (name "Manufacturer") "UNI-ROYAL(厚声)")
      )
      (libsource (lib "easyedapro") (part "0603WAF4701T5E"))
    )
    (comp (ref "R124")
      (value "52.3kΩ")
      (footprint "easyedapro:R0603")
      (fields (field (name "Manufacturer Part") "RTT035232FTP") (field (name "Manufacturer") "RALEC(旺诠)"))
      (libsource (lib "easyedapro") (part "RTT035232FTP"))
    )
    (comp (ref "R125")
      (value "300")
      (footprint "easyedapro:R0603")
      (libsource (lib "easyedapro") (part "Res"))
    )
    (comp (ref "U23")
      (value "SP3485EN-L/TR")
      (footprint "easyedapro:SOIC-8_L5.0-W4.0-P1.27-LS6.0-BL")
      (fields (field (name "Manufacturer") "MaxLinear"))
      (libsource (lib "easyedapro") (part "SP3485EN-L/TR"))
    )
    (comp (ref "U24")
      (value "74HC14D,653")
      (footprint "easyedapro:SOIC-14_L8.7-W3.9-P1.27-LS6.0-BL")
      (fields (field (name "Manufacturer") "Nexperia(安世)"))
      (libsource (lib "easyedapro") (part "74HC14D,653"))
    )
    (comp (ref "C85")
      (value "10uF")
      (footprint "easyedapro:C0603")
      (fields
        (field (name "Manufacturer Part") "CL10A106KP8NNNC")
        (field (name "Manufacturer") "SAMSUNG(三星)")
      )
      (libsource (lib "easyedapro") (part "CL10A106KP8NNNC"))
    )
    (comp (ref "C86")
      (value "10uF")
      (footprint "easyedapro:C0603")
      (fields
        (field (name "Manufacturer Part") "CL10A106KP8NNNC")
        (field (name "Manufacturer") "SAMSUNG(三星)")
      )
      (libsource (lib "easyedapro") (part "CL10A106KP8NNNC"))
    )
    (comp (ref "CN20")
      (value "HYC23-HDMID19-650")
      (footprint "easyedapro:AUDIO-TH_HYC23-HDMID19-650")
      (fields (field (name "Manufacturer") "华宇创"))
      (libsource (lib "easyedapro") (part "HYC23-HDMID19-650"))
    )
    (comp (ref "R162")
      (value "13K")
      (footprint "easyedapro:R0603")
      (libsource (lib "easyedapro") (part "Res"))
    )
    (comp (ref "R163")
      (value "13K")
      (footprint "easyedapro:R0603")
      (libsource (lib "easyedapro") (part "Res"))
    )
    (comp (ref "U41")
      (value "MT9700")
      (footprint "easyedapro:SOT-23-5_L3.0-W1.7-P0.95-LS2.8-BR")
      (fields (field (name "Manufacturer") "西安航天民芯"))
      (libsource (lib "easyedapro") (part "MT9700"))
    )
    (comp (ref "USB16")
      (value "HDMI-001C")
      (footprint "easyedapro:HDMI-SMD_HDMI-001C")
      (fields (field (name "Manufacturer") "XUNPU(讯普)"))
      (libsource (lib "easyedapro") (part "HDMI-001C_C2836126"))
    )
  )
  (nets
    (net (code "1") (name "+1.8V") (class "Default")
      (node (ref "CN3") (pin "65") (pinfunction "65_65") (pintype "input"))
      (node (ref "R165") (pin "2") (pinfunction "2_2") (pintype "input"))
    )
    (net (code "2") (name "+3.3V") (class "Default")
      (node (ref "C18") (pin "2") (pinfunction "2_2") (pintype "input"))
      (node (ref "C30") (pin "2") (pinfunction "2_2") (pintype "input"))
      (node (ref "C31") (pin "1") (pinfunction "1_1") (pintype "input"))
      (node (ref "C51") (pin "2") (pinfunction "2_2") (pintype "input"))
      (node (ref "C61") (pin "1") (pinfunction "1_1") (pintype "input"))
      (node (ref "C62") (pin "2") (pinfunction "2_2") (pintype "input"))
      (node (ref "C63") (pin "2") (pinfunction "2_2") (pintype "input"))
      (node (ref "C67") (pin "2") (pinfunction "2_2") (pintype "input"))
      (node (ref "C68") (pin "2") (pinfunction "2_2") (pintype "input"))
      (node (ref "C69") (pin "2") (pinfunction "2_2") (pintype "input"))
      (node (ref "C72") (pin "2") (pinfunction "2_2") (pintype "input"))
      (node (ref "CARD1") (pin "4") (pinfunction "VDD_4") (pintype "input"))
      (node (ref "CN17") (pin "2") (pinfunction "2_2") (pintype "input"))
      (node (ref "D2") (pin "2") (pinfunction "2_2") (pintype "input"))
      (node (ref "D28") (pin "2") (pinfunction "2_2") (pintype "input"))
      (node (ref "D29") (pin "2") (pinfunction "2_2") (pintype "input"))
      (node (ref "D3") (pin "2") (pinfunction "2_2") (pintype "input"))
      (node (ref "D34") (pin "2") (pinfunction "2_2") (pintype "input"))
      (node (ref "D35") (pin "2") (pinfunction "2_2") (pintype "input"))
      (node (ref "FPC8") (pin "1") (pinfunction "1_1") (pintype "input"))
      (node (ref "LED13") (pin "2") (pinfunction "A_2") (pintype "input"))
      (node (ref "LED14") (pin "2") (pinfunction "A_2") (pintype "input"))
      (node (ref "R117") (pin "2") (pinfunction "2_2") (pintype "input"))
      (node (ref "R118") (pin "2") (pinfunction "2_2") (pintype "input"))
      (node (ref "R119") (pin "2") (pinfunction "2_2") (pintype "input"))
      (node (ref "R120") (pin "2") (pinfunction "2_2") (pintype "input"))
      (node (ref "R121") (pin "2") (pinfunction "2_2") (pintype "input"))
      (node (ref "R123") (pin "2") (pinfunction "2_2") (pintype "input"))
      (node (ref "R137") (pin "2") (pinfunction "2_2") (pintype "input"))
      (node (ref "R138") (pin "2") (pinfunction "2_2") (pintype "input"))
      (node (ref "R173") (pin "2") (pinfunction "2_2") (pintype "input"))
      (node (ref "R178") (pin "2") (pinfunction "2_2") (pintype "input"))
      (node (ref "R179") (pin "2") (pinfunction "2_2") (pintype "input"))
      (node (ref "RJ2") (pin "11") (pinfunction "11_11") (pintype "input"))
      (node (ref "RJ2") (pin "14") (pinfunction "14_14") (pintype "input"))
      (node (ref "U19") (pin "8") (pinfunction "VCC_8") (pintype "input"))
      (node (ref "U22") (pin "4") (pinfunction "VCC+_4") (pintype "input"))
      (node (ref "U23") (pin "8") (pinfunction "VCC_8") (pintype "input"))
      (node (ref "U24") (pin "14") (pinfunction "VCC_14") (pintype "input"))
      (node (ref "U28") (pin "1") (pinfunction "VCC_1") (pintype "input"))
      (node (ref "U45") (pin "78") (pinfunction "GPIO_VREF_78") (pintype "bidirectional"))
      (node (ref "U45") (pin "84") (pinfunction "CM4_3V3_O_84") (pintype "bidirectional"))
      (node (ref "U45") (pin "86") (pinfunction "CM4_3V3_O_86") (pintype "bidirectional"))
      (node (ref "U8") (pin "8") (pinfunction "VDD_8") (pintype "input"))
    )
    (net (code "3") (name "+3.7V") (class "Default")
      (node (ref "C103") (pin "2") (pinfunction "2_2") (pintype "input"))
      (node (ref "C104") (pin "2") (pinfunction "2_2") (pintype "input"))
      (node (ref "C105") (pin "2") (pinfunction "2_2") (pintype "input"))
      (node (ref "C106") (pin "2") (pinfunction "2_2") (pintype "input"))
      (node (ref "C44") (pin "2") (pinfunction "2_2") (pintype "input"))
      (node (ref "C52") (pin "2") (pinfunction "2_2") (pintype "input"))
      (node (ref "C6") (pin "2") (pinfunction "2_2") (pintype "input"))
      (node (ref "C7") (pin "2") (pinfunction "2_2") (pintype "input"))
      (node (ref "C88") (pin "1") (pinfunction "1_1") (pintype "input"))
      (node (ref "C93") (pin "2") (pinfunction "2_2") (pintype "input"))
      (node (ref "C94") (pin "2") (pinfunction "2_2") (pintype "input"))
      (node (ref "C95") (pin "1") (pinfunction "1_1") (pintype "input"))
      (node (ref "C98") (pin "2") (pinfunction "2_2") (pintype "input"))
      (node (ref "C99") (pin "2") (pinfunction "2_2") (pintype "input"))
      (node (ref "CN3") (pin "2") (pinfunction "2_2") (pintype "input"))
      (node (ref "CN3") (pin "4") (pinfunction "4_4") (pintype "input"))
      (node (ref "CN3") (pin "70") (pinfunction "70_70") (pintype "input"))
      (node (ref "CN3") (pin "72") (pinfunction "72_72") (pintype "input"))
      (node (ref "CN3") (pin "74") (pinfunction "74_74") (pintype "input"))
      (node (ref "D43") (pin "2") (pinfunction "K_2") (pintype "input"))
      (node (ref "L1") (pin "2") (pinfunction "2_2") (pintype "input"))
      (node (ref "LED8") (pin "2") (pinfunction "A_2") (pintype "input"))
      (node (ref "R10") (pin "1") (pinfunction "1_1") (pintype "input"))
      (node (ref "R11") (pin "1") (pinfunction "1_1") (pintype "input"))
      (node (ref "R5") (pin "2") (pinfunction "2_2") (pintype "input"))
    )
    (net (code "4") (name "+5V") (class "Default")
      (node (ref "C36") (pin "2") (pinfunction "2_2") (pintype "input"))
      (node (ref "C37") (pin "2") (pinfunction "2_2") (pintype "input"))
      (node (ref "C70") (pin "2") (pinfunction "2_2") (pintype "input"))
      (node (ref "C85") (pin "2") (pinfunction "2_2") (pintype "input"))
      (node (ref "L4") (pin "2") (pinfunction "2_2") (pintype "input"))
      (node (ref "LED7") (pin "2") (pinfunction "A_2") (pintype "input"))
      (node (ref "R130") (pin "1") (pinfunction "1_1") (pintype "input"))
      (node (ref "R162") (pin "1") (pinfunction "1_1") (pintype "input"))
      (node (ref "R60") (pin "2") (pinfunction "2_2") (pintype "input"))
      (node (ref "U10") (pin "20") (pinfunction "VDD5_20") (pintype "input"))
      (node (ref "U25") (pin "5") (pinfunction "VIN_5") (pintype "input"))
      (node (ref "U41") (pin "5") (pinfunction "VIN_5") (pintype "input"))
      (node (ref "U45") (pin "77") (pinfunction "+5V_IN_77") (pintype "bidirectional"))
      (node (ref "U45") (pin "79") (pinfunction "+5V_IN_79") (pintype "bidirectional"))
      (node (ref "U45") (pin "81") (pinfunction "+5V_IN_81") (pintype "bidirectional"))
      (node (ref "U45") (pin "83") (pinfunction "+5V_IN_83") (pintype "bidirectional"))
      (node (ref "U45") (pin "85") (pinfunction "+5V_IN_85") (pintype "bidirectional"))
      (node (ref "U45") (pin "87") (pinfunction "+5V_IN_87") (pintype "bidirectional"))
    )
    (net (code "5") (name "+24V") (class "Default")
      (node (ref "C11") (pin "2") (pinfunction "2_2") (pintype "input"))
      (node (ref "C12") (pin "2") (pinfunction "2_2") (pintype "input"))
      (node (ref "C2") (pin "2") (pinfunction "2_2") (pintype "input"))
      (node (ref "C3") (pin "2") (pinfunction "2_2") (pintype "input"))
      (node (ref "C32") (pin "2") (pinfunction "2_2") (pintype "input"))
      (node (ref "C33") (pin "2") (pinfunction "2_2") (pintype "input"))
      (node (ref "C38") (pin "1") (pinfunction "1_1") (pintype "input"))
      (node (ref "C40") (pin "2") (pinfunction "2_2") (pintype "input"))
      (node (ref "D44") (pin "2") (pinfunction "K_2") (pintype "input"))
      (node (ref "Q2") (pin "2") (pinfunction "S_2") (pintype "input"))
      (node (ref "R59") (pin "2") (pinfunction "2_2") (pintype "input"))
      (node (ref "R78") (pin "1") (pinfunction "1_1") (pintype "input"))
      (node (ref "R83") (pin "1") (pinfunction "1_1") (pintype "input"))
      (node (ref "U14") (pin "8") (pinfunction "VIN_8") (pintype "input"))
      (node (ref "U3") (pin "8") (pinfunction "VIN_8") (pintype "input"))
      (node (ref "U4") (pin "8") (pinfunction "VIN_8") (pintype "input"))
    )
    (net (code "6") (name "3.3V-SSD") (class "Default")
      (node (ref "C15") (pin "2") (pinfunction "2_2") (pintype "input"))
      (node (ref "C16") (pin "2") (pinfunction "2_2") (pintype "input"))
      (node (ref "CN5") (pin "12") (pinfunction "12_12") (pintype "input"))
      (node (ref "CN5") (pin "14") (pinfunction "14_14") (pintype "input"))
      (node (ref "CN5") (pin "16") (pinfunction "16_16") (pintype "input"))
      (node (ref "CN5") (pin "18") (pinfunction "18_18") (pintype "input"))
      (node (ref "CN5") (pin "2") (pinfunction "2_2") (pintype "input"))
      (node (ref "CN5") (pin "4") (pinfunction "4_4") (pintype "input"))
      (node (ref "CN5") (pin "70") (pinfunction "70_70") (pintype "input"))
      (node (ref "CN5") (pin "72") (pinfunction "72_72") (pintype "input"))
      (node (ref "CN5") (pin "74") (pinfunction "74_74") (pintype "input"))
      (node (ref "L3") (pin "2") (pinfunction "2_2") (pintype "input"))
      (node (ref "LED10") (pin "2") (pinfunction "A_2") (pintype "input"))
      (node (ref "R13") (pin "1") (pinfunction "1_1") (pintype "input"))
      (node (ref "R18") (pin "2") (pinfunction "2_2") (pintype "input"))
    )
    (net (code "7") (name "24V-IN") (class "Default")
      (node (ref "CN7") (pin "10") (pinfunction "10_10") (pintype "input"))
      (node (ref "F1") (pin "1") (pinfunction "1_1") (pintype "input"))
    )
    (net (code "8") (name "485-A") (class "Default")
      (node (ref "CN10") (pin "1") (pinfunction "1_1") (pintype "input"))
      (node (ref "D39") (pin "2") (pinfunction "A1_2") (pintype "input"))
      (node (ref "R112") (pin "1") (pinfunction "1_1") (pintype "input"))
      (node (ref "U23") (pin "6") (pinfunction "A_6") (pintype "input"))
    )
    (net (code "9") (name "485-B") (class "Default")
      (node (ref "CN10") (pin "2") (pinfunction "2_2") (pintype "input"))
      (node (ref "D39") (pin "1") (pinfunction "A1_1") (pintype "input"))
      (node (ref "R112") (pin "2") (pinfunction "2_2") (pintype "input"))
      (node (ref "U23") (pin "7") (pinfunction "B_7") (pintype "input"))
    )
    (net (code "10") (name "ADC-SCL") (class "Default")
      (node (ref "R137") (pin "1") (pinfunction "1_1") (pintype "input"))
      (node (ref "U45") (pin "28") (pinfunction "GPIO13_28") (pintype "bidirectional"))
      (node (ref "U8") (pin "10") (pinfunction "SCL_10") (pintype "input"))
    )
    (net (code "11") (name "ADC-SDA") (class "Default")
      (node (ref "R138") (pin "1") (pinfunction "1_1") (pintype "input"))
      (node (ref "U45") (pin "31") (pinfunction "GPIO12_31") (pintype "bidirectional"))
      (node (ref "U8") (pin "9") (pinfunction "SDA_9") (pintype "input"))
    )
    (net (code "12") (name "ANALOG-OUT0") (class "Default")
      (node (ref "C60") (pin "1") (pinfunction "1_1") (pintype "input"))
      (node (ref "R110") (pin "2") (pinfunction "2_2") (pintype "input"))
      (node (ref "U22") (pin "14") (pinfunction "OUT4_14") (pintype "input"))
      (node (ref "U8") (pin "6") (pinfunction "AIN2_6") (pintype "input"))
    )
    (net (code "13") (name "ANALOG-OUT1") (class "Default")
      (node (ref "C58") (pin "1") (pinfunction "1_1") (pintype "input"))
      (node (ref "R103") (pin "2") (pinfunction "2_2") (pintype "input"))
      (node (ref "U22") (pin "8") (pinfunction "OUT3_8") (pintype "input"))
      (node (ref "U8") (pin "7") (pinfunction "AIN3_7") (pintype "input"))
    )
    (net (code "14") (name "ANALOG-OUT2") (class "Default")
      (node (ref "C54") (pin "1") (pinfunction "1_1") (pintype "input"))
      (node (ref "R89") (pin "2") (pinfunction "2_2") (pintype "input"))
      (node (ref "U22") (pin "7") (pinfunction "OUT2_7") (pintype "input"))
      (node (ref "U8") (pin "4") (pinfunction "AIN0_4") (pintype "input"))
    )
    (net (code "15") (name "ANALOG_INT") (class "Default")
      (node (ref "U45") (pin "29") (pinfunction "GPIO16_29") (pintype "bidirectional"))
      (node (ref "U8") (pin "2") (pinfunction "ALERT/RDY_2") (pintype "input"))
    )
    (net (code "16") (name "C0-") (class "Default")
      (node (ref "CN10") (pin "11") (pinfunction "11_11") (pintype "input"))
      (node (ref "R105") (pin "1") (pinfunction "1_1") (pintype "input"))
    )
    (net (code "17") (name "C1-") (class "Default")
      (node (ref "CN10") (pin "8") (pinfunction "8_8") (pintype "input"))
      (node (ref "R98") (pin "1") (pinfunction "1_1") (pintype "input"))
    )
    (net (code "18") (name "C2-") (class "Default")
      (node (ref "CN10") (pin "5") (pinfunction "5_5") (pintype "input"))
      (node (ref "R35") (pin "1") (pinfunction "1_1") (pintype "input"))
    )
    (net (code "19") (name "CAM1_C_N") (class "Default")
      (node (ref "FPC8") (pin "15") (pinfunction "15_15") (pintype "input"))
      (node (ref "U46") (pin "127") (pinfunction "CAM1_C_N_127") (pintype "bidirectional"))
    )
    (net (code "20") (name "CAM1_C_P") (class "Default")
      (node (ref "FPC8") (pin "14") (pinfunction "14_14") (pintype "input"))
      (node (ref "U46") (pin "129") (pinfunction "CAM1_C_P_129") (pintype "bidirectional"))
    )
    (net (code "21") (name "CAM1_D0_N") (class "Default")
      (node (ref "FPC8") (pin "21") (pinfunction "21_21") (pintype "input"))
      (node (ref "U46") (pin "115") (pinfunction "CAM1_D0_N_115") (pintype "bidirectional"))
    )
    (net (code "22") (name "CAM1_D0_P") (class "Default")
      (node (ref "FPC8") (pin "20") (pinfunction "20_20") (pintype "input"))
      (node (ref "U46") (pin "117") (pinfunction "CAM1_D0_P_117") (pintype "bidirectional"))
    )
    (net (code "23") (name "CAM1_D1_N") (class "Default")
      (node (ref "FPC8") (pin "18") (pinfunction "18_18") (pintype "input"))
      (node (ref "U46") (pin "121") (pinfunction "CAM1_D1_N_121") (pintype "bidirectional"))
    )
    (net (code "24") (name "CAM1_D1_P") (class "Default")
      (node (ref "FPC8") (pin "17") (pinfunction "17_17") (pintype "input"))
      (node (ref "U46") (pin "123") (pinfunction "CAM1_D1_P_123") (pintype "bidirectional"))
    )
    (net (code "25") (name "CAM1_D2_N") (class "Default")
      (node (ref "FPC8") (pin "12") (pinfunction "12_12") (pintype "input"))
      (node (ref "U46") (pin "133") (pinfunction "CAM1_D2_N_133") (pintype "bidirectional"))
    )
    (net (code "26") (name "CAM1_D2_P") (class "Default")
      (node (ref "FPC8") (pin "11") (pinfunction "11_11") (pintype "input"))
      (node (ref "U46") (pin "135") (pinfunction "CAM1_D2_P_135") (pintype "bidirectional"))
    )
    (net (code "27") (name "CAM1_D3_N") (class "Default")
      (node (ref "FPC8") (pin "9") (pinfunction "9_9") (pintype "input"))
      (node (ref "U46") (pin "139") (pinfunction "CAM1_D3_N_139") (pintype "bidirectional"))
    )
    (net (code "28") (name "CAM1_D3_P") (class "Default")
      (node (ref "FPC8") (pin "8") (pinfunction "8_8") (pintype "input"))
      (node (ref "U46") (pin "141") (pinfunction "CAM1_D3_P_141") (pintype "bidirectional"))
    )
    (net (code "29") (name "Camera_GPIO") (class "Default")
      (node (ref "FPC8") (pin "6") (pinfunction "6_6") (pintype "input"))
      (node (ref "U45") (pin "97") (pinfunction "Camera_GPIO_97") (pintype "bidirectional"))
    )
    (net (code "30") (name "ETH_LEDG") (class "Default")
      (node (ref "R74") (pin "2") (pinfunction "2_2") (pintype "input"))
      (node (ref "U45") (pin "15") (pinfunction "ETH_nLED3_15") (pintype "bidirectional"))
    )
    (net (code "31") (name "ETH_LEDY") (class "Default")
      (node (ref "R75") (pin "2") (pinfunction "2_2") (pintype "input"))
      (node (ref "U45") (pin "17") (pinfunction "ETH_nLED2_17") (pintype "bidirectional"))
    )
    (net (code "32") (name "ETH_P0_N") (class "Default")
      (node (ref "RJ2") (pin "P3") (pinfunction "MDI0-_P3") (pintype "input"))
      (node (ref "U21") (pin "2") (pinfunction "2_2") (pintype "input"))
      (node (ref "U21") (pin "9") (pinfunction "9_9") (pintype "input"))
      (node (ref "U45") (pin "10") (pinfunction "ETH_P0_N_10") (pintype "bidirectional"))
    )
    (net (code "33") (name "ETH_P0_P") (class "Default")
      (node (ref "RJ2") (pin "P2") (pinfunction "MDI0+_P2") (pintype "input"))
      (node (ref "U21") (pin "1") (pinfunction "1_1") (pintype "input"))
      (node (ref "U21") (pin "10") (pinfunction "10_10") (pintype "input"))
      (node (ref "U45") (pin "12") (pinfunction "ETH_P0_P_12") (pintype "bidirectional"))
    )
    (net (code "34") (name "ETH_P1_N") (class "Default")
      (node (ref "RJ2") (pin "P7") (pinfunction "MDI1-_P7") (pintype "input"))
      (node (ref "U20") (pin "2") (pinfunction "2_2") (pintype "input"))
      (node (ref "U20") (pin "9") (pinfunction "9_9") (pintype "input"))
      (node (ref "U45") (pin "6") (pinfunction "ETH_P1_N_6") (pintype "bidirectional"))
    )
    (net (code "35") (name "ETH_P1_P") (class "Default")
      (node (ref "RJ2") (pin "P4") (pinfunction "MDI1+_P4") (pintype "input"))
      (node (ref "U21") (pin "4") (pinfunction "4_4") (pintype "input"))
      (node (ref "U21") (pin "7") (pinfunction "7_7") (pintype "input"))
      (node (ref "U45") (pin "4") (pinfunction "ETH_P1_P_4") (pintype "bidirectional"))
    )
    (net (code "36") (name "ETH_P2_N") (class "Default")
      (node (ref "RJ2") (pin "P6") (pinfunction "MDI2-_P6") (pintype "input"))
      (node (ref "U20") (pin "1") (pinfunction "1_1") (pintype "input"))
      (node (ref "U20") (pin "10") (pinfunction "10_10") (pintype "input"))
      (node (ref "U45") (pin "9") (pinfunction "ETH_P2_N_9") (pintype "bidirectional"))
    )
    (net (code "37") (name "ETH_P2_P") (class "Default")
      (node (ref "RJ2") (pin "P5") (pinfunction "MDI2+_P5") (pintype "input"))
      (node (ref "U21") (pin "5") (pinfunction "5_5") (pintype "input"))
      (node (ref "U21") (pin "6") (pinfunction "6_6") (pintype "input"))
      (node (ref "U45") (pin "11") (pinfunction "ETH_P2_P_11") (pintype "bidirectional"))
    )
    (net (code "38") (name "ETH_P3_N") (class "Default")
      (node (ref "RJ2") (pin "P9") (pinfunction "MDI3-_P9") (pintype "input"))
      (node (ref "U20") (pin "5") (pinfunction "5_5") (pintype "input"))
      (node (ref "U20") (pin "6") (pinfunction "6_6") (pintype "input"))
      (node (ref "U45") (pin "5") (pinfunction "ETH_P3_N_5") (pintype "bidirectional"))
    )
    (net (code "39") (name "ETH_P3_P") (class "Default")
      (node (ref "RJ2") (pin "P8") (pinfunction "MDI3+_P8") (pintype "input"))
      (node (ref "U20") (pin "4") (pinfunction "4_4") (pintype "input"))
      (node (ref "U20") (pin "7") (pinfunction "7_7") (pintype "input"))
      (node (ref "U45") (pin "3") (pinfunction "ETH_P3_P_3") (pintype "bidirectional"))
    )
    (net (code "40") (name "GMS_PWR") (class "Default")
      (node (ref "R81") (pin "2") (pinfunction "2_2") (pintype "input"))
      (node (ref "U3") (pin "3") (pinfunction "EN_3") (pintype "input"))
      (node (ref "U45") (pin "26") (pinfunction "GPIO19_26") (pintype "bidirectional"))
    )
    (net (code "41") (name "GND") (class "Default")
      (node (ref "B1") (pin "2") (pinfunction "2_2") (pintype "input"))
      (node (ref "C100") (pin "1") (pinfunction "1_1") (pintype "input"))
      (node (ref "C101") (pin "1") (pinfunction "1_1") (pintype "input"))
      (node (ref "C102") (pin "1") (pinfunction "1_1") (pintype "input"))
      (node (ref "C103") (pin "1") (pinfunction "1_1") (pintype "input"))
      (node (ref "C104") (pin "1") (pinfunction "1_1") (pintype "input"))
      (node (ref "C105") (pin "1") (pinfunction "1_1") (pintype "input"))
      (node (ref "C106") (pin "1") (pinfunction "1_1") (pintype "input"))
      (node (ref "C11") (pin "1") (pinfunction "1_1") (pintype "input"))
      (node (ref "C12") (pin "1") (pinfunction "1_1") (pintype "input"))
      (node (ref "C15") (pin "1") (pinfunction "1_1") (pintype "input"))
      (node (ref "C16") (pin "1") (pinfunction "1_1") (pintype "input"))
      (node (ref "C18") (pin "1") (pinfunction "1_1") (pintype "input"))
      (node (ref "C2") (pin "1") (pinfunction "1_1") (pintype "input"))
      (node (ref "C23") (pin "1") (pinfunction "1_1") (pintype "input"))
      (node (ref "C25") (pin "1") (pinfunction "1_1") (pintype "input"))
      (node (ref "C26") (pin "2") (pinfunction "2_2") (pintype "input"))
      (node (ref "C27") (pin "1") (pinfunction "1_1") (pintype "input"))
      (node (ref "C28") (pin "2") (pinfunction "2_2") (pintype "input"))
      (node (ref "C29") (pin "1") (pinfunction "1_1") (pintype "input"))
      (node (ref "C3") (pin "1") (pinfunction "1_1") (pintype "input"))
      (node (ref "C30") (pin "1") (pinfunction "1_1") (pintype "input"))
      (node (ref "C31") (pin "2") (pinfunction "2_2") (pintype "input"))
      (node (ref "C32") (pin "1") (pinfunction "1_1") (pintype "input"))
      (node (ref "C33") (pin "1") (pinfunction "1_1") (pintype "input"))
      (node (ref "C36") (pin "1") (pinfunction "1_1") (pintype "input"))
      (node (ref "C37") (pin "1") (pinfunction "1_1") (pintype "input"))
      (node (ref "C38") (pin "2") (pinfunction "2_2") (pintype "input"))
      (node (ref "C40") (pin "1") (pinfunction "1_1") (pintype "input"))
      (node (ref "C44") (pin "1") (pinfunction "1_1") (pintype "input"))
      (node (ref "C45") (pin "1") (pinfunction "1_1") (pintype "input"))
      (node (ref "C51") (pin "1") (pinfunction "1_1") (pintype "input"))
      (node (ref "C52") (pin "1") (pinfunction "1_1") (pintype "input"))
      (node (ref "C53") (pin "1") (pinfunction "1_1") (pintype "input"))
      (node (ref "C57") (pin "1") (pinfunction "1_1") (pintype "input"))
      (node (ref "C59") (pin "1") (pinfunction "1_1") (pintype "input"))
      (node (ref "C6") (pin "1") (pinfunction "1_1") (pintype "input"))
      (node (ref "C61") (pin "2") (pinfunction "2_2") (pintype "input"))
      (node (ref "C62") (pin "1") (pinfunction "1_1") (pintype "input"))
      (node (ref "C63") (pin "1") (pinfunction "1_1") (pintype "input"))
      (node (ref "C64") (pin "1") (pinfunction "1_1") (pintype "input"))
      (node (ref "C66") (pin "2") (pinfunction "2_2") (pintype "input"))
      (node (ref "C67") (pin "1") (pinfunction "1_1") (pintype "input"))
      (node (ref "C68") (pin "1") (pinfunction "1_1") (pintype "input"))
      (node (ref "C69") (pin "1") (pinfunction "1_1") (pintype "input"))
      (node (ref "C7") (pin "1") (pinfunction "1_1") (pintype "input"))
      (node (ref "C70") (pin "1") (pinfunction "1_1") (pintype "input"))
      (node (ref "C71") (pin "1") (pinfunction "1_1") (pintype "input"))
      (node (ref "C72") (pin "1") (pinfunction "1_1") (pintype "input"))
      (node (ref "C85") (pin "1") (pinfunction "1_1") (pintype "input"))
      (node (ref "C86") (pin "1") (pinfunction "1_1") (pintype "input"))
      (node (ref "C88") (pin "2") (pinfunction "2_2") (pintype "input"))
      (node (ref "C93") (pin "1") (pinfunction "1_1") (pintype "input"))
      (node (ref "C94") (pin "1") (pinfunction "1_1") (pintype "input"))
      (node (ref "C95") (pin "2") (pinfunction "2_2") (pintype "input"))
      (node (ref "C97") (pin "1") (pinfunction "1_1") (pintype "input"))
      (node (ref "C98") (pin "1") (pinfunction "1_1") (pintype "input"))
      (node (ref "C99") (pin "1") (pinfunction "1_1") (pintype "input"))
      (node (ref "CARD1") (pin "10") (pinfunction "10_10") (pintype "input"))
      (node (ref "CARD1") (pin "11") (pinfunction "11_11") (pintype "input"))
      (node (ref "CARD1") (pin "12") (pinfunction "12_12") (pintype "input"))
      (node (ref "CARD1") (pin "13") (pinfunction "13_13") (pintype "input"))
      (node (ref "CARD1") (pin "6") (pinfunction "VSS_6") (pintype "input"))
      (node (ref "CARD2") (pin "10") (pinfunction "GND_10") (pintype "input"))
      (node (ref "CARD2") (pin "7") (pinfunction "GND_7") (pintype "input"))
      (node (ref "CARD2") (pin "8") (pinfunction "GND_8") (pintype "input"))
      (node (ref "CARD2") (pin "9") (pinfunction "GND_9") (pintype "input"))
      (node (ref "CARD2") (pin "C5") (pinfunction "GND_C5") (pintype "input"))
      (node (ref "CN10") (pin "3") (pinfunction "3_3") (pintype "input"))
      (node (ref "CN17") (pin "1") (pinfunction "1_1") (pintype "input"))
      (node (ref "CN20") (pin "10") (pinfunction "TMDSData0shield_10") (pintype "unspecified"))
      (node (ref "CN20") (pin "13") (pinfunction "TMDSClockshield_13") (pintype "unspecified"))
      (node (ref "CN20") (pin "16") (pinfunction "DDC/CECGND_16") (pintype "unspecified"))
      (node (ref "CN20") (pin "20") (pinfunction "EH_20") (pintype "unspecified"))
      (node (ref "CN20") (pin "4") (pinfunction "TMDSData2shield_4") (pintype "unspecified"))
      (node (ref "CN20") (pin "7") (pinfunction "TMDSData1shield_7") (pintype "unspecified"))
      (node (ref "CN3") (pin "11") (pinfunction "11_11") (pintype "input"))
      (node (ref "CN3") (pin "27") (pinfunction "27_27") (pintype "input"))
      (node (ref "CN3") (pin "3") (pinfunction "3_3") (pintype "input"))
      (node (ref "CN3") (pin "33") (pinfunction "33_33") (pintype "input"))
      (node (ref "CN3") (pin "39") (pinfunction "39_39") (pintype "input"))
      (node (ref "CN3") (pin "45") (pinfunction "45_45") (pintype "input"))
      (node (ref "CN3") (pin "5") (pinfunction "5_5") (pintype "input"))
      (node (ref "CN3") (pin "51") (pinfunction "51_51") (pintype "input"))
      (node (ref "CN3") (pin "57") (pinfunction "57_57") (pintype "input"))
      (node (ref "CN3") (pin "71") (pinfunction "71_71") (pintype "input"))
      (node (ref "CN3") (pin "73") (pinfunction "73_73") (pintype "input"))
      (node (ref "CN3") (pin "76") (pinfunction "76_76") (pintype "input"))
      (node (ref "CN3") (pin "77") (pinfunction "77_77") (pintype "input"))
      (node (ref "CN5") (pin "15") (pinfunction "15_15") (pintype "input"))
      (node (ref "CN5") (pin "27") (pinfunction "27_27") (pintype "input"))
      (node (ref "CN5") (pin "3") (pinfunction "3_3") (pintype "input"))
      (node (ref "CN5") (pin "33") (pinfunction "33_33") (pintype "input"))
      (node (ref "CN5") (pin "39") (pinfunction "39_39") (pintype "input"))
      (node (ref "CN5") (pin "45") (pinfunction "45_45") (pintype "input"))
      (node (ref "CN5") (pin "51") (pinfunction "51_51") (pintype "input"))
      (node (ref "CN5") (pin "57") (pinfunction "57_57") (pintype "input"))
      (node (ref "CN5") (pin "71") (pinfunction "71_71") (pintype "input"))
      (node (ref "CN5") (pin "73") (pinfunction "73_73") (pintype "input"))
      (node (ref "CN5") (pin "76") (pinfunction "76_76") (pintype "input"))
      (node (ref "CN5") (pin "77") (pinfunction "77_77") (pintype "input"))
      (node (ref "CN5") (pin "9") (pinfunction "9_9") (pintype "input"))
      (node (ref "CN7") (pin "9") (pinfunction "9_9") (pintype "input"))
      (node (ref "D1") (pin "1") (pinfunction "1_1") (pintype "input"))
      (node (ref "D19") (pin "1") (pinfunction "1_1") (pintype "input"))
      (node (ref "D27") (pin "1") (pinfunction "1_1") (pintype "input"))
      (node (ref "D30") (pin "1") (pinfunction "1_1") (pintype "input"))
      (node (ref "D31") (pin "1") (pinfunction "1_1") (pintype "input"))
      (node (ref "D32") (pin "2") (pinfunction "2_2") (pintype "input"))
      (node (ref "D33") (pin "1") (pinfunction "1_1") (pintype "input"))
      (node (ref "D36") (pin "1") (pinfunction "1_1") (pintype "input"))
      (node (ref "D37") (pin "1") (pinfunction "1_1") (pintype "input"))
      (node (ref "D38") (pin "2") (pinfunction "2_2") (pintype "input"))
      (node (ref "D39") (pin "3") (pinfunction "K_3") (pintype "input"))
      (node (ref "D4") (pin "1") (pinfunction "1_1") (pintype "input"))
      (node (ref "D43") (pin "1") (pinfunction "A_1") (pintype "input"))
      (node (ref "D5") (pin "1") (pinfunction "1_1") (pintype "input"))
      (node (ref "D6") (pin "2") (pinfunction "2_2") (pintype "input"))
      (node (ref "FPC8") (pin "10") (pinfunction "10_10") (pintype "input"))
      (node (ref "FPC8") (pin "13") (pinfunction "13_13") (pintype "input"))
      (node (ref "FPC8") (pin "16") (pinfunction "16_16") (pintype "input"))
      (node (ref "FPC8") (pin "19") (pinfunction "19_19") (pintype "input"))
      (node (ref "FPC8") (pin "22") (pinfunction "22_22") (pintype "input"))
      (node (ref "FPC8") (pin "23") (pinfunction "23_23") (pintype "input"))
      (node (ref "FPC8") (pin "24") (pinfunction "24_24") (pintype "input"))
      (node (ref "FPC8") (pin "4") (pinfunction "4_4") (pintype "input"))
      (node (ref "FPC8") (pin "7") (pinfunction "7_7") (pintype "input"))
      (node (ref "LED6") (pin "1") (pinfunction "C_1") (pintype "input"))
      (node (ref "P4") (pin "1") (pinfunction "1_1") (pintype "input"))
      (node (ref "P4") (pin "2") (pinfunction "2_2") (pintype "input"))
      (node (ref "P4") (pin "3") (pinfunction "3_3") (pintype "input"))
      (node (ref "P4") (pin "4") (pinfunction "4_4") (pintype "input"))
      (node (ref "Q7") (pin "2") (pinfunction "S_2") (pintype "input"))
      (node (ref "R104") (pin "1") (pinfunction "1_1") (pintype "input"))
      (node (ref "R111") (pin "1") (pinfunction "1_1") (pintype "input"))
      (node (ref "R122") (pin "1") (pinfunction "1_1") (pintype "input"))
      (node (ref "R125") (pin "1") (pinfunction "1_1") (pintype "input"))
      (node (ref "R128") (pin "1") (pinfunction "1_1") (pintype "input"))
      (node (ref "R129") (pin "1") (pinfunction "1_1") (pintype "input"))
      (node (ref "R163") (pin "1") (pinfunction "1_1") (pintype "input"))
      (node (ref "R166") (pin "2") (pinfunction "2_2") (pintype "input"))
      (node (ref "R17") (pin "1") (pinfunction "1_1") (pintype "input"))
      (node (ref "R19") (pin "1") (pinfunction "1_1") (pintype "input"))
      (node (ref "R20") (pin "1") (pinfunction "1_1") (pintype "input"))
      (node (ref "R4") (pin "1") (pinfunction "1_1") (pintype "input"))
      (node (ref "R46") (pin "1") (pinfunction "1_1") (pintype "input"))
      (node (ref "R54") (pin "1") (pinfunction "1_1") (pintype "input"))
      (node (ref "R56") (pin "1") (pinfunction "1_1") (pintype "input"))
      (node (ref "R57") (pin "1") (pinfunction "1_1") (pintype "input"))
      (node (ref "R6") (pin "1") (pinfunction "1_1") (pintype "input"))
      (node (ref "R7") (pin "1") (pinfunction "1_1") (pintype "input"))
      (node (ref "R79") (pin "1") (pinfunction "1_1") (pintype "input"))
      (node (ref "R80") (pin "1") (pinfunction "1_1") (pintype "input"))
      (node (ref "R81") (pin "1") (pinfunction "1_1") (pintype "input"))
      (node (ref "R82") (pin "1") (pinfunction "1_1") (pintype "input"))
      (node (ref "R84") (pin "1") (pinfunction "1_1") (pintype "input"))
      (node (ref "R90") (pin "1") (pinfunction "1_1") (pintype "input"))
      (node (ref "RJ2") (pin "P10") (pinfunction "P10_P10") (pintype "input"))
      (node (ref "RJ2") (pin "SHIELD0") (pinfunction "SHIELD0_SHIELD0") (pintype "input"))
      (node (ref "RJ2") (pin "SHIELD1") (pinfunction "SHIELD1_SHIELD1") (pintype "input"))
      (node (ref "SW1") (pin "1") (pinfunction "1_1") (pintype "input"))
      (node (ref "SW1") (pin "4") (pinfunction "4_4") (pintype "input"))
      (node (ref "U10") (pin "1") (pinfunction "VSS_1") (pintype "input"))
      (node (ref "U12") (pin "1") (pinfunction "1_1") (pintype "input"))
      (node (ref "U14") (pin "4") (pinfunction "GND_4") (pintype "input"))
      (node (ref "U14") (pin "9") (pinfunction "EPAD_9") (pintype "input"))
      (node (ref "U15") (pin "3") (pinfunction "EM_3") (pintype "input"))
      (node (ref "U16") (pin "3") (pinfunction "EM_3") (pintype "input"))
      (node (ref "U17") (pin "3") (pinfunction "EM_3") (pintype "input"))
      (node (ref "U19") (pin "4") (pinfunction "GND_4") (pintype "input"))
      (node (ref "U20") (pin "3") (pinfunction "3_3") (pintype "input"))
      (node (ref "U20") (pin "8") (pinfunction "8_8") (pintype "input"))
      (node (ref "U21") (pin "3") (pinfunction "3_3") (pintype "input"))
      (node (ref "U21") (pin "8") (pinfunction "8_8") (pintype "input"))
      (node (ref "U22") (pin "11") (pinfunction "VCC-_11") (pintype "input"))
      (node (ref "U23") (pin "5") (pinfunction "GND_5") (pintype "input"))
      (node (ref "U24") (pin "7") (pinfunction "GND_7") (pintype "input"))
      (node (ref "U25") (pin "2") (pinfunction "GND_2") (pintype "input"))
      (node (ref "U28") (pin "10") (pinfunction "OE#_10") (pintype "input"))
      (node (ref "U28") (pin "5") (pinfunction "GND_5") (pintype "input"))
      (node (ref "U3") (pin "4") (pinfunction "GND_4") (pintype "input"))
      (node (ref "U3") (pin "9") (pinfunction "EPAD_9") (pintype "input"))
      (node (ref "U31") (pin "3") (pinfunction "3_3") (pintype "input"))
      (node (ref "U31") (pin "8") (pinfunction "8_8") (pintype "input"))
      (node (ref "U33") (pin "3") (pinfunction "3_3") (pintype "input"))
      (node (ref "U33") (pin "8") (pinfunction "8_8") (pintype "input"))
      (node (ref "U4") (pin "4") (pinfunction "GND_4") (pintype "input"))
      (node (ref "U4") (pin "9") (pinfunction "EPAD_9") (pintype "input"))
      (node (ref "U41") (pin "2") (pinfunction "GND_2") (pintype "input"))
      (node (ref "U45") (pin "1") (pinfunction "GND_1") (pintype "bidirectional"))
      (node (ref "U45") (pin "13") (pinfunction "GND_13") (pintype "bidirectional"))
      (node (ref "U45") (pin "14") (pinfunction "GND_14") (pintype "bidirectional"))
      (node (ref "U45") (pin "2") (pinfunction "GND_2") (pintype "bidirectional"))
      (node (ref "U45") (pin "22") (pinfunction "GND_22") (pintype "bidirectional"))
      (node (ref "U45") (pin "23") (pinfunction "GND_23") (pintype "bidirectional"))
      (node (ref "U45") (pin "32") (pinfunction "GND_32") (pintype "bidirectional"))
      (node (ref "U45") (pin "33") (pinfunction "GND_33") (pintype "bidirectional"))
      (node (ref "U45") (pin "42") (pinfunction "GND_42") (pintype "bidirectional"))
      (node (ref "U45") (pin "43") (pinfunction "GND_43") (pintype "bidirectional"))
      (node (ref "U45") (pin "52") (pinfunction "GND_52") (pintype "bidirectional"))
      (node (ref "U45") (pin "53") (pinfunction "GND_53") (pintype "bidirectional"))
      (node (ref "U45") (pin "59") (pinfunction "GND_59") (pintype "bidirectional"))
      (node (ref "U45") (pin "60") (pinfunction "GND_60") (pintype "bidirectional"))
      (node (ref "U45") (pin "65") (pinfunction "GND_65") (pintype "bidirectional"))
      (node (ref "U45") (pin "66") (pinfunction "GND_66") (pintype "bidirectional"))
      (node (ref "U45") (pin "7") (pinfunction "GND_7") (pintype "bidirectional"))
      (node (ref "U45") (pin "71") (pinfunction "GND_71") (pintype "bidirectional"))
      (node (ref "U45") (pin "74") (pinfunction "GND_74") (pintype "bidirectional"))
      (node (ref "U45") (pin "8") (pinfunction "GND_8") (pintype "bidirectional"))
      (node (ref "U45") (pin "98") (pinfunction "GND_98") (pintype "bidirectional"))
      (node (ref "U46") (pin "107") (pinfunction "GND_107") (pintype "bidirectional"))
      (node (ref "U46") (pin "108") (pinfunction "GND_108") (pintype "bidirectional"))
      (node (ref "U46") (pin "113") (pinfunction "GND_113") (pintype "bidirectional"))
      (node (ref "U46") (pin "114") (pinfunction "GND_114") (pintype "bidirectional"))
      (node (ref "U46") (pin "119") (pinfunction "GND_119") (pintype "bidirectional"))
      (node (ref "U46") (pin "120") (pinfunction "GND_120") (pintype "bidirectional"))
      (node (ref "U46") (pin "125") (pinfunction "GND_125") (pintype "bidirectional"))
      (node (ref "U46") (pin "126") (pinfunction "GND_126") (pintype "bidirectional"))
      (node (ref "U46") (pin "131") (pinfunction "GND_131") (pintype "bidirectional"))
      (node (ref "U46") (pin "132") (pinfunction "GND_132") (pintype "bidirectional"))
      (node (ref "U46") (pin "137") (pinfunction "GND_137") (pintype "bidirectional"))
      (node (ref "U46") (pin "138") (pinfunction "GND_138") (pintype "bidirectional"))
      (node (ref "U46") (pin "144") (pinfunction "GND_144") (pintype "bidirectional"))
      (node (ref "U46") (pin "150") (pinfunction "GND_150") (pintype "bidirectional"))
      (node (ref "U46") (pin "155") (pinfunction "GND_155") (pintype "bidirectional"))
      (node (ref "U46") (pin "156") (pinfunction "GND_156") (pintype "bidirectional"))
      (node (ref "U46") (pin "161") (pinfunction "GND_161") (pintype "bidirectional"))
      (node (ref "U46") (pin "162") (pinfunction "GND_162") (pintype "bidirectional"))
      (node (ref "U46") (pin "167") (pinfunction "GND_167") (pintype "bidirectional"))
      (node (ref "U46") (pin "168") (pinfunction "GND_168") (pintype "bidirectional"))
      (node (ref "U46") (pin "173") (pinfunction "GND_173") (pintype "bidirectional"))
      (node (ref "U46") (pin "174") (pinfunction "GND_174") (pintype "bidirectional"))
      (node (ref "U46") (pin "179") (pinfunction "GND_179") (pintype "bidirectional"))
      (node (ref "U46") (pin "180") (pinfunction "GND_180") (pintype "bidirectional"))
      (node (ref "U46") (pin "185") (pinfunction "GND_185") (pintype "bidirectional"))
      (node (ref "U46") (pin "186") (pinfunction "GND_186") (pintype "bidirectional"))
      (node (ref "U46") (pin "191") (pinfunction "GND_191") (pintype "bidirectional"))
      (node (ref "U46") (pin "192") (pinfunction "GND_192") (pintype "bidirectional"))
      (node (ref "U46") (pin "197") (pinfunction "GND_197") (pintype "bidirectional"))
      (node (ref "U46") (pin "198") (pinfunction "GND_198") (pintype "bidirectional"))
      (node (ref "U48") (pin "1") (pinfunction "1_1") (pintype "input"))
      (node (ref "U6") (pin "3") (pinfunction "EM_3") (pintype "input"))
      (node (ref "U8") (pin "1") (pinfunction "ADDR_1") (pintype "input"))
      (node (ref "U8") (pin "3") (pinfunction "GND_3") (pintype "input"))
      (node (ref "USB16") (pin "11") (pinfunction "TMDSClockShield_11") (pintype "input"))
      (node (ref "USB16") (pin "17") (pinfunction "DDC/CECGround_17") (pintype "input"))
      (node (ref "USB16") (pin "2") (pinfunction "TMDSData2Shield_2") (pintype "input"))
      (node (ref "USB16") (pin "20") (pinfunction "EH_20") (pintype "input"))
      (node (ref "USB16") (pin "5") (pinfunction "TMDSData1Shield_5") (pintype "input"))
      (node (ref "USB16") (pin "8") (pinfunction "TMDSData0Shield_8") (pintype "input"))
      (node (ref "USB7") (pin "10") (pinfunction "SHELL_10") (pintype "input"))
      (node (ref "USB7") (pin "11") (pinfunction "SHELL_11") (pintype "input"))
      (node (ref "USB7") (pin "12") (pinfunction "SHELL_12") (pintype "input"))
      (node (ref "USB7") (pin "4") (pinfunction "GND_4") (pintype "input"))
      (node (ref "USB7") (pin "8") (pinfunction "GND_8") (pintype "input"))
      (node (ref "USB7") (pin "9") (pinfunction "SHELL_9") (pintype "input"))
      (node (ref "USB8") (pin "5") (pinfunction "GND_5") (pintype "input"))
      (node (ref "USB8") (pin "6") (pinfunction "EH_6") (pintype "input"))
      (node (ref "X1") (pin "2") (pinfunction "GND_2") (pintype "input"))
      (node (ref "X1") (pin "4") (pinfunction "GND_4") (pintype "input"))
    )
    (net (code "42") (name "GSM_COEX_RX") (class "Default")
      (node (ref "CN3") (pin "62") (pinfunction "62_62") (pintype "input"))
      (node (ref "TP5") (pin "1") (pinfunction "1_1") (pintype "unspecified"))
    )
    (net (code "43") (name "GSM_COEX_TX") (class "Default")
      (node (ref "CN3") (pin "64") (pinfunction "64_64") (pintype "input"))
      (node (ref "TP6") (pin "1") (pinfunction "1_1") (pintype "unspecified"))
    )
    (net (code "44") (name "GSM_OFF") (class "Default")
      (node (ref "CN3") (pin "6") (pinfunction "6_6") (pintype "input"))
      (node (ref "R11") (pin "2") (pinfunction "2_2") (pintype "input"))
      (node (ref "U45") (pin "30") (pinfunction "GPIO6_30") (pintype "bidirectional"))
    )
    (net (code "45") (name "GSM_RESET") (class "Default")
      (node (ref "Q7") (pin "1") (pinfunction "G_1") (pintype "input"))
      (node (ref "R166") (pin "1") (pinfunction "1_1") (pintype "input"))
      (node (ref "U45") (pin "34") (pinfunction "GPIO5_34") (pintype "bidirectional"))
    )
    (net (code "46") (name "HDMI0_CEC") (class "Default")
      (node (ref "CN20") (pin "15") (pinfunction "CEC_15") (pintype "unspecified"))
      (node (ref "U46") (pin "151") (pinfunction "HDMI0_CEC_151") (pintype "bidirectional"))
      (node (ref "USB16") (pin "13") (pinfunction "CEC_13") (pintype "input"))
    )
    (net (code "47") (name "HDMI0_CLK_N") (class "Default")
      (node (ref "CN20") (pin "14") (pinfunction "TMDSClock-_14") (pintype "unspecified"))
      (node (ref "U46") (pin "190") (pinfunction "HDMI0_CLK_N_190") (pintype "bidirectional"))
      (node (ref "USB16") (pin "12") (pinfunction "TMDSClock-_12") (pintype "input"))
    )
    (net (code "48") (name "HDMI0_CLK_P") (class "Default")
      (node (ref "CN20") (pin "12") (pinfunction "TMDSClock+_12") (pintype "unspecified"))
      (node (ref "U46") (pin "188") (pinfunction "HDMI0_CLK_P_188") (pintype "bidirectional"))
      (node (ref "USB16") (pin "10") (pinfunction "TMDSClock+_10") (pintype "input"))
    )
    (net (code "49") (name "HDMI0_HOTPLUG") (class "Default")
      (node (ref "CN20") (pin "1") (pinfunction "HOTPLUGDETECT_1") (pintype "unspecified"))
      (node (ref "U46") (pin "153") (pinfunction "HDMI0_HOTPLUG_153") (pintype "bidirectional"))
      (node (ref "USB16") (pin "19") (pinfunction "HotPlugDetect_19") (pintype "input"))
    )
    (net (code "50") (name "HDMI0_SCL") (class "Default")
      (node (ref "CN20") (pin "17") (pinfunction "SCL_17") (pintype "unspecified"))
      (node (ref "U46") (pin "200") (pinfunction "HDMI0_SCL_200") (pintype "bidirectional"))
      (node (ref "USB16") (pin "15") (pinfunction "SCL_15") (pintype "input"))
    )
    (net (code "51") (name "HDMI0_SDA") (class "Default")
      (node (ref "CN20") (pin "18") (pinfunction "SDA_18") (pintype "unspecified"))
      (node (ref "U46") (pin "199") (pinfunction "HDMI0_SDA_199") (pintype "bidirectional"))
      (node (ref "USB16") (pin "16") (pinfunction "SDA_16") (pintype "input"))
    )
    (net (code "52") (name "HDMI0_TX0_N") (class "Default")
      (node (ref "CN20") (pin "11") (pinfunction "TMDSData0-_11") (pintype "unspecified"))
      (node (ref "U46") (pin "184") (pinfunction "HDMI0_TX0_N_184") (pintype "bidirectional"))
      (node (ref "USB16") (pin "9") (pinfunction "TMDSData0-_9") (pintype "input"))
    )
    (net (code "53") (name "HDMI0_TX0_P") (class "Default")
      (node (ref "CN20") (pin "9") (pinfunction "TMDSData0+_9") (pintype "unspecified"))
      (node (ref "U46") (pin "182") (pinfunction "HDMI0_TX0_P_182") (pintype "bidirectional"))
      (node (ref "USB16") (pin "7") (pinfunction "TMDSData0+_7") (pintype "input"))
    )
    (net (code "54") (name "HDMI0_TX1_N") (class "Default")
      (node (ref "CN20") (pin "8") (pinfunction "TMDSData1-_8") (pintype "unspecified"))
      (node (ref "U46") (pin "178") (pinfunction "HDMI0_TX1_N_178") (pintype "bidirectional"))
      (node (ref "USB16") (pin "6") (pinfunction "TMDSData1-_6") (pintype "input"))
    )
    (net (code "55") (name "HDMI0_TX1_P") (class "Default")
      (node (ref "CN20") (pin "6") (pinfunction "TMDSData1+_6") (pintype "unspecified"))
      (node (ref "U46") (pin "176") (pinfunction "HDMI0_TX1_P_176") (pintype "bidirectional"))
      (node (ref "USB16") (pin "4") (pinfunction "TMDSData1+_4") (pintype "input"))
    )
    (net (code "56") (name "HDMI0_TX2_N") (class "Default")
      (node (ref "CN20") (pin "5") (pinfunction "TMDSData2-_5") (pintype "unspecified"))
      (node (ref "U46") (pin "172") (pinfunction "HDMI0_TX2_N_172") (pintype "bidirectional"))
      (node (ref "USB16") (pin "3") (pinfunction "TMDSData2-_3") (pintype "input"))
    )
    (net (code "57") (name "HDMI0_TX2_P") (class "Default")
      (node (ref "CN20") (pin "3") (pinfunction "TMDSData2+_3") (pintype "unspecified"))
      (node (ref "U46") (pin "170") (pinfunction "HDMI0_TX2_P_170") (pintype "bidirectional"))
      (node (ref "USB16") (pin "1") (pinfunction "TMDSData2+_1") (pintype "input"))
    )
    (net (code "58") (name "HUB_1.8V") (class "Default")
      (node (ref "C28") (pin "1") (pinfunction "1_1") (pintype "input"))
      (node (ref "C29") (pin "2") (pinfunction "2_2") (pintype "input"))
      (node (ref "U10") (pin "12") (pinfunction "VDD18_12") (pintype "input"))
      (node (ref "U10") (pin "28") (pinfunction "VDD18_28") (pintype "input"))
    )
    (net (code "59") (name "HUB_3.3V") (class "Default")
      (node (ref "C23") (pin "2") (pinfunction "2_2") (pintype "input"))
      (node (ref "C25") (pin "2") (pinfunction "2_2") (pintype "input"))
      (node (ref "R47") (pin "2") (pinfunction "2_2") (pintype "input"))
      (node (ref "R48") (pin "2") (pinfunction "2_2") (pintype "input"))
      (node (ref "R49") (pin "2") (pinfunction "2_2") (pintype "input"))
      (node (ref "U10") (pin "13") (pinfunction "VDD33_13") (pintype "input"))
      (node (ref "U10") (pin "21") (pinfunction "VDD33_21") (pintype "input"))
      (node (ref "U10") (pin "26") (pinfunction "OVCRN/SDA_26") (pintype "input"))
    )
    (net (code "60") (name "IN0") (class "Default")
      (node (ref "R120") (pin "1") (pinfunction "1_1") (pintype "input"))
      (node (ref "U45") (pin "54") (pinfunction "GPIO4_54") (pintype "bidirectional"))
      (node (ref "U6") (pin "4") (pinfunction "COL_4") (pintype "input"))
    )
    (net (code "61") (name "IN0+") (class "Default")
      (node (ref "CN10") (pin "12") (pinfunction "12_12") (pintype "input"))
      (node (ref "D37") (pin "2") (pinfunction "2_2") (pintype "input"))
      (node (ref "R105") (pin "2") (pinfunction "2_2") (pintype "input"))
      (node (ref "R106") (pin "2") (pinfunction "2_2") (pintype "input"))
    )
    (net (code "62") (name "IN0-") (class "Default")
      (node (ref "CN10") (pin "10") (pinfunction "10_10") (pintype "input"))
      (node (ref "D38") (pin "1") (pinfunction "1_1") (pintype "input"))
      (node (ref "R107") (pin "2") (pinfunction "2_2") (pintype "input"))
    )
    (net (code "63") (name "IN0-A") (class "Default")
      (node (ref "CN7") (pin "8") (pinfunction "8_8") (pintype "input"))
      (node (ref "R113") (pin "1") (pinfunction "1_1") (pintype "input"))
    )
    (net (code "64") (name "IN0-C") (class "Default")
      (node (ref "C47") (pin "2") (pinfunction "2_2") (pintype "input"))
      (node (ref "CN7") (pin "7") (pinfunction "7_7") (pintype "input"))
      (node (ref "R70") (pin "1") (pinfunction "1_1") (pintype "input"))
      (node (ref "U6") (pin "2") (pinfunction "CAT_2") (pintype "input"))
    )
    (net (code "65") (name "IN1") (class "Default")
      (node (ref "R119") (pin "1") (pinfunction "1_1") (pintype "input"))
      (node (ref "U15") (pin "4") (pinfunction "COL_4") (pintype "input"))
      (node (ref "U45") (pin "50") (pinfunction "GPIO17_50") (pintype "bidirectional"))
    )
    (net (code "66") (name "IN1+") (class "Default")
      (node (ref "CN10") (pin "9") (pinfunction "9_9") (pintype "input"))
      (node (ref "D31") (pin "2") (pinfunction "2_2") (pintype "input"))
      (node (ref "R98") (pin "2") (pinfunction "2_2") (pintype "input"))
      (node (ref "R99") (pin "2") (pinfunction "2_2") (pintype "input"))
    )
    (net (code "67") (name "IN1-") (class "Default")
      (node (ref "CN10") (pin "7") (pinfunction "7_7") (pintype "input"))
      (node (ref "D32") (pin "1") (pinfunction "1_1") (pintype "input"))
      (node (ref "R100") (pin "2") (pinfunction "2_2") (pintype "input"))
    )
    (net (code "68") (name "IN1-A") (class "Default")
      (node (ref "CN7") (pin "6") (pinfunction "6_6") (pintype "input"))
      (node (ref "R114") (pin "1") (pinfunction "1_1") (pintype "input"))
    )
    (net (code "69") (name "IN1-C") (class "Default")
      (node (ref "C48") (pin "2") (pinfunction "2_2") (pintype "input"))
      (node (ref "CN7") (pin "5") (pinfunction "5_5") (pintype "input"))
      (node (ref "R71") (pin "1") (pinfunction "1_1") (pintype "input"))
      (node (ref "U15") (pin "2") (pinfunction "CAT_2") (pintype "input"))
    )
    (net (code "70") (name "IN2") (class "Default")
      (node (ref "R118") (pin "1") (pinfunction "1_1") (pintype "input"))
      (node (ref "U16") (pin "4") (pinfunction "COL_4") (pintype "input"))
      (node (ref "U45") (pin "48") (pinfunction "GPIO27_48") (pintype "bidirectional"))
    )
    (net (code "71") (name "IN2+") (class "Default")
      (node (ref "CN10") (pin "6") (pinfunction "6_6") (pintype "input"))
      (node (ref "D5") (pin "2") (pinfunction "2_2") (pintype "input"))
      (node (ref "R35") (pin "2") (pinfunction "2_2") (pintype "input"))
      (node (ref "R85") (pin "2") (pinfunction "2_2") (pintype "input"))
    )
    (net (code "72") (name "IN2-") (class "Default")
      (node (ref "CN10") (pin "4") (pinfunction "4_4") (pintype "input"))
      (node (ref "D6") (pin "1") (pinfunction "1_1") (pintype "input"))
      (node (ref "R86") (pin "2") (pinfunction "2_2") (pintype "input"))
    )
    (net (code "73") (name "IN2-A") (class "Default")
      (node (ref "CN7") (pin "4") (pinfunction "4_4") (pintype "input"))
      (node (ref "R115") (pin "1") (pinfunction "1_1") (pintype "input"))
    )
    (net (code "74") (name "IN2-C") (class "Default")
      (node (ref "C49") (pin "2") (pinfunction "2_2") (pintype "input"))
      (node (ref "CN7") (pin "3") (pinfunction "3_3") (pintype "input"))
      (node (ref "R72") (pin "1") (pinfunction "1_1") (pintype "input"))
      (node (ref "U16") (pin "2") (pinfunction "CAT_2") (pintype "input"))
    )
    (net (code "75") (name "IN3") (class "Default")
      (node (ref "R117") (pin "1") (pinfunction "1_1") (pintype "input"))
      (node (ref "U17") (pin "4") (pinfunction "COL_4") (pintype "input"))
      (node (ref "U45") (pin "44") (pinfunction "GPIO10_44") (pintype "bidirectional"))
    )
    (net (code "76") (name "IN3-A") (class "Default")
      (node (ref "CN7") (pin "2") (pinfunction "2_2") (pintype "input"))
      (node (ref "R116") (pin "1") (pinfunction "1_1") (pintype "input"))
    )
    (net (code "77") (name "IN3-C") (class "Default")
      (node (ref "C50") (pin "2") (pinfunction "2_2") (pintype "input"))
      (node (ref "CN7") (pin "1") (pinfunction "1_1") (pintype "input"))
      (node (ref "R73") (pin "1") (pinfunction "1_1") (pintype "input"))
      (node (ref "U17") (pin "2") (pinfunction "CAT_2") (pintype "input"))
    )
    (net (code "78") (name "LED_STATUS") (class "Default")
      (node (ref "R172") (pin "1") (pinfunction "1_1") (pintype "input"))
      (node (ref "U45") (pin "24") (pinfunction "GPIO26_24") (pintype "bidirectional"))
    )
    (net (code "79") (name "NRPIBOOT") (class "Default")
      (node (ref "SW1") (pin "2") (pinfunction "2_2") (pintype "input"))
      (node (ref "SW1") (pin "5") (pinfunction "5_5") (pintype "input"))
      (node (ref "U45") (pin "93") (pinfunction "nRPIBOOT_93") (pintype "bidirectional"))
    )
    (net (code "80") (name "Net-(C5-Pad2)") (class "Default")
      (node (ref "C5") (pin "2") (pinfunction "2_2") (pintype "input"))
      (node (ref "R4") (pin "2") (pinfunction "2_2") (pintype "input"))
    )
    (net (code "81") (name "Net-(C14-Pad2)") (class "Default")
      (node (ref "C14") (pin "2") (pinfunction "2_2") (pintype "input"))
      (node (ref "R17") (pin "2") (pinfunction "2_2") (pintype "input"))
    )
    (net (code "82") (name "Net-(C35-Pad2)") (class "Default")
      (node (ref "C35") (pin "2") (pinfunction "2_2") (pintype "input"))
      (node (ref "R54") (pin "2") (pinfunction "2_2") (pintype "input"))
    )
    (net (code "83") (name "Net-(C64-Pad2)") (class "Default")
      (node (ref "C64") (pin "2") (pinfunction "2_2") (pintype "input"))
      (node (ref "RJ2") (pin "P1") (pinfunction "P1_P1") (pintype "input"))
    )
    (net (code "84") (name "Net-(CARD2-CLK)") (class "Default")
      (node (ref "C100") (pin "2") (pinfunction "2_2") (pintype "input"))
      (node (ref "CARD2") (pin "C3") (pinfunction "CLK_C3") (pintype "input"))
      (node (ref "R167") (pin "1") (pinfunction "1_1") (pintype "input"))
      (node (ref "U33") (pin "5") (pinfunction "5_5") (pintype "input"))
      (node (ref "U33") (pin "6") (pinfunction "6_6") (pintype "input"))
    )
    (net (code "85") (name "Net-(CARD2-I{slash}O)") (class "Default")
      (node (ref "C101") (pin "2") (pinfunction "2_2") (pintype "input"))
      (node (ref "CARD2") (pin "C7") (pinfunction "I/O_C7") (pintype "input"))
      (node (ref "R168") (pin "1") (pinfunction "1_1") (pintype "input"))
      (node (ref "R8") (pin "1") (pinfunction "1_1") (pintype "input"))
      (node (ref "U33") (pin "4") (pinfunction "4_4") (pintype "input"))
      (node (ref "U33") (pin "7") (pinfunction "7_7") (pintype "input"))
    )
    (net (code "86") (name "Net-(CARD2-RST)") (class "Default")
      (node (ref "C102") (pin "2") (pinfunction "2_2") (pintype "input"))
      (node (ref "CARD2") (pin "C2") (pinfunction "RST_C2") (pintype "input"))
      (node (ref "R169") (pin "1") (pinfunction "1_1") (pintype "input"))
      (node (ref "U33") (pin "2") (pinfunction "2_2") (pintype "input"))
      (node (ref "U33") (pin "9") (pinfunction "9_9") (pintype "input"))
    )
    (net (code "87") (name "Net-(CN3-Pad7)") (class "Default")
      (node (ref "CN3") (pin "7") (pinfunction "7_7") (pintype "input"))
      (node (ref "R170") (pin "2") (pinfunction "2_2") (pintype "input"))
    )
    (net (code "88") (name "Net-(CN3-Pad9)") (class "Default")
      (node (ref "CN3") (pin "9") (pinfunction "9_9") (pintype "input"))
      (node (ref "R171") (pin "2") (pinfunction "2_2") (pintype "input"))
    )
    (net (code "89") (name "Net-(CN20-+5V)") (class "Default")
      (node (ref "C86") (pin "2") (pinfunction "2_2") (pintype "input"))
      (node (ref "CN20") (pin "19") (pinfunction "+5V_19") (pintype "unspecified"))
      (node (ref "U41") (pin "1") (pinfunction "VOUT_1") (pintype "input"))
      (node (ref "USB16") (pin "18") (pinfunction "+5VPower_18") (pintype "input"))
    )
    (net (code "90") (name "Net-(D1-Pad2)") (class "Default")
      (node (ref "D1") (pin "2") (pinfunction "2_2") (pintype "input"))
      (node (ref "D2") (pin "1") (pinfunction "1_1") (pintype "input"))
      (node (ref "R86") (pin "1") (pinfunction "1_1") (pintype "input"))
      (node (ref "R87") (pin "1") (pinfunction "1_1") (pintype "input"))
    )
    (net (code "91") (name "Net-(D3-Pad1)") (class "Default")
      (node (ref "D3") (pin "1") (pinfunction "1_1") (pintype "input"))
      (node (ref "D4") (pin "2") (pinfunction "2_2") (pintype "input"))
      (node (ref "R85") (pin "1") (pinfunction "1_1") (pintype "input"))
      (node (ref "R88") (pin "1") (pinfunction "1_1") (pintype "input"))
    )
    (net (code "92") (name "Net-(D27-Pad2)") (class "Default")
      (node (ref "D27") (pin "2") (pinfunction "2_2") (pintype "input"))
      (node (ref "D28") (pin "1") (pinfunction "1_1") (pintype "input"))
      (node (ref "R100") (pin "1") (pinfunction "1_1") (pintype "input"))
      (node (ref "R101") (pin "1") (pinfunction "1_1") (pintype "input"))
    )
    (net (code "93") (name "Net-(D29-Pad1)") (class "Default")
      (node (ref "D29") (pin "1") (pinfunction "1_1") (pintype "input"))
      (node (ref "D30") (pin "2") (pinfunction "2_2") (pintype "input"))
      (node (ref "R102") (pin "1") (pinfunction "1_1") (pintype "input"))
      (node (ref "R99") (pin "1") (pinfunction "1_1") (pintype "input"))
    )
    (net (code "94") (name "Net-(D33-Pad2)") (class "Default")
      (node (ref "D33") (pin "2") (pinfunction "2_2") (pintype "input"))
      (node (ref "D34") (pin "1") (pinfunction "1_1") (pintype "input"))
      (node (ref "R107") (pin "1") (pinfunction "1_1") (pintype "input"))
      (node (ref "R108") (pin "1") (pinfunction "1_1") (pintype "input"))
    )
    (net (code "95") (name "Net-(D35-Pad1)") (class "Default")
      (node (ref "D35") (pin "1") (pinfunction "1_1") (pintype "input"))
      (node (ref "D36") (pin "2") (pinfunction "2_2") (pintype "input"))
      (node (ref "R106") (pin "1") (pinfunction "1_1") (pintype "input"))
      (node (ref "R109") (pin "1") (pinfunction "1_1") (pintype "input"))
    )
    (net (code "96") (name "Net-(D40-A)") (class "Default")
      (node (ref "C66") (pin "1") (pinfunction "1_1") (pintype "input"))
      (node (ref "D40") (pin "2") (pinfunction "A_2") (pintype "input"))
      (node (ref "R124") (pin "2") (pinfunction "2_2") (pintype "input"))
      (node (ref "U24") (pin "13") (pinfunction "6A_13") (pintype "input"))
    )
    (net (code "97") (name "Net-(D40-K)") (class "Default")
      (node (ref "D40") (pin "1") (pinfunction "K_1") (pintype "input"))
      (node (ref "R124") (pin "1") (pinfunction "1_1") (pintype "input"))
      (node (ref "U23") (pin "4") (pinfunction "DI_4") (pintype "input"))
      (node (ref "U24") (pin "10") (pinfunction "5Y_10") (pintype "input"))
    )
    (net (code "98") (name "Net-(D44-A)") (class "Default")
      (node (ref "D44") (pin "1") (pinfunction "A_1") (pintype "input"))
      (node (ref "Q2") (pin "1") (pinfunction "G_1") (pintype "input"))
      (node (ref "R80") (pin "2") (pinfunction "2_2") (pintype "input"))
    )
    (net (code "99") (name "Net-(LED2-A)") (class "Default")
      (node (ref "LED2") (pin "2") (pinfunction "A_2") (pintype "input"))
      (node (ref "R10") (pin "2") (pinfunction "2_2") (pintype "input"))
    )
    (net (code "100") (name "Net-(LED2-C)") (class "Default")
      (node (ref "CN3") (pin "10") (pinfunction "10_10") (pintype "input"))
      (node (ref "LED2") (pin "1") (pinfunction "C_1") (pintype "input"))
    )
    (net (code "101") (name "Net-(LED6-A)") (class "Default")
      (node (ref "LED6") (pin "2") (pinfunction "A_2") (pintype "input"))
      (node (ref "R59") (pin "1") (pinfunction "1_1") (pintype "input"))
    )
    (net (code "102") (name "Net-(LED7-C)") (class "Default")
      (node (ref "LED7") (pin "1") (pinfunction "C_1") (pintype "input"))
      (node (ref "R57") (pin "2") (pinfunction "2_2") (pintype "input"))
    )
    (net (code "103") (name "Net-(LED8-C)") (class "Default")
      (node (ref "LED8") (pin "1") (pinfunction "C_1") (pintype "input"))
      (node (ref "R7") (pin "2") (pinfunction "2_2") (pintype "input"))
    )
    (net (code "104") (name "Net-(LED9-+)") (class "Default")
      (node (ref "LED9") (pin "1") (pinfunction "+_1") (pintype "input"))
      (node (ref "R13") (pin "2") (pinfunction "2_2") (pintype "input"))
    )
    (net (code "105") (name "Net-(LED9--)") (class "Default")
      (node (ref "CN5") (pin "10") (pinfunction "10_10") (pintype "input"))
      (node (ref "LED9") (pin "2") (pinfunction "-_2") (pintype "input"))
    )
    (net (code "106") (name "Net-(LED10-C)") (class "Default")
      (node (ref "LED10") (pin "1") (pinfunction "C_1") (pintype "input"))
      (node (ref "R20") (pin "2") (pinfunction "2_2") (pintype "input"))
    )
    (net (code "107") (name "Net-(LED11-A)") (class "Default")
      (node (ref "LED11") (pin "2") (pinfunction "A_2") (pintype "input"))
      (node (ref "U24") (pin "6") (pinfunction "3Y_6") (pintype "input"))
    )
    (net (code "108") (name "Net-(LED11-C)") (class "Default")
      (node (ref "LED11") (pin "1") (pinfunction "C_1") (pintype "input"))
      (node (ref "R122") (pin "2") (pinfunction "2_2") (pintype "input"))
    )
    (net (code "109") (name "Net-(LED12-A)") (class "Default")
      (node (ref "LED12") (pin "2") (pinfunction "A_2") (pintype "input"))
      (node (ref "U24") (pin "11") (pinfunction "5A_11") (pintype "input"))
      (node (ref "U24") (pin "8") (pinfunction "4Y_8") (pintype "input"))
    )
    (net (code "110") (name "Net-(LED12-C)") (class "Default")
      (node (ref "LED12") (pin "1") (pinfunction "C_1") (pintype "input"))
      (node (ref "R125") (pin "2") (pinfunction "2_2") (pintype "input"))
    )
    (net (code "111") (name "Net-(LED13-C)") (class "Default")
      (node (ref "LED13") (pin "1") (pinfunction "C_1") (pintype "input"))
      (node (ref "R126") (pin "2") (pinfunction "2_2") (pintype "input"))
    )
    (net (code "112") (name "Net-(LED14-C)") (class "Default")
      (node (ref "LED14") (pin "1") (pinfunction "C_1") (pintype "input"))
      (node (ref "R172") (pin "2") (pinfunction "2_2") (pintype "input"))
    )
    (net (code "113") (name "Net-(Q2-D)") (class "Default")
      (node (ref "D19") (pin "2") (pinfunction "2_2") (pintype "input"))
      (node (ref "F1") (pin "2") (pinfunction "2_2") (pintype "input"))
      (node (ref "Q2") (pin "3") (pinfunction "D_3") (pintype "input"))
    )
    (net (code "114") (name "Net-(Q7-D)") (class "Default")
      (node (ref "CN3") (pin "67") (pinfunction "67_67") (pintype "input"))
      (node (ref "Q7") (pin "3") (pinfunction "D_3") (pintype "input"))
      (node (ref "R165") (pin "1") (pinfunction "1_1") (pintype "input"))
    )
    (net (code "115") (name "Net-(R46-Pad2)") (class "Default")
      (node (ref "R46") (pin "2") (pinfunction "2_2") (pintype "input"))
      (node (ref "U10") (pin "14") (pinfunction "NC_14") (pintype "input"))
    )
    (net (code "116") (name "Net-(R48-Pad1)") (class "Default")
      (node (ref "R48") (pin "1") (pinfunction "1_1") (pintype "input"))
      (node (ref "U10") (pin "18") (pinfunction "NC_18") (pintype "input"))
    )
    (net (code "117") (name "Net-(R74-Pad1)") (class "Default")
      (node (ref "R74") (pin "1") (pinfunction "1_1") (pintype "input"))
      (node (ref "RJ2") (pin "12") (pinfunction "12_12") (pintype "input"))
    )
    (net (code "118") (name "Net-(R75-Pad1)") (class "Default")
      (node (ref "R75") (pin "1") (pinfunction "1_1") (pintype "input"))
      (node (ref "RJ2") (pin "13") (pinfunction "13_13") (pintype "input"))
    )
    (net (code "119") (name "Net-(U3-BOOT)") (class "Default")
      (node (ref "C46") (pin "1") (pinfunction "1_1") (pintype "input"))
      (node (ref "U3") (pin "2") (pinfunction "BOOT_2") (pintype "input"))
    )
    (net (code "120") (name "Net-(U3-COMP)") (class "Default")
      (node (ref "C5") (pin "1") (pinfunction "1_1") (pintype "input"))
      (node (ref "U3") (pin "6") (pinfunction "COMP_6") (pintype "input"))
    )
    (net (code "121") (name "Net-(U3-FB)") (class "Default")
      (node (ref "R5") (pin "1") (pinfunction "1_1") (pintype "input"))
      (node (ref "R6") (pin "2") (pinfunction "2_2") (pintype "input"))
      (node (ref "U3") (pin "5") (pinfunction "FB_5") (pintype "input"))
    )
    (net (code "122") (name "Net-(U3-RLIM)") (class "Default")
      (node (ref "R82") (pin "2") (pinfunction "2_2") (pintype "input"))
      (node (ref "U3") (pin "7") (pinfunction "RLIM_7") (pintype "input"))
    )
    (net (code "123") (name "Net-(U3-SW)") (class "Default")
      (node (ref "C46") (pin "2") (pinfunction "2_2") (pintype "input"))
      (node (ref "L1") (pin "1") (pinfunction "1_1") (pintype "input"))
      (node (ref "U3") (pin "1") (pinfunction "SW_1") (pintype "input"))
    )
    (net (code "124") (name "Net-(U4-BOOT)") (class "Default")
      (node (ref "C13") (pin "2") (pinfunction "2_2") (pintype "input"))
      (node (ref "U4") (pin "2") (pinfunction "BOOT_2") (pintype "input"))
    )
    (net (code "125") (name "Net-(U4-COMP)") (class "Default")
      (node (ref "C14") (pin "1") (pinfunction "1_1") (pintype "input"))
      (node (ref "U4") (pin "6") (pinfunction "COMP_6") (pintype "input"))
    )
    (net (code "126") (name "Net-(U4-EN)") (class "Default")
      (node (ref "R83") (pin "2") (pinfunction "2_2") (pintype "input"))
      (node (ref "U4") (pin "3") (pinfunction "EN_3") (pintype "input"))
    )
    (net (code "127") (name "Net-(U4-FB)") (class "Default")
      (node (ref "R18") (pin "1") (pinfunction "1_1") (pintype "input"))
      (node (ref "R19") (pin "2") (pinfunction "2_2") (pintype "input"))
      (node (ref "U4") (pin "5") (pinfunction "FB_5") (pintype "input"))
    )
    (net (code "128") (name "Net-(U4-RLIM)") (class "Default")
      (node (ref "R84") (pin "2") (pinfunction "2_2") (pintype "input"))
      (node (ref "U4") (pin "7") (pinfunction "RLIM_7") (pintype "input"))
    )
    (net (code "129") (name "Net-(U4-SW)") (class "Default")
      (node (ref "C13") (pin "1") (pinfunction "1_1") (pintype "input"))
      (node (ref "L3") (pin "1") (pinfunction "1_1") (pintype "input"))
      (node (ref "U4") (pin "1") (pinfunction "SW_1") (pintype "input"))
    )
    (net (code "130") (name "Net-(U6-AN)") (class "Default")
      (node (ref "C47") (pin "1") (pinfunction "1_1") (pintype "input"))
      (node (ref "R113") (pin "2") (pinfunction "2_2") (pintype "input"))
      (node (ref "R70") (pin "2") (pinfunction "2_2") (pintype "input"))
      (node (ref "U6") (pin "1") (pinfunction "AN_1") (pintype "input"))
    )
    (net (code "131") (name "Net-(U10-PSELF)") (class "Default")
      (node (ref "R49") (pin "1") (pinfunction "1_1") (pintype "input"))
      (node (ref "U10") (pin "19") (pinfunction "PSELF_19") (pintype "input"))
    )
    (net (code "132") (name "Net-(U10-RESET_N)") (class "Default")
      (node (ref "R47") (pin "1") (pinfunction "1_1") (pintype "input"))
      (node (ref "U10") (pin "17") (pinfunction "RESET_N_17") (pintype "input"))
    )
    (net (code "133") (name "Net-(U14-BOOT)") (class "Default")
      (node (ref "C41") (pin "1") (pinfunction "1_1") (pintype "input"))
      (node (ref "U14") (pin "2") (pinfunction "BOOT_2") (pintype "input"))
    )
    (net (code "134") (name "Net-(U14-COMP)") (class "Default")
      (node (ref "C35") (pin "1") (pinfunction "1_1") (pintype "input"))
      (node (ref "U14") (pin "6") (pinfunction "COMP_6") (pintype "input"))
    )
    (net (code "135") (name "Net-(U14-EN)") (class "Default")
      (node (ref "R78") (pin "2") (pinfunction "2_2") (pintype "input"))
      (node (ref "U14") (pin "3") (pinfunction "EN_3") (pintype "input"))
    )
    (net (code "136") (name "Net-(U14-FB)") (class "Default")
      (node (ref "R56") (pin "2") (pinfunction "2_2") (pintype "input"))
      (node (ref "R60") (pin "1") (pinfunction "1_1") (pintype "input"))
      (node (ref "U14") (pin "5") (pinfunction "FB_5") (pintype "input"))
    )
    (net (code "137") (name "Net-(U14-RLIM)") (class "Default")
      (node (ref "R79") (pin "2") (pinfunction "2_2") (pintype "input"))
      (node (ref "U14") (pin "7") (pinfunction "RLIM_7") (pintype "input"))
    )
    (net (code "138") (name "Net-(U14-SW)") (class "Default")
      (node (ref "C41") (pin "2") (pinfunction "2_2") (pintype "input"))
      (node (ref "L4") (pin "1") (pinfunction "1_1") (pintype "input"))
      (node (ref "U14") (pin "1") (pinfunction "SW_1") (pintype "input"))
    )
    (net (code "139") (name "Net-(U15-AN)") (class "Default")
      (node (ref "C48") (pin "1") (pinfunction "1_1") (pintype "input"))
      (node (ref "R114") (pin "2") (pinfunction "2_2") (pintype "input"))
      (node (ref "R71") (pin "2") (pinfunction "2_2") (pintype "input"))
      (node (ref "U15") (pin "1") (pinfunction "AN_1") (pintype "input"))
    )
    (net (code "140") (name "Net-(U16-AN)") (class "Default")
      (node (ref "C49") (pin "1") (pinfunction "1_1") (pintype "input"))
      (node (ref "R115") (pin "2") (pinfunction "2_2") (pintype "input"))
      (node (ref "R72") (pin "2") (pinfunction "2_2") (pintype "input"))
      (node (ref "U16") (pin "1") (pinfunction "AN_1") (pintype "input"))
    )
    (net (code "141") (name "Net-(U17-AN)") (class "Default")
      (node (ref "C50") (pin "1") (pinfunction "1_1") (pintype "input"))
      (node (ref "R116") (pin "2") (pinfunction "2_2") (pintype "input"))
      (node (ref "R73") (pin "2") (pinfunction "2_2") (pintype "input"))
      (node (ref "U17") (pin "1") (pinfunction "AN_1") (pintype "input"))
    )
    (net (code "142") (name "Net-(U19-VBAT)") (class "Default")
      (node (ref "B1") (pin "1") (pinfunction "1_1") (pintype "input"))
      (node (ref "U19") (pin "3") (pinfunction "VBAT_3") (pintype "input"))
    )
    (net (code "143") (name "Net-(U19-X1)") (class "Default")
      (node (ref "U19") (pin "1") (pinfunction "X1_1") (pintype "input"))
      (node (ref "X2") (pin "2") (pinfunction "2_2") (pintype "input"))
    )
    (net (code "144") (name "Net-(U19-X2)") (class "Default")
      (node (ref "U19") (pin "2") (pinfunction "X2_2") (pintype "input"))
      (node (ref "X2") (pin "1") (pinfunction "1_1") (pintype "input"))
    )
    (net (code "145") (name "Net-(U22B-IN2+)") (class "Default")
      (node (ref "C53") (pin "2") (pinfunction "2_2") (pintype "input"))
      (node (ref "R88") (pin "2") (pinfunction "2_2") (pintype "input"))
      (node (ref "R90") (pin "2") (pinfunction "2_2") (pintype "input"))
      (node (ref "U22") (pin "5") (pinfunction "IN2+_5") (pintype "input"))
    )
    (net (code "146") (name "Net-(U22B-IN2-)") (class "Default")
      (node (ref "C54") (pin "2") (pinfunction "2_2") (pintype "input"))
      (node (ref "R87") (pin "2") (pinfunction "2_2") (pintype "input"))
      (node (ref "R89") (pin "1") (pinfunction "1_1") (pintype "input"))
      (node (ref "U22") (pin "6") (pinfunction "IN2-_6") (pintype "input"))
    )
    (net (code "147") (name "Net-(U22C-IN3+)") (class "Default")
      (node (ref "C57") (pin "2") (pinfunction "2_2") (pintype "input"))
      (node (ref "R102") (pin "2") (pinfunction "2_2") (pintype "input"))
      (node (ref "R104") (pin "2") (pinfunction "2_2") (pintype "input"))
      (node (ref "U22") (pin "10") (pinfunction "IN3+_10") (pintype "input"))
    )
    (net (code "148") (name "Net-(U22C-IN3-)") (class "Default")
      (node (ref "C58") (pin "2") (pinfunction "2_2") (pintype "input"))
      (node (ref "R101") (pin "2") (pinfunction "2_2") (pintype "input"))
      (node (ref "R103") (pin "1") (pinfunction "1_1") (pintype "input"))
      (node (ref "U22") (pin "9") (pinfunction "IN3-_9") (pintype "input"))
    )
    (net (code "149") (name "Net-(U22D-IN4+)") (class "Default")
      (node (ref "C59") (pin "2") (pinfunction "2_2") (pintype "input"))
      (node (ref "R109") (pin "2") (pinfunction "2_2") (pintype "input"))
      (node (ref "R111") (pin "2") (pinfunction "2_2") (pintype "input"))
      (node (ref "U22") (pin "12") (pinfunction "IN4+_12") (pintype "input"))
    )
    (net (code "150") (name "Net-(U22D-IN4-)") (class "Default")
      (node (ref "C60") (pin "2") (pinfunction "2_2") (pintype "input"))
      (node (ref "R108") (pin "2") (pinfunction "2_2") (pintype "input"))
      (node (ref "R110") (pin "1") (pinfunction "1_1") (pintype "input"))
      (node (ref "U22") (pin "13") (pinfunction "IN4-_13") (pintype "input"))
    )
    (net (code "151") (name "Net-(U23-DE)") (class "Default")
      (node (ref "U23") (pin "2") (pinfunction "RE#_2") (pintype "input"))
      (node (ref "U23") (pin "3") (pinfunction "DE_3") (pintype "input"))
      (node (ref "U24") (pin "12") (pinfunction "6Y_12") (pintype "input"))
    )
    (net (code "152") (name "Net-(U23-RO)") (class "Default")
      (node (ref "R121") (pin "1") (pinfunction "1_1") (pintype "input"))
      (node (ref "U23") (pin "1") (pinfunction "RO_1") (pintype "input"))
      (node (ref "U24") (pin "1") (pinfunction "1A_1") (pintype "input"))
    )
    (net (code "153") (name "Net-(U24-1Y)") (class "Default")
      (node (ref "U24") (pin "2") (pinfunction "1Y_2") (pintype "input"))
      (node (ref "U24") (pin "3") (pinfunction "2A_3") (pintype "input"))
    )
    (net (code "154") (name "Net-(U25-EN)") (class "Default")
      (node (ref "R130") (pin "2") (pinfunction "2_2") (pintype "input"))
      (node (ref "U25") (pin "4") (pinfunction "EN_4") (pintype "input"))
    )
    (net (code "155") (name "Net-(U25-SET)") (class "Default")
      (node (ref "R129") (pin "2") (pinfunction "2_2") (pintype "input"))
      (node (ref "U25") (pin "3") (pinfunction "SET_3") (pintype "input"))
    )
    (net (code "156") (name "Net-(U25-VOUT)") (class "Default")
      (node (ref "C71") (pin "2") (pinfunction "2_2") (pintype "input"))
      (node (ref "U25") (pin "1") (pinfunction "VOUT_1") (pintype "input"))
      (node (ref "USB7") (pin "1") (pinfunction "VCC_1") (pintype "input"))
      (node (ref "USB7") (pin "5") (pinfunction "VCC_5") (pintype "input"))
    )
    (net (code "157") (name "Net-(U41-EN)") (class "Default")
      (node (ref "R162") (pin "2") (pinfunction "2_2") (pintype "input"))
      (node (ref "U41") (pin "4") (pinfunction "EN_4") (pintype "input"))
    )
    (net (code "158") (name "Net-(U41-SET)") (class "Default")
      (node (ref "R163") (pin "2") (pinfunction "2_2") (pintype "input"))
      (node (ref "U41") (pin "3") (pinfunction "SET_3") (pintype "input"))
    )
    (net (code "159") (name "Net-(USB8-VBUS)") (class "Default")
      (node (ref "R127") (pin "2") (pinfunction "2_2") (pintype "input"))
      (node (ref "USB8") (pin "1") (pinfunction "VBUS_1") (pintype "input"))
    )
    (net (code "160") (name "OLED-SCL") (class "Default")
      (node (ref "CN17") (pin "3") (pinfunction "3_3") (pintype "input"))
      (node (ref "R178") (pin "1") (pinfunction "1_1") (pintype "input"))
      (node (ref "U45") (pin "47") (pinfunction "GPIO23_47") (pintype "bidirectional"))
    )
    (net (code "161") (name "OLED-SDA") (class "Default")
      (node (ref "CN17") (pin "4") (pinfunction "4_4") (pintype "input"))
      (node (ref "R179") (pin "1") (pinfunction "1_1") (pintype "input"))
      (node (ref "U45") (pin "46") (pinfunction "GPIO22_46") (pintype "bidirectional"))
    )
    (net (code "162") (name "OLED-SW") (class "Default")
      (node (ref "CN17") (pin "5") (pinfunction "5_5") (pintype "input"))
      (node (ref "R173") (pin "1") (pinfunction "1_1") (pintype "input"))
      (node (ref "U45") (pin "55") (pinfunction "GPIO14_55") (pintype "bidirectional"))
    )
    (net (code "163") (name "PCIE_CLK_REQ") (class "Default")
      (node (ref "CN5") (pin "52") (pinfunction "52_52") (pintype "input"))
      (node (ref "U46") (pin "102") (pinfunction "PCIe_CLK_nREQ_102") (pintype "bidirectional"))
    )
    (net (code "164") (name "PCIE_CLP_N") (class "Default")
      (node (ref "CN5") (pin "53") (pinfunction "53_53") (pintype "input"))
      (node (ref "U46") (pin "112") (pinfunction "PCIe_CLK_N_112") (pintype "bidirectional"))
    )
    (net (code "165") (name "PCIE_CLP_P") (class "Default")
      (node (ref "CN5") (pin "55") (pinfunction "55_55") (pintype "input"))
      (node (ref "U46") (pin "110") (pinfunction "PCIe_CLK_P_110") (pintype "bidirectional"))
    )
    (net (code "166") (name "PCIE_R0_N") (class "Default")
      (node (ref "CN5") (pin "41") (pinfunction "41_41") (pintype "input"))
      (node (ref "U46") (pin "118") (pinfunction "PCIE_RX_N_118") (pintype "bidirectional"))
    )
    (net (code "167") (name "PCIE_R0_P") (class "Default")
      (node (ref "CN5") (pin "43") (pinfunction "43_43") (pintype "input"))
      (node (ref "U46") (pin "116") (pinfunction "PCIe_RX_P_116") (pintype "bidirectional"))
    )
    (net (code "168") (name "PCIE_RST") (class "Default")
      (node (ref "CN5") (pin "50") (pinfunction "50_50") (pintype "input"))
      (node (ref "U46") (pin "109") (pinfunction "PCIe_nRST_109") (pintype "bidirectional"))
    )
    (net (code "169") (name "PCIE_T0_N") (class "Default")
      (node (ref "CN5") (pin "47") (pinfunction "47_47") (pintype "input"))
      (node (ref "U46") (pin "124") (pinfunction "PCIe_TX_N_124") (pintype "bidirectional"))
    )
    (net (code "170") (name "PCIE_T0_P") (class "Default")
      (node (ref "CN5") (pin "49") (pinfunction "49_49") (pintype "input"))
      (node (ref "U46") (pin "122") (pinfunction "PCIe_TX_P_122") (pintype "bidirectional"))
    )
    (net (code "171") (name "Pi_nLED_Activity") (class "Default")
      (node (ref "R126") (pin "1") (pinfunction "1_1") (pintype "input"))
      (node (ref "U45") (pin "21") (pinfunction "Pi_nLED_Activity_21") (pintype "bidirectional"))
    )
    (net (code "172") (name "RS485-DI") (class "Default")
      (node (ref "R123") (pin "1") (pinfunction "1_1") (pintype "input"))
      (node (ref "U24") (pin "9") (pinfunction "4A_9") (pintype "input"))
      (node (ref "U45") (pin "39") (pinfunction "GPIO8_39") (pintype "bidirectional"))
    )
    (net (code "173") (name "RS485-RO") (class "Default")
      (node (ref "U24") (pin "4") (pinfunction "2Y_4") (pintype "input"))
      (node (ref "U24") (pin "5") (pinfunction "3A_5") (pintype "input"))
      (node (ref "U45") (pin "40") (pinfunction "GPIO9_40") (pintype "bidirectional"))
    )
    (net (code "174") (name "RTC-SCL") (class "Default")
      (node (ref "U19") (pin "6") (pinfunction "SCL_6") (pintype "input"))
      (node (ref "U45") (pin "56") (pinfunction "GPIO3_56") (pintype "bidirectional"))
    )
    (net (code "175") (name "RTC-SDA") (class "Default")
      (node (ref "U19") (pin "5") (pinfunction "SDA_5") (pintype "input"))
      (node (ref "U45") (pin "58") (pinfunction "GPIO2_58") (pintype "bidirectional"))
    )
    (net (code "176") (name "SCL0") (class "Default")
      (node (ref "FPC8") (pin "3") (pinfunction "3_3") (pintype "input"))
      (node (ref "U45") (pin "80") (pinfunction "SCL0_80") (pintype "bidirectional"))
    )
    (net (code "177") (name "SDA0") (class "Default")
      (node (ref "FPC8") (pin "2") (pinfunction "2_2") (pintype "input"))
      (node (ref "U45") (pin "82") (pinfunction "SDA0_82") (pintype "bidirectional"))
    )
    (net (code "178") (name "SD_CLK") (class "Default")
      (node (ref "CARD1") (pin "5") (pinfunction "CLX_5") (pintype "input"))
      (node (ref "U45") (pin "57") (pinfunction "SD_CLK_57") (pintype "bidirectional"))
    )
    (net (code "179") (name "SD_CMD") (class "Default")
      (node (ref "CARD1") (pin "3") (pinfunction "CMD_3") (pintype "input"))
      (node (ref "U45") (pin "62") (pinfunction "SD_CMD_62") (pintype "bidirectional"))
    )
    (net (code "180") (name "SD_DAT0") (class "Default")
      (node (ref "CARD1") (pin "7") (pinfunction "DAT0_7") (pintype "input"))
      (node (ref "U45") (pin "63") (pinfunction "SD_DAT0_63") (pintype "bidirectional"))
    )
    (net (code "181") (name "SD_DAT1") (class "Default")
      (node (ref "CARD1") (pin "8") (pinfunction "DAT1_8") (pintype "input"))
      (node (ref "U45") (pin "67") (pinfunction "SD_DAT1_67") (pintype "bidirectional"))
    )
    (net (code "182") (name "SD_DAT2") (class "Default")
      (node (ref "CARD1") (pin "1") (pinfunction "DAT2_1") (pintype "input"))
      (node (ref "U45") (pin "69") (pinfunction "SD_DAT2_69") (pintype "bidirectional"))
    )
    (net (code "183") (name "SD_DAT3") (class "Default")
      (node (ref "CARD1") (pin "2") (pinfunction "CD/DAT3_2") (pintype "input"))
      (node (ref "U45") (pin "61") (pinfunction "SD_DAT3_61") (pintype "bidirectional"))
    )
    (net (code "184") (name "SD_PWR_ON") (class "Default")
      (node (ref "U45") (pin "75") (pinfunction "SD_PWR_ON_75") (pintype "bidirectional"))
    )
    (net (code "185") (name "SIM_CLK") (class "Default")
      (node (ref "CN3") (pin "32") (pinfunction "32_32") (pintype "input"))
      (node (ref "R167") (pin "2") (pinfunction "2_2") (pintype "input"))
    )
    (net (code "186") (name "SIM_DAT") (class "Default")
      (node (ref "CN3") (pin "34") (pinfunction "34_34") (pintype "input"))
      (node (ref "R168") (pin "2") (pinfunction "2_2") (pintype "input"))
    )
    (net (code "187") (name "SIM_RST") (class "Default")
      (node (ref "CN3") (pin "30") (pinfunction "30_30") (pintype "input"))
      (node (ref "R169") (pin "2") (pinfunction "2_2") (pintype "input"))
    )
    (net (code "188") (name "SIM_VDD") (class "Default")
      (node (ref "C45") (pin "2") (pinfunction "2_2") (pintype "input"))
      (node (ref "C97") (pin "2") (pinfunction "2_2") (pintype "input"))
      (node (ref "CARD2") (pin "C1") (pinfunction "VCC_C1") (pintype "input"))
      (node (ref "CN3") (pin "36") (pinfunction "36_36") (pintype "input"))
      (node (ref "R8") (pin "2") (pinfunction "2_2") (pintype "input"))
      (node (ref "U33") (pin "1") (pinfunction "1_1") (pintype "input"))
      (node (ref "U33") (pin "10") (pinfunction "10_10") (pintype "input"))
    )
    (net (code "189") (name "U2_N") (class "Default")
      (node (ref "U28") (pin "6") (pinfunction "HSD1-_6") (pintype "input"))
      (node (ref "USB8") (pin "2") (pinfunction "D-_2") (pintype "input"))
    )
    (net (code "190") (name "U2_P") (class "Default")
      (node (ref "U28") (pin "7") (pinfunction "HSD1+_7") (pintype "input"))
      (node (ref "USB8") (pin "3") (pinfunction "D+_3") (pintype "input"))
    )
    (net (code "191") (name "USB1_N") (class "Default")
      (node (ref "U10") (pin "10") (pinfunction "DM1_10") (pintype "input"))
      (node (ref "U31") (pin "2") (pinfunction "2_2") (pintype "input"))
      (node (ref "U31") (pin "9") (pinfunction "9_9") (pintype "input"))
      (node (ref "USB7") (pin "6") (pinfunction "D-_6") (pintype "input"))
    )
    (net (code "192") (name "USB1_P") (class "Default")
      (node (ref "U10") (pin "11") (pinfunction "DP1_11") (pintype "input"))
      (node (ref "U31") (pin "1") (pinfunction "1_1") (pintype "input"))
      (node (ref "U31") (pin "10") (pinfunction "10_10") (pintype "input"))
      (node (ref "USB7") (pin "7") (pinfunction "D+_7") (pintype "input"))
    )
    (net (code "193") (name "USB2_N") (class "Default")
      (node (ref "U10") (pin "8") (pinfunction "DM2_8") (pintype "input"))
      (node (ref "U31") (pin "5") (pinfunction "5_5") (pintype "input"))
      (node (ref "U31") (pin "6") (pinfunction "6_6") (pintype "input"))
      (node (ref "USB7") (pin "2") (pinfunction "D-_2") (pintype "input"))
    )
    (net (code "194") (name "USB2_P") (class "Default")
      (node (ref "U10") (pin "9") (pinfunction "DP2_9") (pintype "input"))
      (node (ref "U31") (pin "4") (pinfunction "4_4") (pintype "input"))
      (node (ref "U31") (pin "7") (pinfunction "7_7") (pintype "input"))
      (node (ref "USB7") (pin "3") (pinfunction "D+_3") (pintype "input"))
    )
    (net (code "195") (name "USB_GSM_N") (class "Default")
      (node (ref "R171") (pin "1") (pinfunction "1_1") (pintype "input"))
      (node (ref "U10") (pin "4") (pinfunction "DM4_4") (pintype "input"))
    )
    (net (code "196") (name "USB_GSM_P") (class "Default")
      (node (ref "R170") (pin "1") (pinfunction "1_1") (pintype "input"))
      (node (ref "U10") (pin "5") (pinfunction "DP4_5") (pintype "input"))
    )
    (net (code "197") (name "USB_N") (class "Default")
      (node (ref "U28") (pin "4") (pinfunction "D-_4") (pintype "input"))
      (node (ref "U46") (pin "103") (pinfunction "USB_N_103") (pintype "bidirectional"))
    )
    (net (code "198") (name "USB_OTG_ID") (class "Default")
      (node (ref "R127") (pin "1") (pinfunction "1_1") (pintype "input"))
      (node (ref "R128") (pin "2") (pinfunction "2_2") (pintype "input"))
      (node (ref "U28") (pin "2") (pinfunction "Sel_2") (pintype "input"))
      (node (ref "U46") (pin "101") (pinfunction "USB_OTG_ID_101") (pintype "bidirectional"))
    )
    (net (code "199") (name "USB_P") (class "Default")
      (node (ref "U28") (pin "3") (pinfunction "D+_3") (pintype "input"))
      (node (ref "U46") (pin "105") (pinfunction "USB_P_105") (pintype "bidirectional"))
    )
    (net (code "200") (name "U_N") (class "Default")
      (node (ref "U10") (pin "15") (pinfunction "UDM_15") (pintype "input"))
      (node (ref "U28") (pin "8") (pinfunction "HSD2-_8") (pintype "input"))
    )
    (net (code "201") (name "U_P") (class "Default")
      (node (ref "U10") (pin "16") (pinfunction "UDP_16") (pintype "input"))
      (node (ref "U28") (pin "9") (pinfunction "HSD2+_9") (pintype "input"))
    )
    (net (code "202") (name "XI") (class "Default")
      (node (ref "C26") (pin "1") (pinfunction "1_1") (pintype "input"))
      (node (ref "U10") (pin "3") (pinfunction "XIN_3") (pintype "input"))
      (node (ref "X1") (pin "1") (pinfunction "OSC1_1") (pintype "input"))
    )
    (net (code "203") (name "XO") (class "Default")
      (node (ref "C27") (pin "2") (pinfunction "2_2") (pintype "input"))
      (node (ref "U10") (pin "2") (pinfunction "XOUT_2") (pintype "input"))
      (node (ref "X1") (pin "3") (pinfunction "OSC2_3") (pintype "input"))
    )
    (net (code "204") (name "unconnected-(CARD1-PadCD)") (class "Default")
      (node (ref "CARD1") (pin "CD") (pinfunction "CD_CD") (pintype "input"))
    )
    (net (code "205") (name "unconnected-(CARD2-VPP-PadC6)") (class "Default")
      (node (ref "CARD2") (pin "C6") (pinfunction "VPP_C6") (pintype "input"))
    )
    (net (code "206") (name "unconnected-(CN3-Pad1)") (class "Default")
      (node (ref "CN3") (pin "1") (pinfunction "1_1") (pintype "input"))
    )
    (net (code "207") (name "unconnected-(CN3-Pad8)") (class "Default")
      (node (ref "CN3") (pin "8") (pinfunction "8_8") (pintype "input"))
    )
    (net (code "208") (name "unconnected-(CN3-Pad20)") (class "Default")
      (node (ref "CN3") (pin "20") (pinfunction "20_20") (pintype "input"))
    )
    (net (code "209") (name "unconnected-(CN3-Pad21)") (class "Default")
      (node (ref "CN3") (pin "21") (pinfunction "21_21") (pintype "input"))
    )
    (net (code "210") (name "unconnected-(CN3-Pad22)") (class "Default")
      (node (ref "CN3") (pin "22") (pinfunction "22_22") (pintype "input"))
    )
    (net (code "211") (name "unconnected-(CN3-Pad23)") (class "Default")
      (node (ref "CN3") (pin "23") (pinfunction "23_23") (pintype "input"))
    )
    (net (code "212") (name "unconnected-(CN3-Pad24)") (class "Default")
      (node (ref "CN3") (pin "24") (pinfunction "24_24") (pintype "input"))
    )
    (net (code "213") (name "unconnected-(CN3-Pad25)") (class "Default")
      (node (ref "CN3") (pin "25") (pinfunction "25_25") (pintype "input"))
    )
    (net (code "214") (name "unconnected-(CN3-Pad26)") (class "Default")
      (node (ref "CN3") (pin "26") (pinfunction "26_26") (pintype "input"))
    )
    (net (code "215") (name "unconnected-(CN3-Pad28)") (class "Default")
      (node (ref "CN3") (pin "28") (pinfunction "28_28") (pintype "input"))
    )
    (net (code "216") (name "unconnected-(CN3-Pad29)") (class "Default")
      (node (ref "CN3") (pin "29") (pinfunction "29_29") (pintype "input"))
    )
    (net (code "217") (name "unconnected-(CN3-Pad31)") (class "Default")
      (node (ref "CN3") (pin "31") (pinfunction "31_31") (pintype "input"))
    )
    (net (code "218") (name "unconnected-(CN3-Pad35)") (class "Default")
      (node (ref "CN3") (pin "35") (pinfunction "35_35") (pintype "input"))
    )
    (net (code "219") (name "unconnected-(CN3-Pad37)") (class "Default")
      (node (ref "CN3") (pin "37") (pinfunction "37_37") (pintype "input"))
    )
    (net (code "220") (name "unconnected-(CN3-Pad38)") (class "Default")
      (node (ref "CN3") (pin "38") (pinfunction "38_38") (pintype "input"))
    )
    (net (code "221") (name "unconnected-(CN3-Pad40)") (class "Default")
      (node (ref "CN3") (pin "40") (pinfunction "40_40") (pintype "input"))
    )
    (net (code "222") (name "unconnected-(CN3-Pad41)") (class "Default")
      (node (ref "CN3") (pin "41") (pinfunction "41_41") (pintype "input"))
    )
    (net (code "223") (name "unconnected-(CN3-Pad42)") (class "Default")
      (node (ref "CN3") (pin "42") (pinfunction "42_42") (pintype "input"))
    )
    (net (code "224") (name "unconnected-(CN3-Pad43)") (class "Default")
      (node (ref "CN3") (pin "43") (pinfunction "43_43") (pintype "input"))
    )
    (net (code "225") (name "unconnected-(CN3-Pad44)") (class "Default")
      (node (ref "CN3") (pin "44") (pinfunction "44_44") (pintype "input"))
    )
    (net (code "226") (name "unconnected-(CN3-Pad46)") (class "Default")
      (node (ref "CN3") (pin "46") (pinfunction "46_46") (pintype "input"))
    )
    (net (code "227") (name "unconnected-(CN3-Pad47)") (class "Default")
      (node (ref "CN3") (pin "47") (pinfunction "47_47") (pintype "input"))
    )
    (net (code "228") (name "unconnected-(CN3-Pad48)") (class "Default")
      (node (ref "CN3") (pin "48") (pinfunction "48_48") (pintype "input"))
    )
    (net (code "229") (name "unconnected-(CN3-Pad49)") (class "Default")
      (node (ref "CN3") (pin "49") (pinfunction "49_49") (pintype "input"))
    )
    (net (code "230") (name "unconnected-(CN3-Pad50)") (class "Default")
      (node (ref "CN3") (pin "50") (pinfunction "50_50") (pintype "input"))
    )
    (net (code "231") (name "unconnected-(CN3-Pad52)") (class "Default")
      (node (ref "CN3") (pin "52") (pinfunction "52_52") (pintype "input"))
    )
    (net (code "232") (name "unconnected-(CN3-Pad53)") (class "Default")
      (node (ref "CN3") (pin "53") (pinfunction "53_53") (pintype "input"))
    )
    (net (code "233") (name "unconnected-(CN3-Pad54)") (class "Default")
      (node (ref "CN3") (pin "54") (pinfunction "54_54") (pintype "input"))
    )
    (net (code "234") (name "unconnected-(CN3-Pad55)") (class "Default")
      (node (ref "CN3") (pin "55") (pinfunction "55_55") (pintype "input"))
    )
    (net (code "235") (name "unconnected-(CN3-Pad56)") (class "Default")
      (node (ref "CN3") (pin "56") (pinfunction "56_56") (pintype "input"))
    )
    (net (code "236") (name "unconnected-(CN3-Pad58)") (class "Default")
      (node (ref "CN3") (pin "58") (pinfunction "58_58") (pintype "input"))
    )
    (net (code "237") (name "unconnected-(CN3-Pad59)") (class "Default")
      (node (ref "CN3") (pin "59") (pinfunction "59_59") (pintype "input"))
    )
    (net (code "238") (name "unconnected-(CN3-Pad60)") (class "Default")
      (node (ref "CN3") (pin "60") (pinfunction "60_60") (pintype "input"))
    )
    (net (code "239") (name "unconnected-(CN3-Pad61)") (class "Default")
      (node (ref "CN3") (pin "61") (pinfunction "61_61") (pintype "input"))
    )
    (net (code "240") (name "unconnected-(CN3-Pad63)") (class "Default")
      (node (ref "CN3") (pin "63") (pinfunction "63_63") (pintype "input"))
    )
    (net (code "241") (name "unconnected-(CN3-Pad66)") (class "Default")
      (node (ref "CN3") (pin "66") (pinfunction "66_66") (pintype "input"))
    )
    (net (code "242") (name "unconnected-(CN3-Pad68)") (class "Default")
      (node (ref "CN3") (pin "68") (pinfunction "68_68") (pintype "input"))
    )
    (net (code "243") (name "unconnected-(CN3-Pad69)") (class "Default")
      (node (ref "CN3") (pin "69") (pinfunction "69_69") (pintype "input"))
    )
    (net (code "244") (name "unconnected-(CN3-Pad75)") (class "Default")
      (node (ref "CN3") (pin "75") (pinfunction "75_75") (pintype "input"))
    )
    (net (code "245") (name "unconnected-(CN5-Pad1)") (class "Default")
      (node (ref "CN5") (pin "1") (pinfunction "1_1") (pintype "input"))
    )
    (net (code "246") (name "unconnected-(CN5-Pad5)") (class "Default")
      (node (ref "CN5") (pin "5") (pinfunction "5_5") (pintype "input"))
    )
    (net (code "247") (name "unconnected-(CN5-Pad6)") (class "Default")
      (node (ref "CN5") (pin "6") (pinfunction "6_6") (pintype "input"))
    )
    (net (code "248") (name "unconnected-(CN5-Pad7)") (class "Default")
      (node (ref "CN5") (pin "7") (pinfunction "7_7") (pintype "input"))
    )
    (net (code "249") (name "unconnected-(CN5-Pad8)") (class "Default")
      (node (ref "CN5") (pin "8") (pinfunction "8_8") (pintype "input"))
    )
    (net (code "250") (name "unconnected-(CN5-Pad11)") (class "Default")
      (node (ref "CN5") (pin "11") (pinfunction "11_11") (pintype "input"))
    )
    (net (code "251") (name "unconnected-(CN5-Pad13)") (class "Default")
      (node (ref "CN5") (pin "13") (pinfunction "13_13") (pintype "input"))
    )
    (net (code "252") (name "unconnected-(CN5-Pad17)") (class "Default")
      (node (ref "CN5") (pin "17") (pinfunction "17_17") (pintype "input"))
    )
    (net (code "253") (name "unconnected-(CN5-Pad19)") (class "Default")
      (node (ref "CN5") (pin "19") (pinfunction "19_19") (pintype "input"))
    )
    (net (code "254") (name "unconnected-(CN5-Pad20)") (class "Default")
      (node (ref "CN5") (pin "20") (pinfunction "20_20") (pintype "input"))
    )
    (net (code "255") (name "unconnected-(CN5-Pad21)") (class "Default")
      (node (ref "CN5") (pin "21") (pinfunction "21_21") (pintype "input"))
    )
    (net (code "256") (name "unconnected-(CN5-Pad22)") (class "Default")
      (node (ref "CN5") (pin "22") (pinfunction "22_22") (pintype "input"))
    )
    (net (code "257") (name "unconnected-(CN5-Pad23)") (class "Default")
      (node (ref "CN5") (pin "23") (pinfunction "23_23") (pintype "input"))
    )
    (net (code "258") (name "unconnected-(CN5-Pad24)") (class "Default")
      (node (ref "CN5") (pin "24") (pinfunction "24_24") (pintype "input"))
    )
    (net (code "259") (name "unconnected-(CN5-Pad25)") (class "Default")
      (node (ref "CN5") (pin "25") (pinfunction "25_25") (pintype "input"))
    )
    (net (code "260") (name "unconnected-(CN5-Pad26)") (class "Default")
      (node (ref "CN5") (pin "26") (pinfunction "26_26") (pintype "input"))
    )
    (net (code "261") (name "unconnected-(CN5-Pad28)") (class "Default")
      (node (ref "CN5") (pin "28") (pinfunction "28_28") (pintype "input"))
    )
    (net (code "262") (name "unconnected-(CN5-Pad29)") (class "Default")
      (node (ref "CN5") (pin "29") (pinfunction "29_29") (pintype "input"))
    )
    (net (code "263") (name "unconnected-(CN5-Pad30)") (class "Default")
      (node (ref "CN5") (pin "30") (pinfunction "30_30") (pintype "input"))
    )
    (net (code "264") (name "unconnected-(CN5-Pad31)") (class "Default")
      (node (ref "CN5") (pin "31") (pinfunction "31_31") (pintype "input"))
    )
    (net (code "265") (name "unconnected-(CN5-Pad32)") (class "Default")
      (node (ref "CN5") (pin "32") (pinfunction "32_32") (pintype "input"))
    )
    (net (code "266") (name "unconnected-(CN5-Pad34)") (class "Default")
      (node (ref "CN5") (pin "34") (pinfunction "34_34") (pintype "input"))
    )
    (net (code "267") (name "unconnected-(CN5-Pad35)") (class "Default")
      (node (ref "CN5") (pin "35") (pinfunction "35_35") (pintype "input"))
    )
    (net (code "268") (name "unconnected-(CN5-Pad36)") (class "Default")
      (node (ref "CN5") (pin "36") (pinfunction "36_36") (pintype "input"))
    )
    (net (code "269") (name "unconnected-(CN5-Pad37)") (class "Default")
      (node (ref "CN5") (pin "37") (pinfunction "37_37") (pintype "input"))
    )
    (net (code "270") (name "unconnected-(CN5-Pad38)") (class "Default")
      (node (ref "CN5") (pin "38") (pinfunction "38_38") (pintype "input"))
    )
    (net (code "271") (name "unconnected-(CN5-Pad40)") (class "Default")
      (node (ref "CN5") (pin "40") (pinfunction "40_40") (pintype "input"))
    )
    (net (code "272") (name "unconnected-(CN5-Pad42)") (class "Default")
      (node (ref "CN5") (pin "42") (pinfunction "42_42") (pintype "input"))
    )
    (net (code "273") (name "unconnected-(CN5-Pad44)") (class "Default")
      (node (ref "CN5") (pin "44") (pinfunction "44_44") (pintype "input"))
    )
    (net (code "274") (name "unconnected-(CN5-Pad46)") (class "Default")
      (node (ref "CN5") (pin "46") (pinfunction "46_46") (pintype "input"))
    )
    (net (code "275") (name "unconnected-(CN5-Pad48)") (class "Default")
      (node (ref "CN5") (pin "48") (pinfunction "48_48") (pintype "input"))
    )
    (net (code "276") (name "unconnected-(CN5-Pad54)") (class "Default")
      (node (ref "CN5") (pin "54") (pinfunction "54_54") (pintype "input"))
    )
    (net (code "277") (name "unconnected-(CN5-Pad56)") (class "Default")
      (node (ref "CN5") (pin "56") (pinfunction "56_56") (pintype "input"))
    )
    (net (code "278") (name "unconnected-(CN5-Pad58)") (class "Default")
      (node (ref "CN5") (pin "58") (pinfunction "58_58") (pintype "input"))
    )
    (net (code "279") (name "unconnected-(CN5-Pad67)") (class "Default")
      (node (ref "CN5") (pin "67") (pinfunction "67_67") (pintype "input"))
    )
    (net (code "280") (name "unconnected-(CN5-Pad68)") (class "Default")
      (node (ref "CN5") (pin "68") (pinfunction "68_68") (pintype "input"))
    )
    (net (code "281") (name "unconnected-(CN5-Pad69)") (class "Default")
      (node (ref "CN5") (pin "69") (pinfunction "69_69") (pintype "input"))
    )
    (net (code "282") (name "unconnected-(CN5-Pad75)") (class "Default")
      (node (ref "CN5") (pin "75") (pinfunction "75_75") (pintype "input"))
    )
    (net (code "283") (name "unconnected-(CN20-Utility-Pad2)") (class "Default")
      (node (ref "CN20") (pin "2") (pinfunction "Utility_2") (pintype "unspecified"))
    )
    (net (code "284") (name "unconnected-(FPC8-Pad5)") (class "Default")
      (node (ref "FPC8") (pin "5") (pinfunction "5_5") (pintype "input"))
    )
    (net (code "285") (name "unconnected-(SW1-Pad3)") (class "Default")
      (node (ref "SW1") (pin "3") (pinfunction "3_3") (pintype "input"))
    )
    (net (code "286") (name "unconnected-(SW1-Pad6)") (class "Default")
      (node (ref "SW1") (pin "6") (pinfunction "6_6") (pintype "input"))
    )
    (net (code "287") (name "unconnected-(U8-AIN1-Pad5)") (class "Default")
      (node (ref "U8") (pin "5") (pinfunction "AIN1_5") (pintype "input"))
    )
    (net (code "288") (name "unconnected-(U10-DM3-Pad6)") (class "Default")
      (node (ref "U10") (pin "6") (pinfunction "DM3_6") (pintype "input+no_connect"))
    )
    (net (code "289") (name "unconnected-(U10-DP3-Pad7)") (class "Default")
      (node (ref "U10") (pin "7") (pinfunction "DP3_7") (pintype "input+no_connect"))
    )
    (net (code "290") (name "unconnected-(U10-DRV-Pad22)") (class "Default")
      (node (ref "U10") (pin "22") (pinfunction "DRV_22") (pintype "input+no_connect"))
    )
    (net (code "291") (name "unconnected-(U10-LED1-Pad23)") (class "Default")
      (node (ref "U10") (pin "23") (pinfunction "LED1_23") (pintype "input+no_connect"))
    )
    (net (code "292") (name "unconnected-(U10-LED2-Pad24)") (class "Default")
      (node (ref "U10") (pin "24") (pinfunction "LED2_24") (pintype "input+no_connect"))
    )
    (net (code "293") (name "unconnected-(U10-PWRN-Pad25)") (class "Default")
      (node (ref "U10") (pin "25") (pinfunction "PWRN_25") (pintype "input+no_connect"))
    )
    (net (code "294") (name "unconnected-(U10-SCL-Pad27)") (class "Default")
      (node (ref "U10") (pin "27") (pinfunction "SCL_27") (pintype "input"))
    )
    (net (code "295") (name "unconnected-(U19-SWQ{slash}OUT-Pad7)") (class "Default")
      (node (ref "U19") (pin "7") (pinfunction "SWQ/OUT_7") (pintype "input"))
    )
    (net (code "296") (name "unconnected-(U22A-IN1+-Pad3)") (class "Default")
      (node (ref "U22") (pin "3") (pinfunction "IN1+_3") (pintype "input"))
    )
    (net (code "297") (name "unconnected-(U22A-IN1--Pad2)") (class "Default")
      (node (ref "U22") (pin "2") (pinfunction "IN1-_2") (pintype "input"))
    )
    (net (code "298") (name "unconnected-(U22A-OUT1-Pad1)") (class "Default")
      (node (ref "U22") (pin "1") (pinfunction "OUT1_1") (pintype "input"))
    )
    (net (code "299") (name "unconnected-(U45-AnalogIP0-Pad96)") (class "Default")
      (node (ref "U45") (pin "96") (pinfunction "AnalogIP0_96") (pintype "bidirectional"))
    )
    (net (code "300") (name "unconnected-(U45-AnalogIP1-Pad94)") (class "Default")
      (node (ref "U45") (pin "94") (pinfunction "AnalogIP1_94") (pintype "bidirectional"))
    )
    (net (code "301") (name "unconnected-(U45-BT_nDISABLE-Pad91)") (class "Default")
      (node (ref "U45") (pin "91") (pinfunction "BT_nDISABLE_91") (pintype "bidirectional"))
    )
    (net (code "302") (name "unconnected-(U45-CM4_1.8V_O-Pad88)") (class "Default")
      (node (ref "U45") (pin "88") (pinfunction "CM4_1.8V_O_88") (pintype "bidirectional"))
    )
    (net (code "303") (name "unconnected-(U45-CM4_1.8V_O-Pad90)") (class "Default")
      (node (ref "U45") (pin "90") (pinfunction "CM4_1.8V_O_90") (pintype "bidirectional"))
    )
    (net (code "304") (name "unconnected-(U45-EEPROM_nWP-Pad20)") (class "Default")
      (node (ref "U45") (pin "20") (pinfunction "EEPROM_nWP_20") (pintype "bidirectional+no_connect"))
    )
    (net (code "305") (name "unconnected-(U45-ETH_SYNC_IN-Pad16)") (class "Default")
      (node (ref "U45") (pin "16") (pinfunction "ETH_SYNC_IN_16") (pintype "bidirectional+no_connect"))
    )
    (net (code "306") (name "unconnected-(U45-ETH_SYNC_OUT-Pad18)") (class "Default")
      (node (ref "U45") (pin "18") (pinfunction "ETH_SYNC_OUT_18") (pintype "bidirectional+no_connect"))
    )
    (net (code "307") (name "unconnected-(U45-ETH_nLED1-Pad19)") (class "Default")
      (node (ref "U45") (pin "19") (pinfunction "ETH_nLED1_19") (pintype "bidirectional+no_connect"))
    )
    (net (code "308") (name "unconnected-(U45-GLOBAL_EN-Pad99)") (class "Default")
      (node (ref "U45") (pin "99") (pinfunction "GLOBAL_EN_99") (pintype "bidirectional"))
    )
    (net (code "309") (name "unconnected-(U45-GPIO7-Pad37)") (class "Default")
      (node (ref "U45") (pin "37") (pinfunction "GPIO7_37") (pintype "bidirectional+no_connect"))
    )
    (net (code "310") (name "unconnected-(U45-GPIO11-Pad38)") (class "Default")
      (node (ref "U45") (pin "38") (pinfunction "GPIO11_38") (pintype "bidirectional"))
    )
    (net (code "311") (name "unconnected-(U45-GPIO15-Pad51)") (class "Default")
      (node (ref "U45") (pin "51") (pinfunction "GPIO15_51") (pintype "bidirectional+no_connect"))
    )
    (net (code "312") (name "unconnected-(U45-GPIO18-Pad49)") (class "Default")
      (node (ref "U45") (pin "49") (pinfunction "GPIO18_49") (pintype "bidirectional+no_connect"))
    )
    (net (code "313") (name "unconnected-(U45-GPIO20-Pad27)") (class "Default")
      (node (ref "U45") (pin "27") (pinfunction "GPIO20_27") (pintype "bidirectional+no_connect"))
    )
    (net (code "314") (name "unconnected-(U45-GPIO21-Pad25)") (class "Default")
      (node (ref "U45") (pin "25") (pinfunction "GPIO21_25") (pintype "bidirectional+no_connect"))
    )
    (net (code "315") (name "unconnected-(U45-GPIO24-Pad45)") (class "Default")
      (node (ref "U45") (pin "45") (pinfunction "GPIO24_45") (pintype "bidirectional+no_connect"))
    )
    (net (code "316") (name "unconnected-(U45-GPIO25-Pad41)") (class "Default")
      (node (ref "U45") (pin "41") (pinfunction "GPIO25_41") (pintype "bidirectional+no_connect"))
    )
    (net (code "317") (name "unconnected-(U45-ID_SC-Pad35)") (class "Default")
      (node (ref "U45") (pin "35") (pinfunction "ID_SC_35") (pintype "bidirectional+no_connect"))
    )
    (net (code "318") (name "unconnected-(U45-ID_SD-Pad36)") (class "Default")
      (node (ref "U45") (pin "36") (pinfunction "ID_SD_36") (pintype "bidirectional+no_connect"))
    )
    (net (code "319") (name "unconnected-(U45-PI_LED_nPWR-Pad95)") (class "Default")
      (node (ref "U45") (pin "95") (pinfunction "PI_LED_nPWR_95") (pintype "bidirectional"))
    )
    (net (code "320") (name "unconnected-(U45-RESERVED-Pad76)") (class "Default")
      (node (ref "U45") (pin "76") (pinfunction "RESERVED_76") (pintype "bidirectional"))
    )
    (net (code "321") (name "unconnected-(U45-RUN_PG-Pad92)") (class "Default")
      (node (ref "U45") (pin "92") (pinfunction "RUN_PG_92") (pintype "bidirectional"))
    )
    (net (code "322") (name "unconnected-(U45-SD_DAT4-Pad68)") (class "Default")
      (node (ref "U45") (pin "68") (pinfunction "SD_DAT4_68") (pintype "bidirectional+no_connect"))
    )
    (net (code "323") (name "unconnected-(U45-SD_DAT5-Pad64)") (class "Default")
      (node (ref "U45") (pin "64") (pinfunction "SD_DAT5_64") (pintype "bidirectional+no_connect"))
    )
    (net (code "324") (name "unconnected-(U45-SD_DAT6-Pad72)") (class "Default")
      (node (ref "U45") (pin "72") (pinfunction "SD_DAT6_72") (pintype "bidirectional+no_connect"))
    )
    (net (code "325") (name "unconnected-(U45-SD_DAT7-Pad70)") (class "Default")
      (node (ref "U45") (pin "70") (pinfunction "SD_DAT7_70") (pintype "bidirectional+no_connect"))
    )
    (net (code "326") (name "unconnected-(U45-SD_VDD_Override-Pad73)") (class "Default")
      (node (ref "U45") (pin "73") (pinfunction "SD_VDD_Override_73") (pintype "bidirectional+no_connect"))
    )
    (net (code "327") (name "unconnected-(U45-WL_nDISABLE-Pad89)") (class "Default")
      (node (ref "U45") (pin "89") (pinfunction "WL_nDISABLE_89") (pintype "bidirectional"))
    )
    (net (code "328") (name "unconnected-(U45-nEXTRST-Pad100)") (class "Default")
      (node (ref "U45") (pin "100") (pinfunction "nEXTRST_100") (pintype "bidirectional"))
    )
    (net (code "329") (name "unconnected-(U46-CAM0_C_P-Pad142)") (class "Default")
      (node (ref "U46") (pin "142") (pinfunction "CAM0_C_P_142") (pintype "bidirectional+no_connect"))
    )
    (net (code "330") (name "unconnected-(U46-CAM0_D0_N-Pad128)") (class "Default")
      (node (ref "U46") (pin "128") (pinfunction "CAM0_D0_N_128") (pintype "bidirectional+no_connect"))
    )
    (net (code "331") (name "unconnected-(U46-CAM0_D0_P-Pad130)") (class "Default")
      (node (ref "U46") (pin "130") (pinfunction "CAM0_D0_P_130") (pintype "bidirectional+no_connect"))
    )
    (net (code "332") (name "unconnected-(U46-CAM0_D1_N-Pad134)") (class "Default")
      (node (ref "U46") (pin "134") (pinfunction "CAM0_D1_N_134") (pintype "bidirectional+no_connect"))
    )
    (net (code "333") (name "unconnected-(U46-CAM0_D1_P-Pad136)") (class "Default")
      (node (ref "U46") (pin "136") (pinfunction "CAM0_D1_P_136") (pintype "bidirectional+no_connect"))
    )
    (net (code "334") (name "unconnected-(U46-CAM0_D_N-Pad140)") (class "Default")
      (node (ref "U46") (pin "140") (pinfunction "CAM0_D_N_140") (pintype "bidirectional+no_connect"))
    )
    (net (code "335") (name "unconnected-(U46-DSI0_C_N-Pad169)") (class "Default")
      (node (ref "U46") (pin "169") (pinfunction "DSI0_C_N_169") (pintype "bidirectional+no_connect"))
    )
    (net (code "336") (name "unconnected-(U46-DSI0_C_P-Pad171)") (class "Default")
      (node (ref "U46") (pin "171") (pinfunction "DSI0_C_P_171") (pintype "bidirectional+no_connect"))
    )
    (net (code "337") (name "unconnected-(U46-DSI0_D0_N-Pad157)") (class "Default")
      (node (ref "U46") (pin "157") (pinfunction "DSI0_D0_N_157") (pintype "bidirectional+no_connect"))
    )
    (net (code "338") (name "unconnected-(U46-DSI0_D0_P-Pad159)") (class "Default")
      (node (ref "U46") (pin "159") (pinfunction "DSI0_D0_P_159") (pintype "bidirectional+no_connect"))
    )
    (net (code "339") (name "unconnected-(U46-DSI0_D1_N-Pad163)") (class "Default")
      (node (ref "U46") (pin "163") (pinfunction "DSI0_D1_N_163") (pintype "bidirectional+no_connect"))
    )
    (net (code "340") (name "unconnected-(U46-DSI0_D1_P-Pad165)") (class "Default")
      (node (ref "U46") (pin "165") (pinfunction "DSI0_D1_P_165") (pintype "bidirectional+no_connect"))
    )
    (net (code "341") (name "unconnected-(U46-DSI1_C_N-Pad187)") (class "Default")
      (node (ref "U46") (pin "187") (pinfunction "DSI1_C_N_187") (pintype "bidirectional"))
    )
    (net (code "342") (name "unconnected-(U46-DSI1_C_P-Pad189)") (class "Default")
      (node (ref "U46") (pin "189") (pinfunction "DSI1_C_P_189") (pintype "bidirectional"))
    )
    (net (code "343") (name "unconnected-(U46-DSI1_D0_N-Pad175)") (class "Default")
      (node (ref "U46") (pin "175") (pinfunction "DSI1_D0_N_175") (pintype "bidirectional"))
    )
    (net (code "344") (name "unconnected-(U46-DSI1_D0_P-Pad177)") (class "Default")
      (node (ref "U46") (pin "177") (pinfunction "DSI1_D0_P_177") (pintype "bidirectional"))
    )
    (net (code "345") (name "unconnected-(U46-DSI1_D1_N-Pad181)") (class "Default")
      (node (ref "U46") (pin "181") (pinfunction "DSI1_D1_N_181") (pintype "bidirectional"))
    )
    (net (code "346") (name "unconnected-(U46-DSI1_D1_P-Pad183)") (class "Default")
      (node (ref "U46") (pin "183") (pinfunction "DSI1_D1_P_183") (pintype "bidirectional"))
    )
    (net (code "347") (name "unconnected-(U46-DSI1_D2_N-Pad193)") (class "Default")
      (node (ref "U46") (pin "193") (pinfunction "DSI1_D2_N_193") (pintype "bidirectional"))
    )
    (net (code "348") (name "unconnected-(U46-DSI1_D2_P-Pad195)") (class "Default")
      (node (ref "U46") (pin "195") (pinfunction "DSI1_D2_P_195") (pintype "bidirectional"))
    )
    (net (code "349") (name "unconnected-(U46-DSI1_D3_N-Pad194)") (class "Default")
      (node (ref "U46") (pin "194") (pinfunction "DSI1_D3_N_194") (pintype "bidirectional"))
    )
    (net (code "350") (name "unconnected-(U46-DSI1_D3_P-Pad196)") (class "Default")
      (node (ref "U46") (pin "196") (pinfunction "DSI1_D3_P_196") (pintype "bidirectional"))
    )
    (net (code "351") (name "unconnected-(U46-HDMI1_CEC-Pad149)") (class "Default")
      (node (ref "U46") (pin "149") (pinfunction "HDMI1_CEC_149") (pintype "bidirectional"))
    )
    (net (code "352") (name "unconnected-(U46-HDMI1_CLK_N-Pad166)") (class "Default")
      (node (ref "U46") (pin "166") (pinfunction "HDMI1_CLK_N_166") (pintype "bidirectional"))
    )
    (net (code "353") (name "unconnected-(U46-HDMI1_CLK_P-Pad164)") (class "Default")
      (node (ref "U46") (pin "164") (pinfunction "HDMI1_CLK_P_164") (pintype "bidirectional"))
    )
    (net (code "354") (name "unconnected-(U46-HDMI1_HOTPLUG-Pad143)") (class "Default")
      (node (ref "U46") (pin "143") (pinfunction "HDMI1_HOTPLUG_143") (pintype "bidirectional"))
    )
    (net (code "355") (name "unconnected-(U46-HDMI1_SCL-Pad147)") (class "Default")
      (node (ref "U46") (pin "147") (pinfunction "HDMI1_SCL_147") (pintype "bidirectional"))
    )
    (net (code "356") (name "unconnected-(U46-HDMI1_SDA-Pad145)") (class "Default")
      (node (ref "U46") (pin "145") (pinfunction "HDMI1_SDA_145") (pintype "bidirectional"))
    )
    (net (code "357") (name "unconnected-(U46-HDMI1_TX0_N-Pad160)") (class "Default")
      (node (ref "U46") (pin "160") (pinfunction "HDMI1_TX0_N_160") (pintype "bidirectional"))
    )
    (net (code "358") (name "unconnected-(U46-HDMI1_TX0_P-Pad158)") (class "Default")
      (node (ref "U46") (pin "158") (pinfunction "HDMI1_TX0_P_158") (pintype "bidirectional"))
    )
    (net (code "359") (name "unconnected-(U46-HDMI1_TX1_N-Pad154)") (class "Default")
      (node (ref "U46") (pin "154") (pinfunction "HDMI1_TX1_N_154") (pintype "bidirectional"))
    )
    (net (code "360") (name "unconnected-(U46-HDMI1_TX1_P-Pad152)") (class "Default")
      (node (ref "U46") (pin "152") (pinfunction "HDMI1_TX1_P_152") (pintype "bidirectional"))
    )
    (net (code "361") (name "unconnected-(U46-HDMI1_TX2_N-Pad148)") (class "Default")
      (node (ref "U46") (pin "148") (pinfunction "HDMI1_TX2_N_148") (pintype "bidirectional"))
    )
    (net (code "362") (name "unconnected-(U46-HDMI1_TX2_P-Pad146)") (class "Default")
      (node (ref "U46") (pin "146") (pinfunction "HDMI1_TX2_P_146") (pintype "bidirectional"))
    )
    (net (code "363") (name "unconnected-(U46-RESERVED-Pad104)") (class "Default")
      (node (ref "U46") (pin "104") (pinfunction "RESERVED_104") (pintype "bidirectional+no_connect"))
    )
    (net (code "364") (name "unconnected-(U46-RESERVED-Pad106)") (class "Default")
      (node (ref "U46") (pin "106") (pinfunction "RESERVED_106") (pintype "bidirectional+no_connect"))
    )
    (net (code "365") (name "unconnected-(U46-VDAC_COMP-Pad111)") (class "Default")
      (node (ref "U46") (pin "111") (pinfunction "VDAC_COMP_111") (pintype "bidirectional"))
    )
    (net (code "366") (name "unconnected-(USB8-ID-Pad4)") (class "Default")
      (node (ref "USB8") (pin "4") (pinfunction "ID_4") (pintype "input+no_connect"))
    )
    (net (code "367") (name "unconnected-(USB16-Reserved(N.C.)-Pad14)") (class "Default")
      (node (ref "USB16") (pin "14") (pinfunction "Reserved(N.C.)_14") (pintype "input"))
    )
  )
)
